# PixHawk_Fire_v1_5.net
KiCad netlist of a schematic drawn in EAGLE
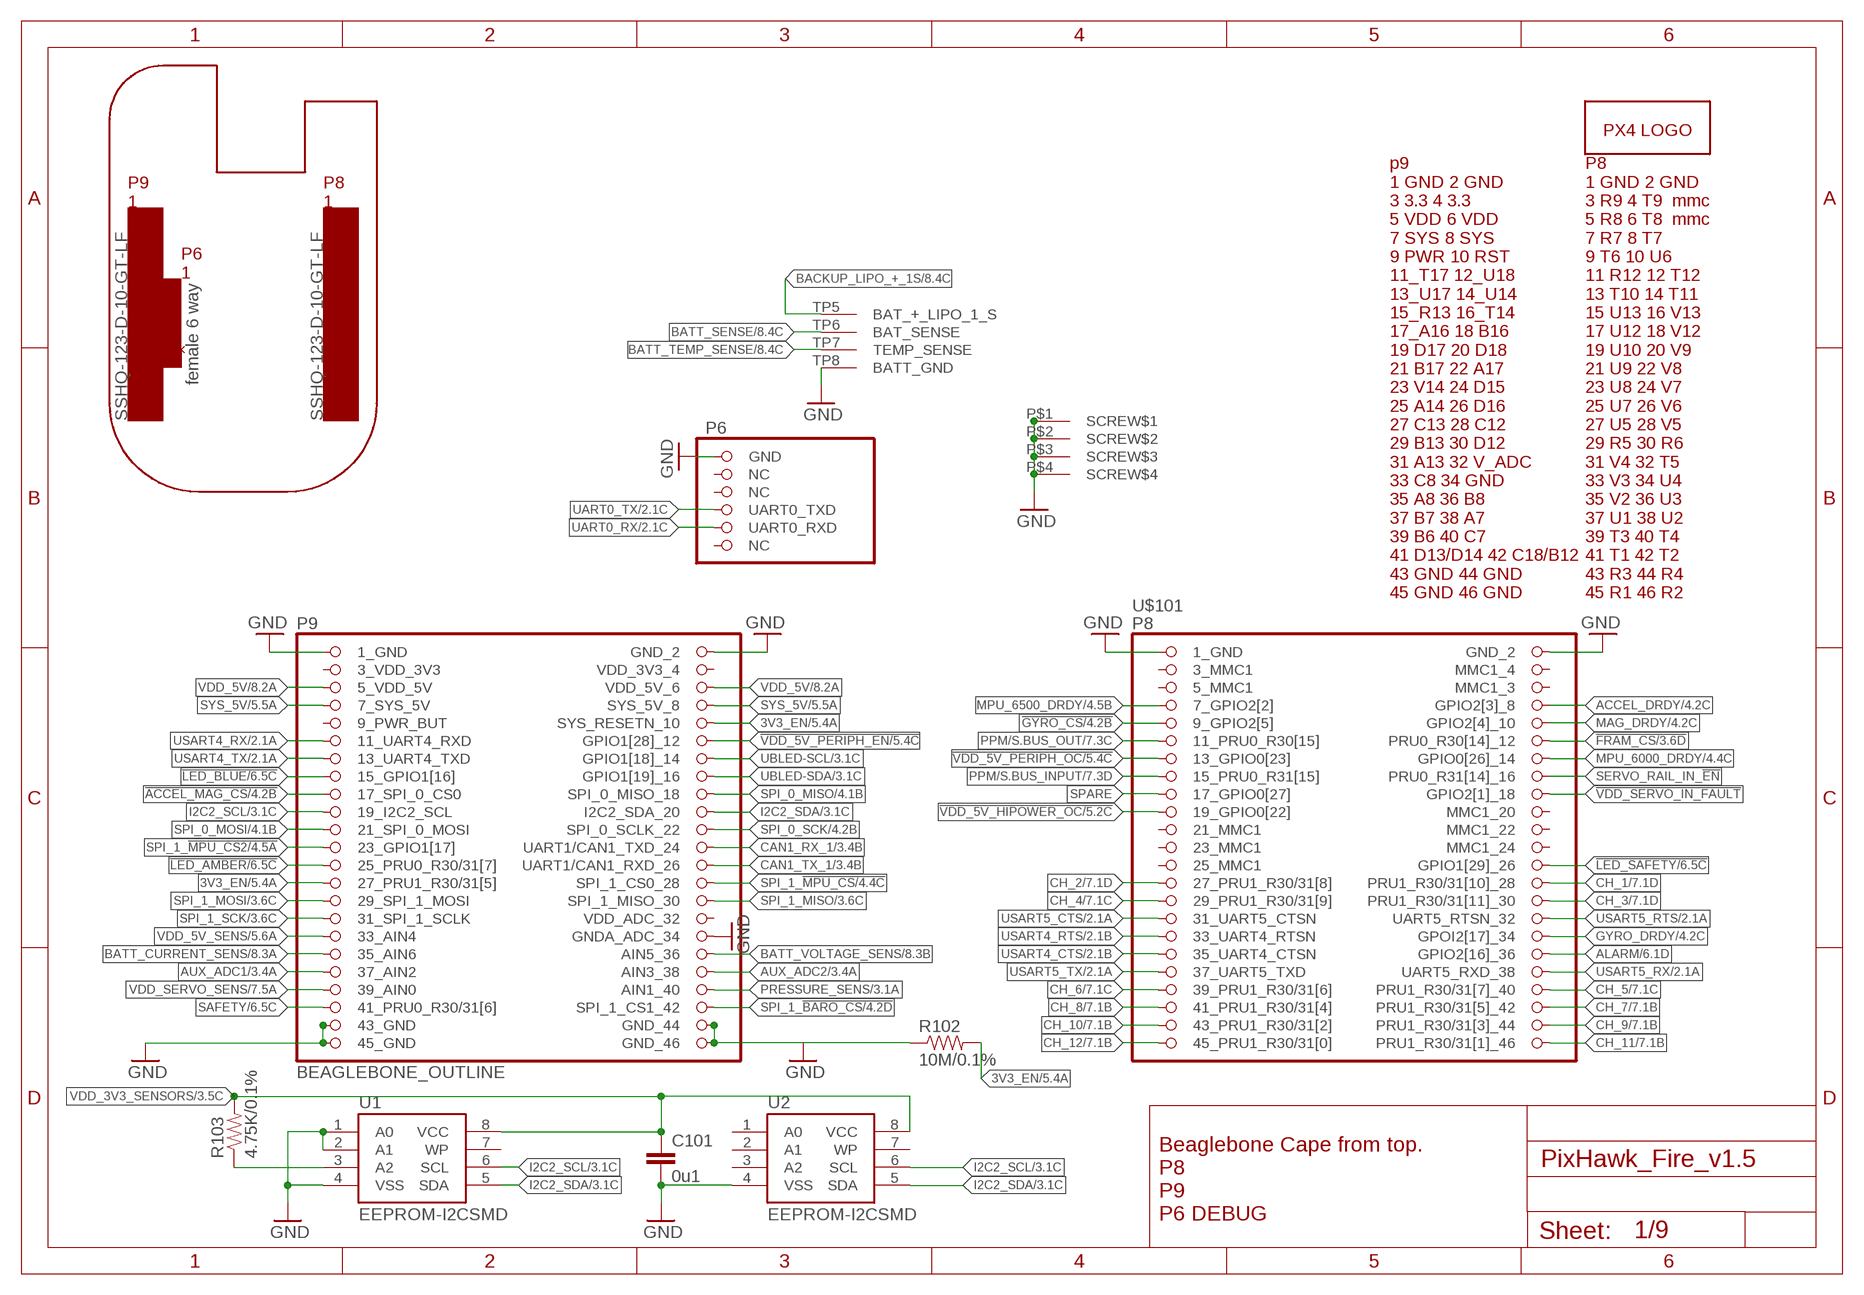
[diagram p0: schematic, sheet 1]
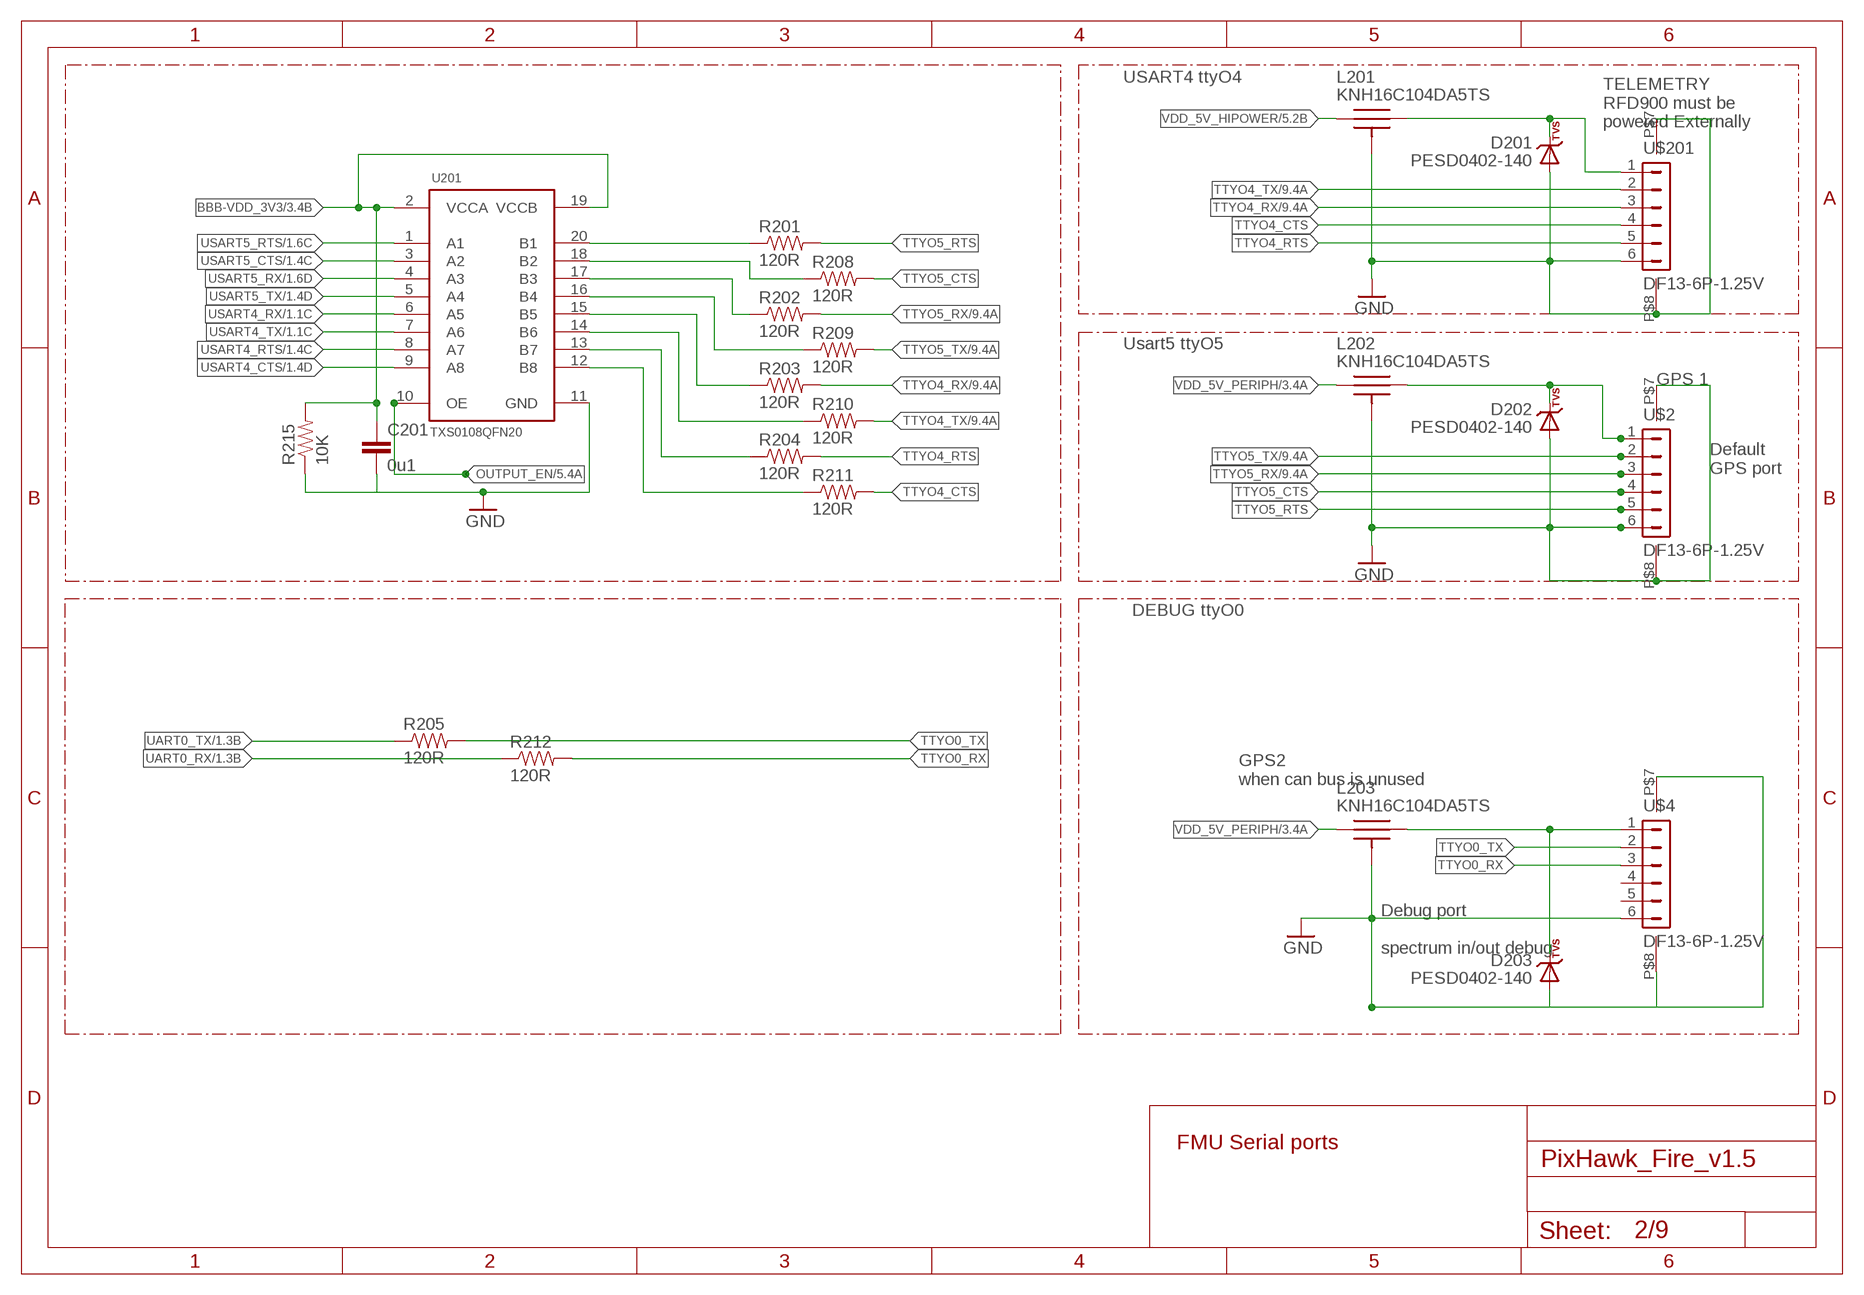
[diagram p1: schematic, sheet 2]
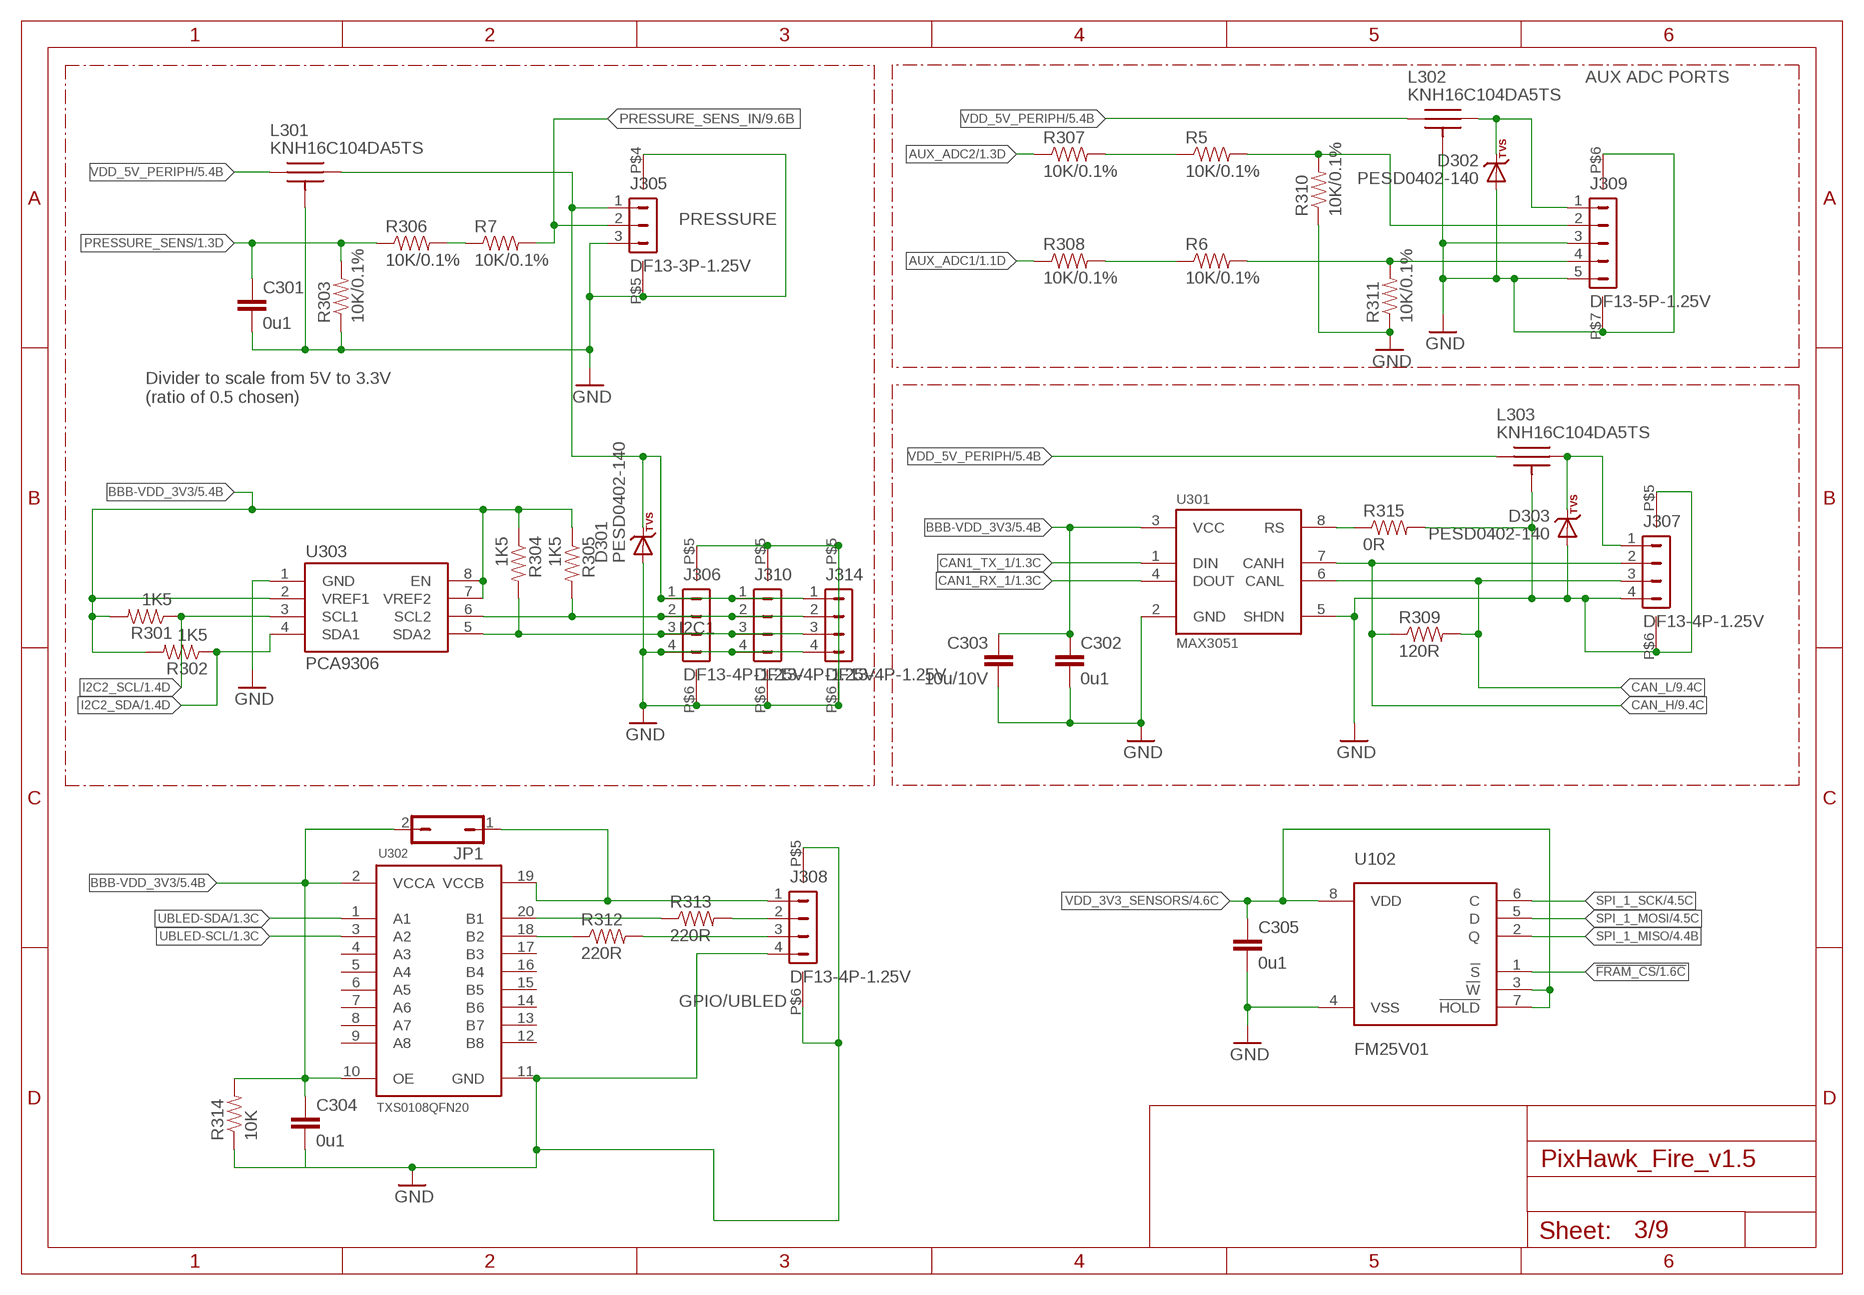
[diagram p2: schematic, sheet 3]
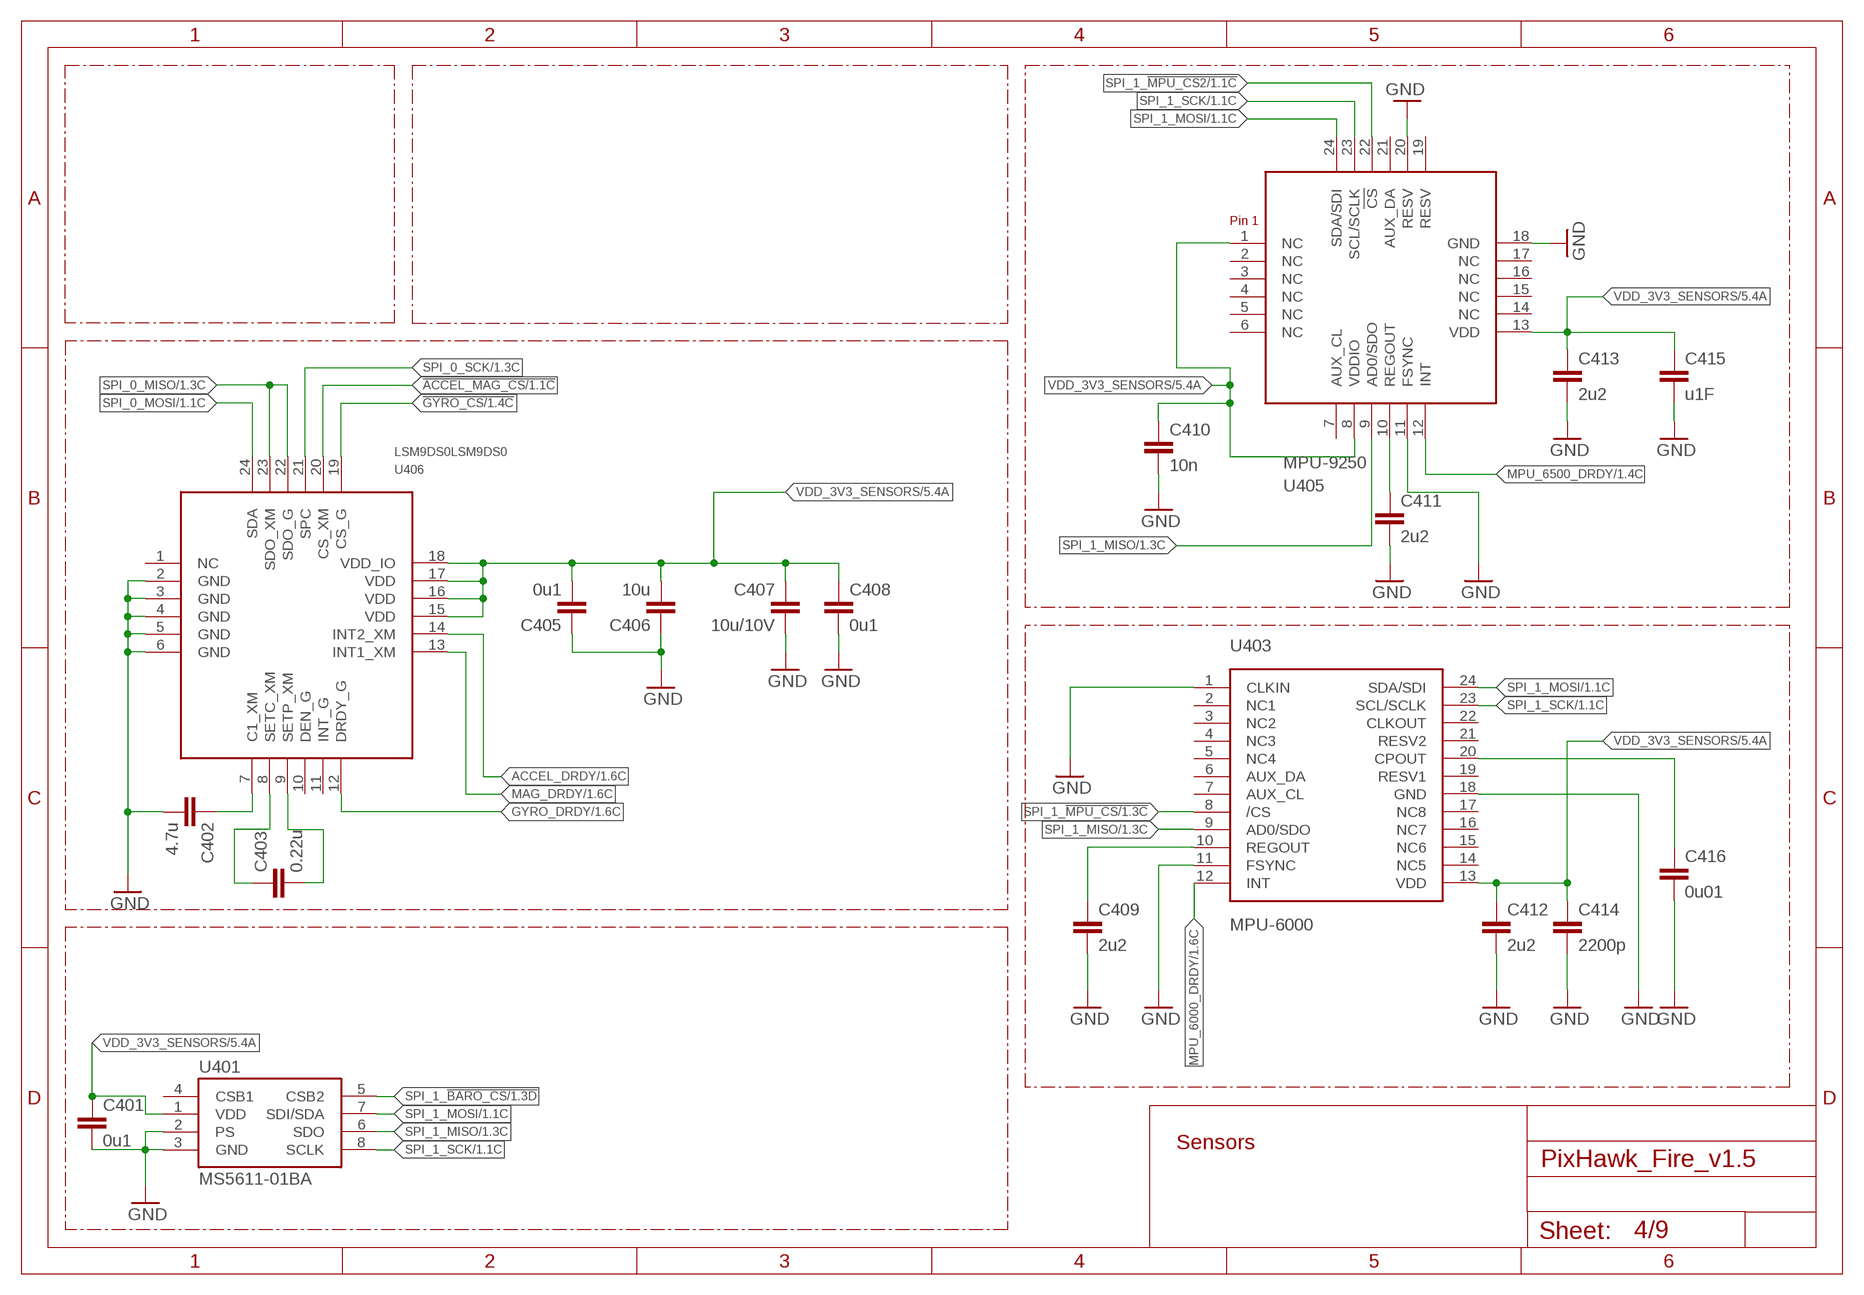
[diagram p3: schematic, sheet 4]
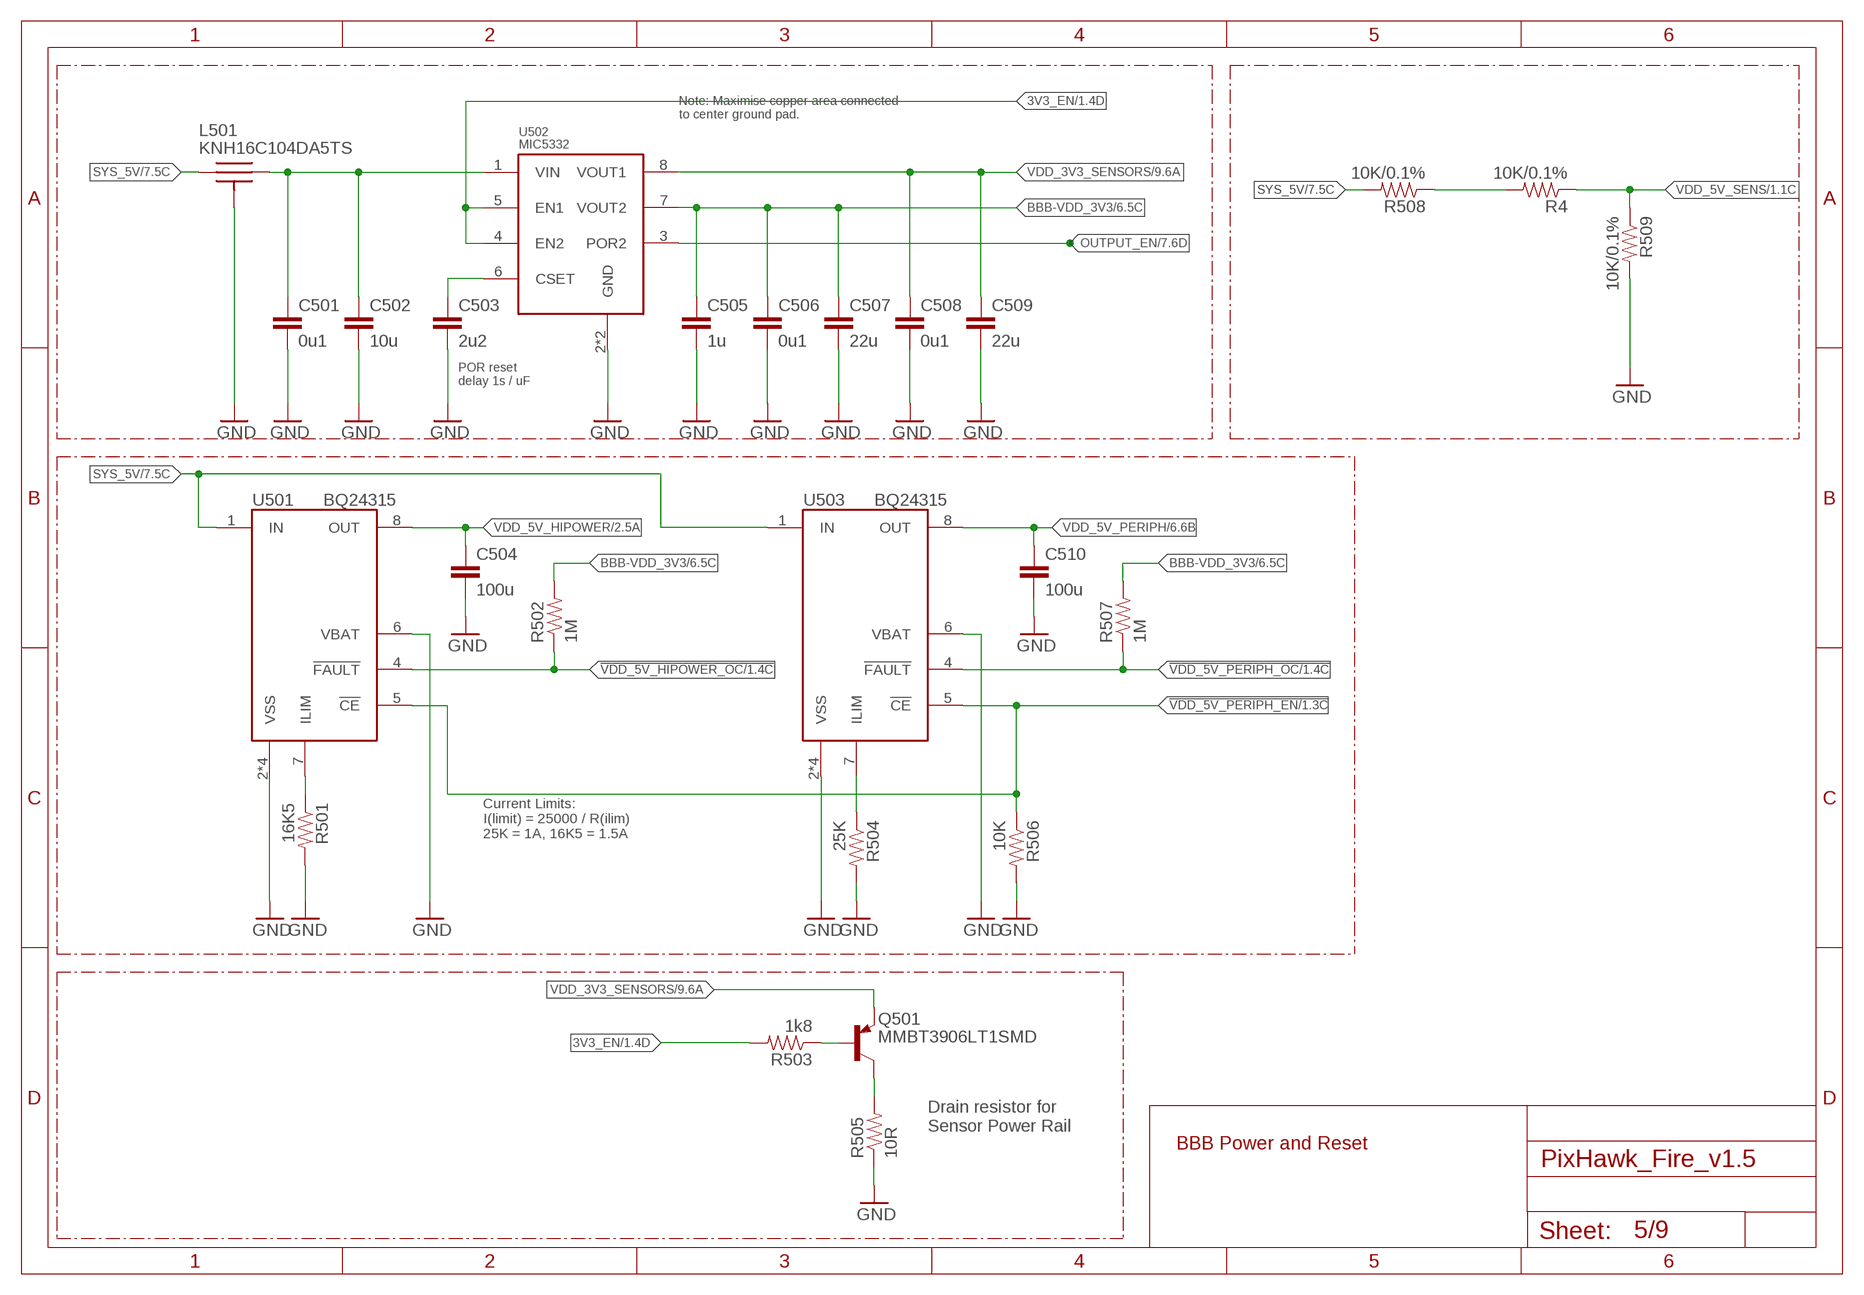
[diagram p4: schematic, sheet 5]
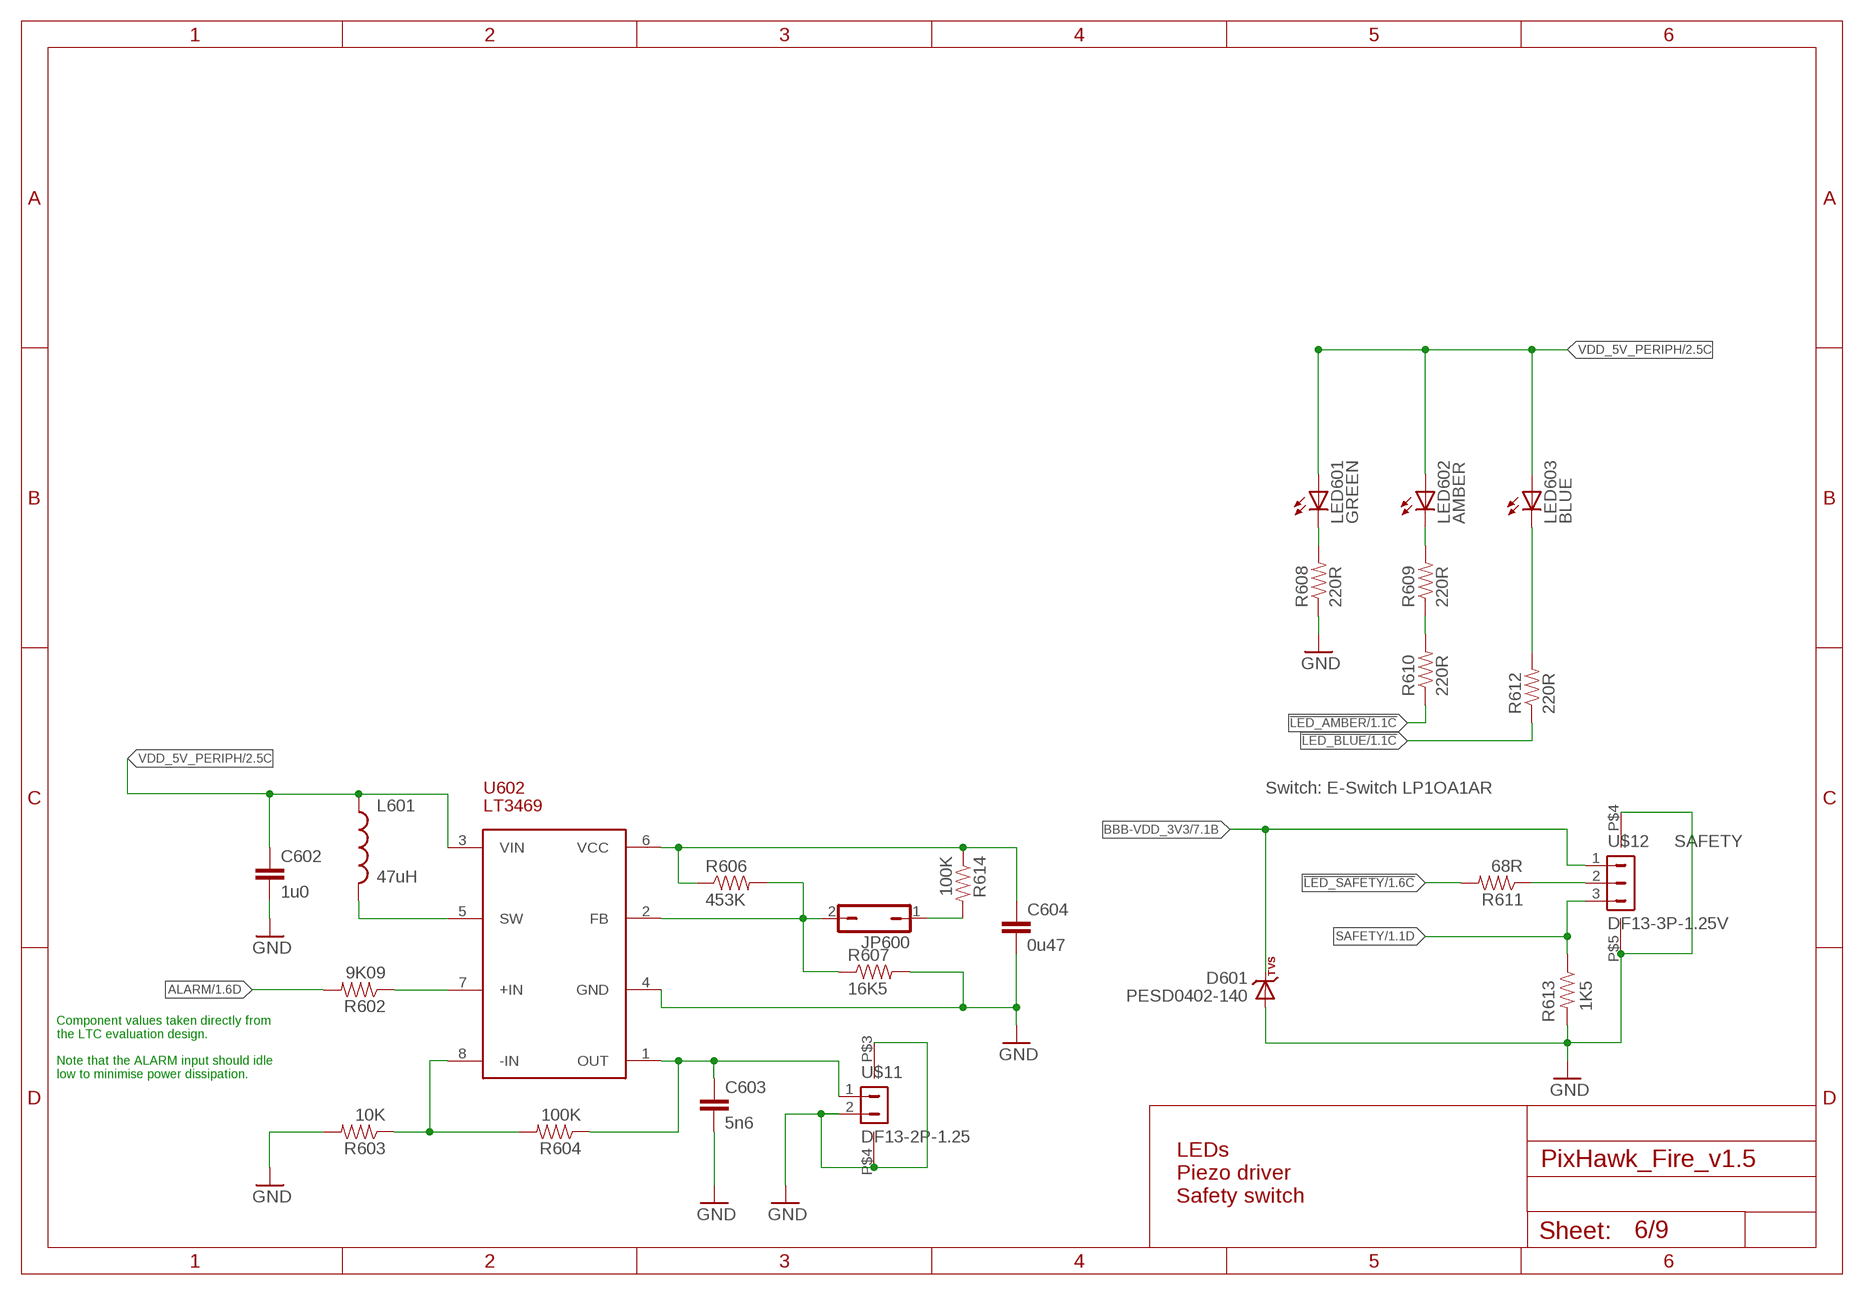
[diagram p5: schematic, sheet 6]
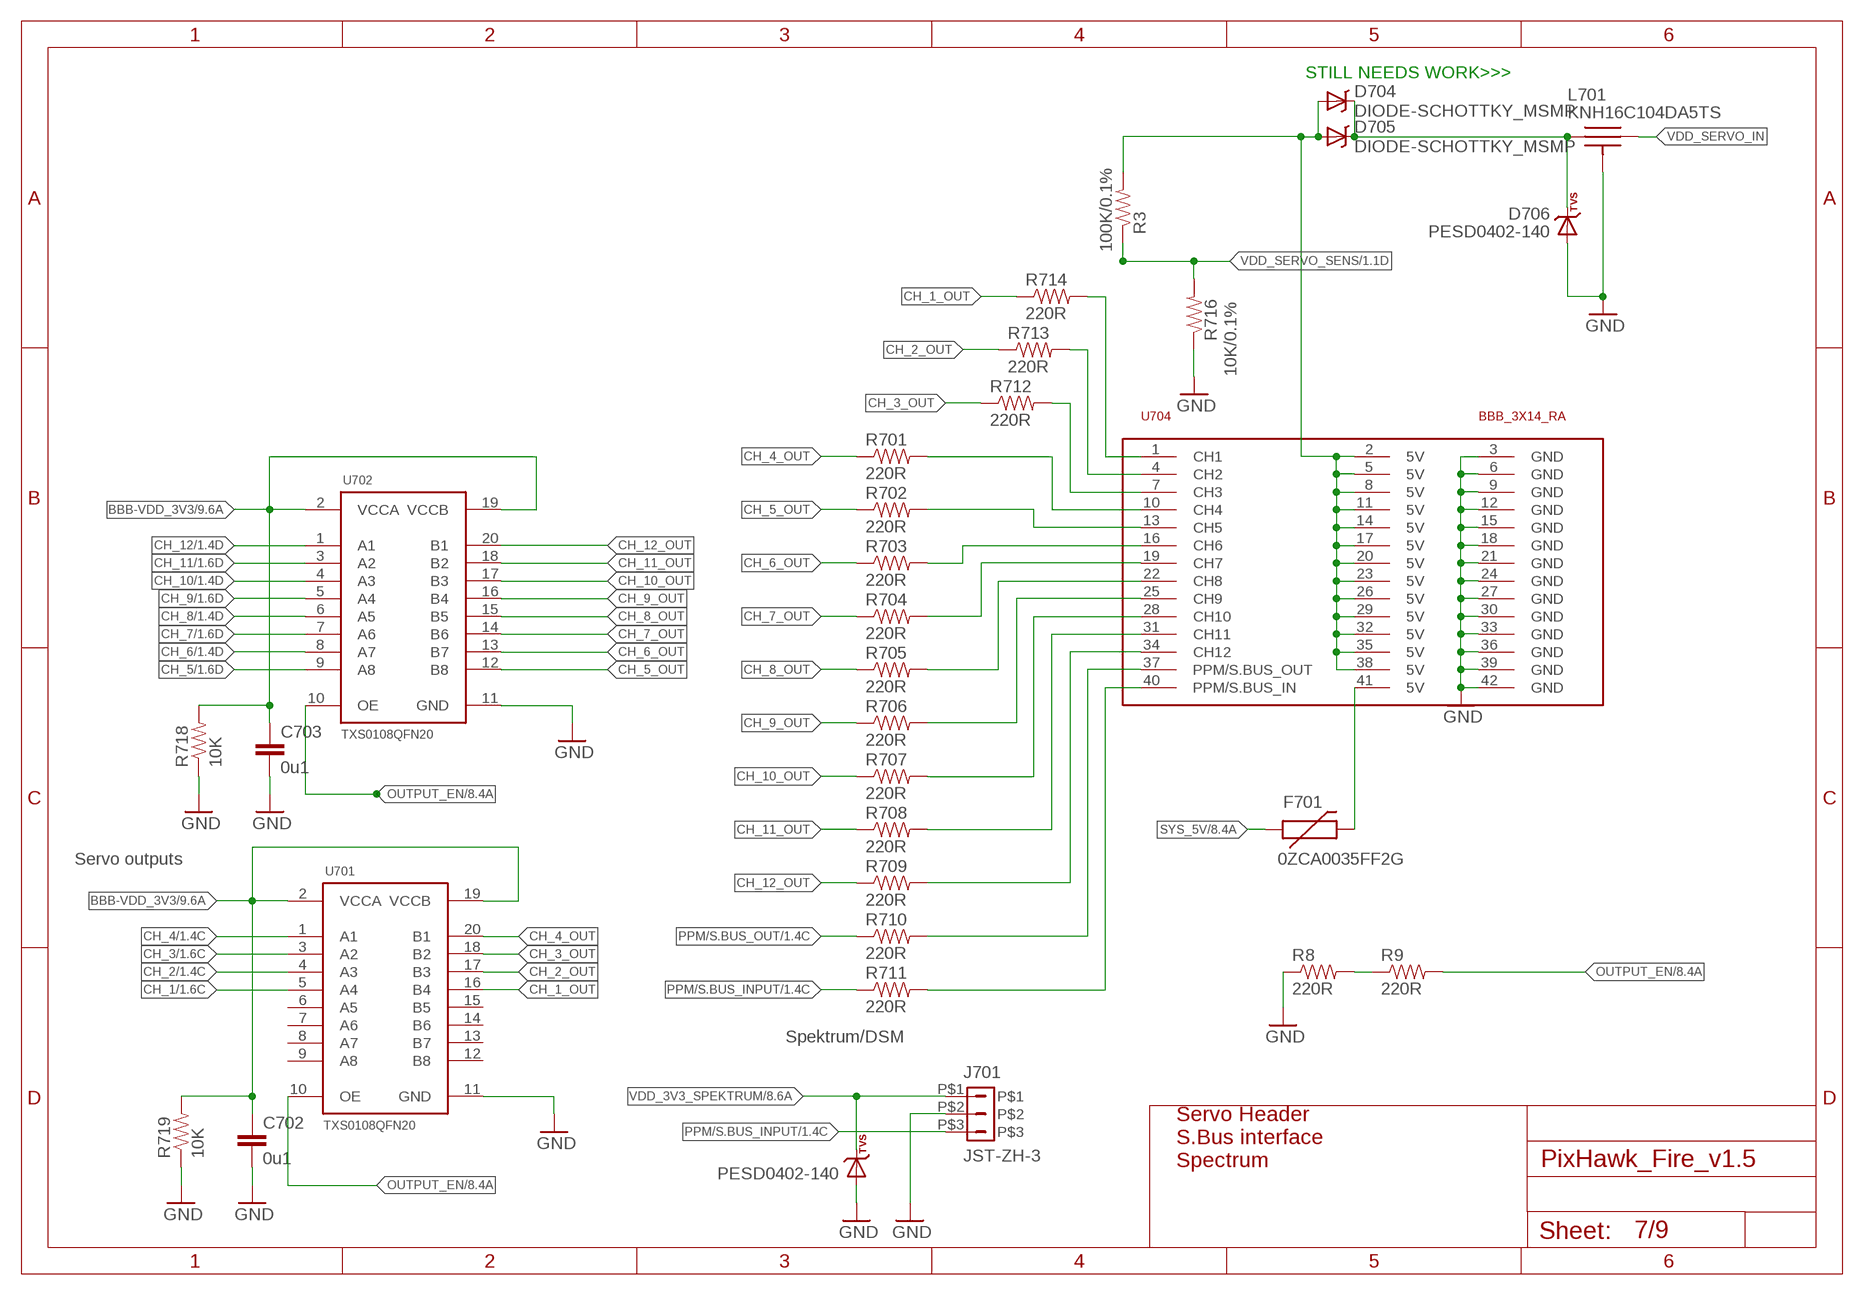
[diagram p6: schematic, sheet 7]
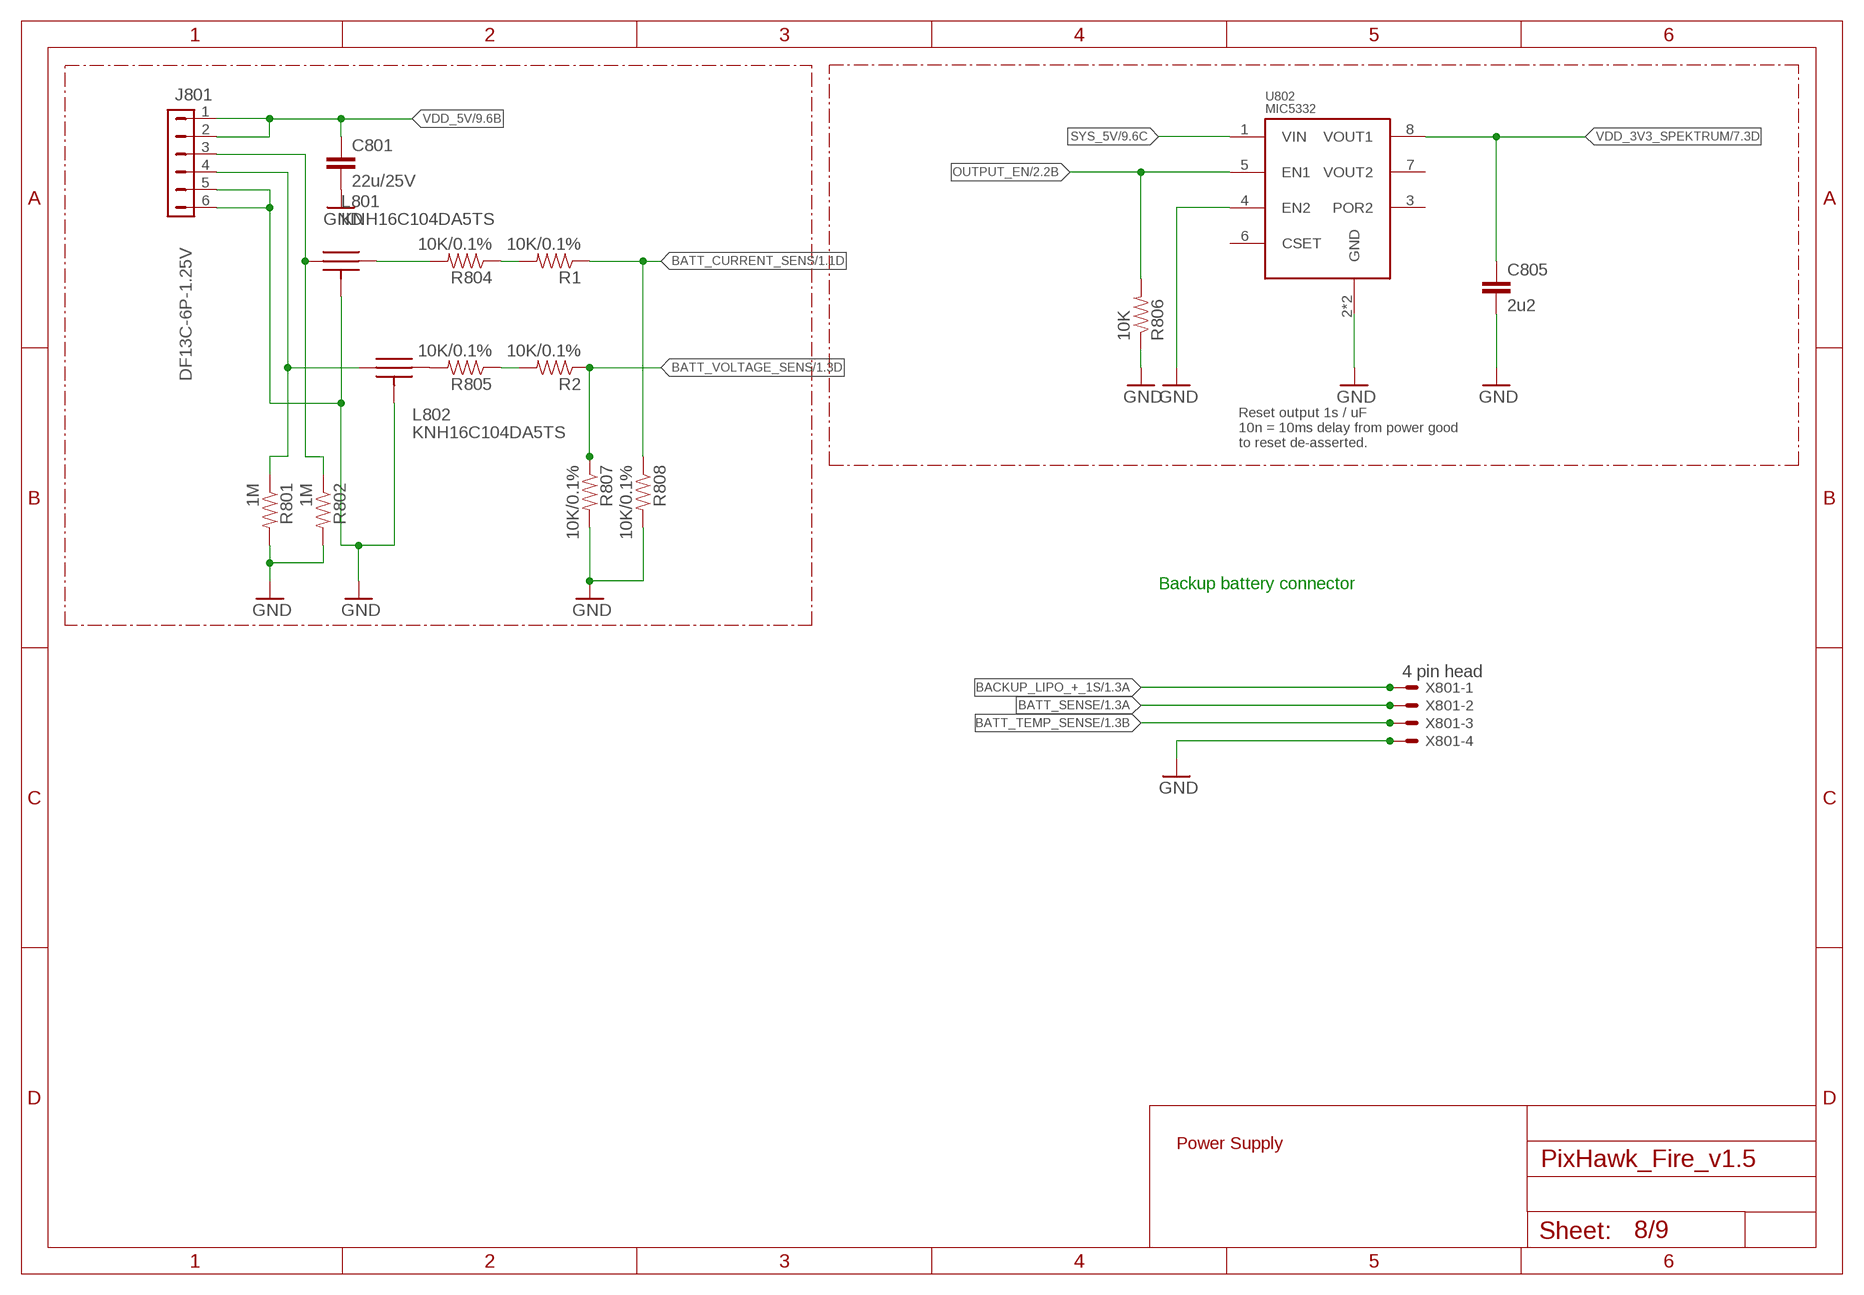
[diagram p7: schematic, sheet 8]
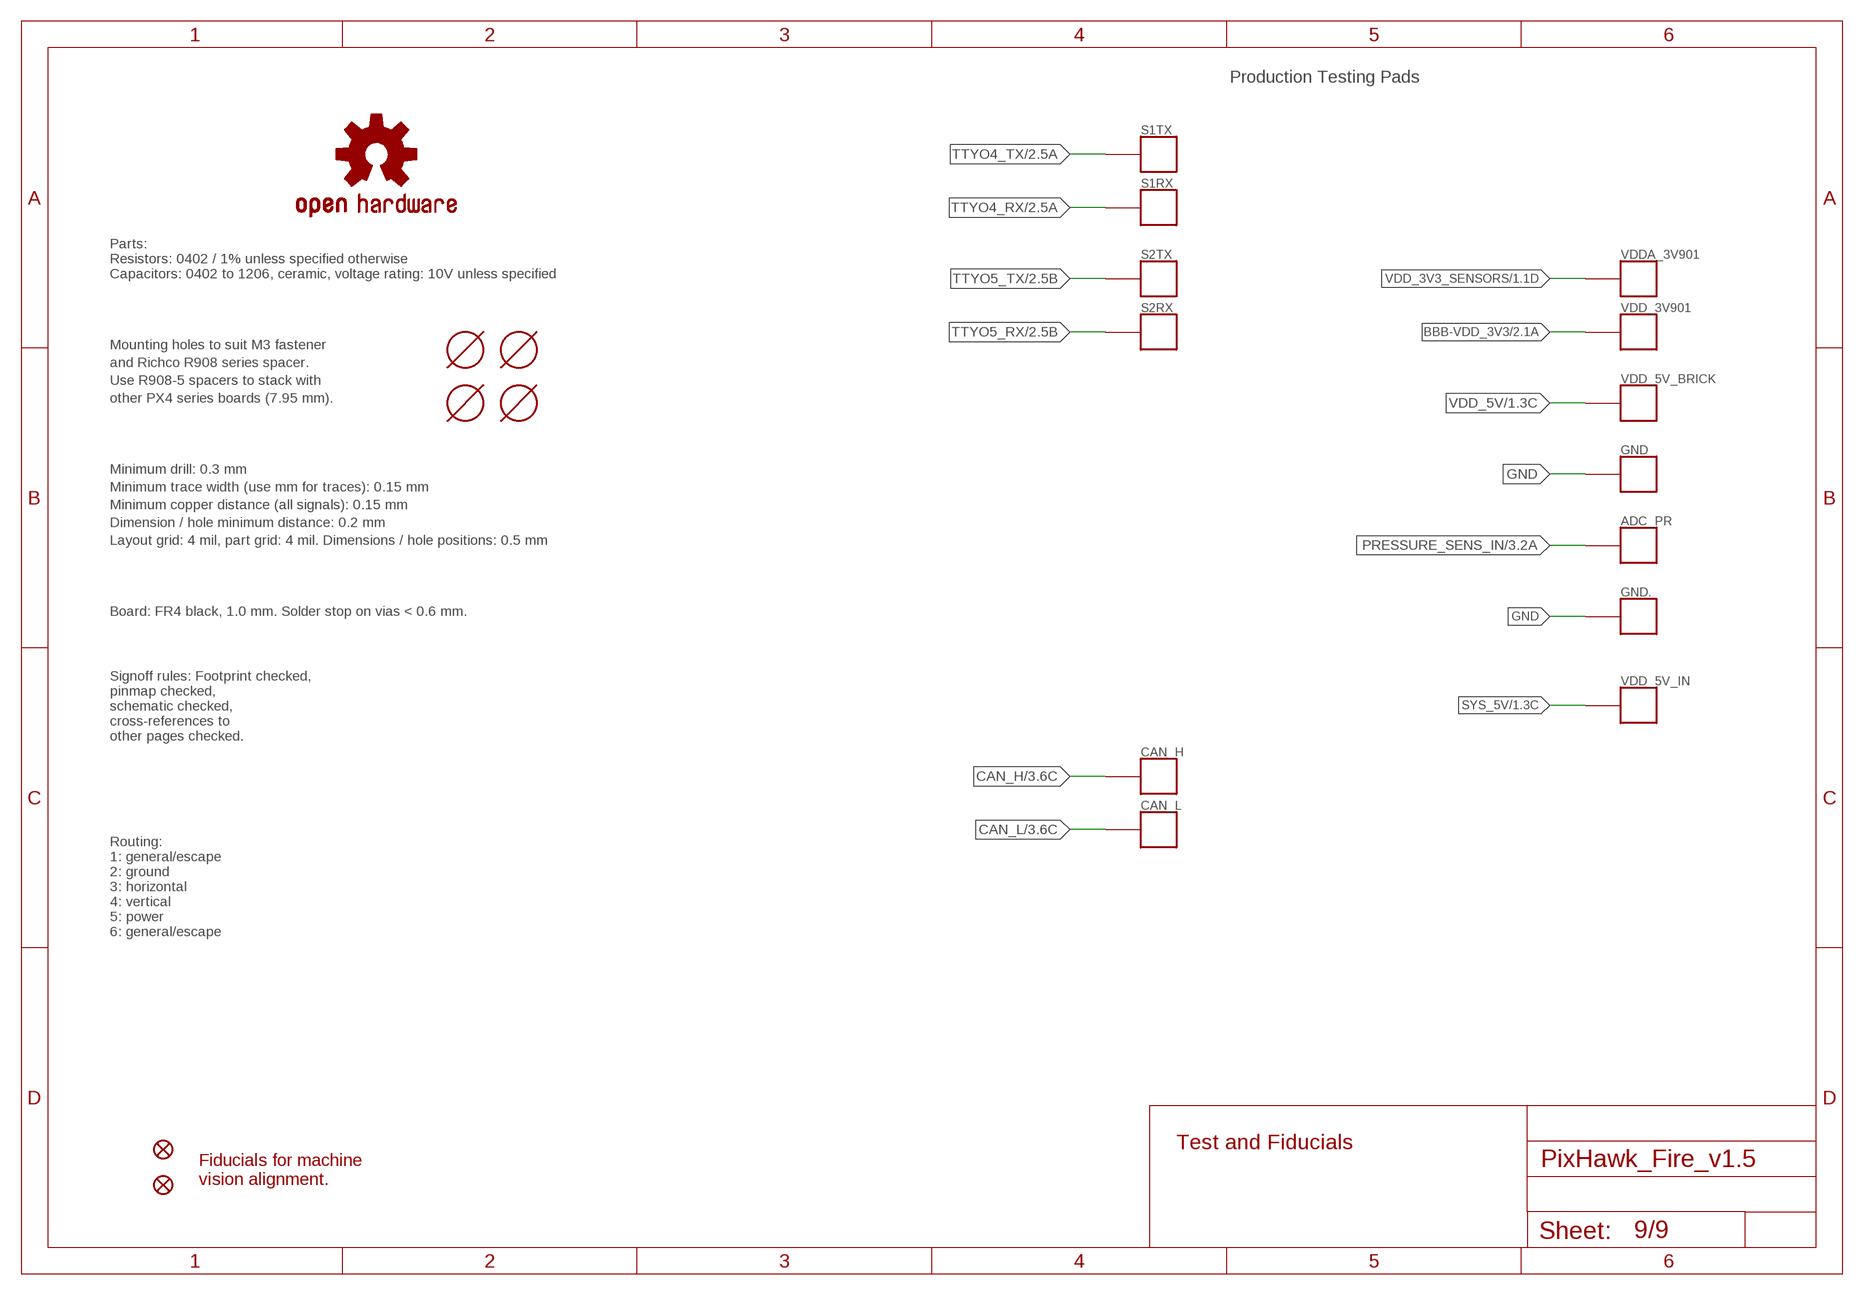
[diagram p8: schematic, sheet 9]

(export (version "E")
  (design (tool "Eeschema 10.0.6"))
  (components
    (comp (ref "C201")
      (value "0u1")
      (footprint "eagle-import:0402-CAP")
      (fields (field (name "PARTNO") "CC0402ZRY5V7BB104"))
      (libsource (lib "eagle-import") (part "CAP0402"))
    )
    (comp (ref "D201")
      (value "PESD0402-140")
      (footprint "eagle-import:0402-TVS")
      (libsource (lib "eagle-import") (part "DIODE-TVS"))
    )
    (comp (ref "D202")
      (value "PESD0402-140")
      (footprint "eagle-import:0402-TVS")
      (libsource (lib "eagle-import") (part "DIODE-TVS"))
    )
    (comp (ref "D203")
      (value "PESD0402-140")
      (footprint "eagle-import:0402-TVS")
      (libsource (lib "eagle-import") (part "DIODE-TVS"))
    )
    (comp (ref "L201")
      (value "KNH16C104DA5TS")
      (footprint "eagle-import:KYOCERA-KNH16-DA")
      (libsource (lib "eagle-import") (part "KNH16C104DA5TS"))
    )
    (comp (ref "L202")
      (value "KNH16C104DA5TS")
      (footprint "eagle-import:KYOCERA-KNH16-DA")
      (libsource (lib "eagle-import") (part "KNH16C104DA5TS"))
    )
    (comp (ref "L203")
      (value "KNH16C104DA5TS")
      (footprint "eagle-import:KYOCERA-KNH16-DA")
      (libsource (lib "eagle-import") (part "KNH16C104DA5TS"))
    )
    (comp (ref "R201")
      (value "120R")
      (footprint "eagle-import:0402-RES")
      (fields (field (name "PARTNO") "RC0402FR-07120RL"))
      (libsource (lib "eagle-import") (part "RESISTOR0402-RES"))
    )
    (comp (ref "R202")
      (value "120R")
      (footprint "eagle-import:0402-RES")
      (fields (field (name "PARTNO") "RC0402FR-07120RL"))
      (libsource (lib "eagle-import") (part "RESISTOR0402-RES"))
    )
    (comp (ref "R203")
      (value "120R")
      (footprint "eagle-import:0402-RES")
      (fields (field (name "PARTNO") "RC0402FR-07120RL"))
      (libsource (lib "eagle-import") (part "RESISTOR0402-RES"))
    )
    (comp (ref "R204")
      (value "120R")
      (footprint "eagle-import:0402-RES")
      (fields (field (name "PARTNO") "RC0402FR-07120RL"))
      (libsource (lib "eagle-import") (part "RESISTOR0402-RES"))
    )
    (comp (ref "R205")
      (value "120R")
      (footprint "eagle-import:0402-RES")
      (fields (field (name "PARTNO") "RC0402FR-07120RL"))
      (libsource (lib "eagle-import") (part "RESISTOR0402-RES"))
    )
    (comp (ref "R208")
      (value "120R")
      (footprint "eagle-import:0402-RES")
      (fields (field (name "PARTNO") "RC0402FR-07120RL"))
      (libsource (lib "eagle-import") (part "RESISTOR0402-RES"))
    )
    (comp (ref "R209")
      (value "120R")
      (footprint "eagle-import:0402-RES")
      (fields (field (name "PARTNO") "RC0402FR-07120RL"))
      (libsource (lib "eagle-import") (part "RESISTOR0402-RES"))
    )
    (comp (ref "R210")
      (value "120R")
      (footprint "eagle-import:0402-RES")
      (fields (field (name "PARTNO") "RC0402FR-07120RL"))
      (libsource (lib "eagle-import") (part "RESISTOR0402-RES"))
    )
    (comp (ref "R211")
      (value "120R")
      (footprint "eagle-import:0402-RES")
      (fields (field (name "PARTNO") "RC0402FR-07120RL"))
      (libsource (lib "eagle-import") (part "RESISTOR0402-RES"))
    )
    (comp (ref "R212")
      (value "120R")
      (footprint "eagle-import:0402-RES")
      (fields (field (name "PARTNO") "RC0402FR-07120RL"))
      (libsource (lib "eagle-import") (part "RESISTOR0402-RES"))
    )
    (comp (ref "R215")
      (value "10K")
      (footprint "eagle-import:0402-RES")
      (fields (field (name "PARTNO") "ERA-2AEB103X"))
      (libsource (lib "eagle-import") (part "RESISTOR0402-RES"))
    )
    (comp (ref "U$2")
      (value "DF13-6P-1.25V")
      (footprint "eagle-import:DF13C-6P-1.25V")
      (fields (field (name "PARTNO") "DF13C-6P-1.25V(20)"))
      (libsource (lib "eagle-import") (part "pxf_DF13-6P-1.25V"))
    )
    (comp (ref "U$4")
      (value "DF13-6P-1.25V")
      (footprint "eagle-import:DF13C-6P-1.25V")
      (fields (field (name "PARTNO") "DF13C-6P-1.25V(20)"))
      (libsource (lib "eagle-import") (part "pxf_DF13-6P-1.25V"))
    )
    (comp (ref "U$201")
      (value "DF13-6P-1.25V")
      (footprint "eagle-import:DF13C-6P-1.25V")
      (fields (field (name "PARTNO") "DF13C-6P-1.25V(20)"))
      (libsource (lib "eagle-import") (part "pxf_DF13-6P-1.25V"))
    )
    (comp (ref "U201")
      (value "TXS0108QFN20")
      (footprint "eagle-import:QFN20-RGY")
      (fields (field (name "PARTNO") "TXS0108ERGYR"))
      (libsource (lib "eagle-import") (part "TXS0108QFN20"))
    )
    (comp (ref "C801")
      (value "22u/25V")
      (footprint "eagle-import:0805-CAP")
      (fields (field (name "PARTNO") "CL21A226MAQNNNE"))
      (libsource (lib "eagle-import") (part "CAP0805"))
    )
    (comp (ref "C805")
      (value "2u2")
      (footprint "eagle-import:0402-CAP")
      (fields (field (name "PARTNO") "CC0603ZRY5V6BB225"))
      (libsource (lib "eagle-import") (part "CAP0402"))
    )
    (comp (ref "J801")
      (value "DF13C-6P-1.25V")
      (footprint "eagle-import:DF13C-6P-1.25V")
      (fields (field (name "PARTNO") "DF13C-6P-1.25V(20)"))
      (libsource (lib "eagle-import") (part "DF13-6P-1.25V"))
    )
    (comp (ref "L801")
      (value "KNH16C104DA5TS")
      (footprint "eagle-import:KYOCERA-KNH16-DA")
      (libsource (lib "eagle-import") (part "KNH16C104DA5TS"))
    )
    (comp (ref "L802")
      (value "KNH16C104DA5TS")
      (footprint "eagle-import:KYOCERA-KNH16-DA")
      (libsource (lib "eagle-import") (part "KNH16C104DA5TS"))
    )
    (comp (ref "R1")
      (value "10K/0.1%")
      (footprint "eagle-import:0402-RES")
      (fields (field (name "PARTNO") "ERA-2AEB103X"))
      (libsource (lib "eagle-import") (part "RESISTOR0402-RES"))
    )
    (comp (ref "R2")
      (value "10K/0.1%")
      (footprint "eagle-import:0402-RES")
      (fields (field (name "PARTNO") "ERA-2AEB103X"))
      (libsource (lib "eagle-import") (part "RESISTOR0402-RES"))
    )
    (comp (ref "R801")
      (value "1M")
      (footprint "eagle-import:0402-RES")
      (fields (field (name "PARTNO") "RC0402FR-071ML"))
      (libsource (lib "eagle-import") (part "RESISTOR0402-RES"))
    )
    (comp (ref "R802")
      (value "1M")
      (footprint "eagle-import:0402-RES")
      (fields (field (name "PARTNO") "RC0402FR-071ML"))
      (libsource (lib "eagle-import") (part "RESISTOR0402-RES"))
    )
    (comp (ref "R804")
      (value "10K/0.1%")
      (footprint "eagle-import:0402-RES")
      (fields (field (name "PARTNO") "ERA-2AEB103X"))
      (libsource (lib "eagle-import") (part "RESISTOR0402-RES"))
    )
    (comp (ref "R805")
      (value "10K/0.1%")
      (footprint "eagle-import:0402-RES")
      (fields (field (name "PARTNO") "ERA-2AEB103X"))
      (libsource (lib "eagle-import") (part "RESISTOR0402-RES"))
    )
    (comp (ref "R806")
      (value "10K")
      (footprint "eagle-import:0402-RES")
      (fields (field (name "PARTNO") "ERA-2AEB103X"))
      (libsource (lib "eagle-import") (part "RESISTOR0402-RES"))
    )
    (comp (ref "R807")
      (value "10K/0.1%")
      (footprint "eagle-import:0402-RES")
      (fields (field (name "PARTNO") "ERA-2AEB103X"))
      (libsource (lib "eagle-import") (part "RESISTOR0402-RES"))
    )
    (comp (ref "R808")
      (value "10K/0.1%")
      (footprint "eagle-import:0402-RES")
      (fields (field (name "PARTNO") "ERA-2AEB103X"))
      (libsource (lib "eagle-import") (part "RESISTOR0402-RES"))
    )
    (comp (ref "U802")
      (value "MIC5332")
      (footprint "eagle-import:MLF-8-EPAD")
      (fields (field (name "PARTNO") "MIC5332-SSYMT"))
      (libsource (lib "eagle-import") (part "MIC5332"))
    )
    (comp (ref "X801")
      (value "4 pin head")
      (footprint "eagle-import:53047-04")
      (fields (field (name "PARTNO") "53047-04"))
      (libsource (lib "eagle-import") (part "53?-04047"))
    )
    (comp (ref "C101")
      (value "0u1")
      (footprint "eagle-import:0402-CAP")
      (fields (field (name "PARTNO") "CC0402ZRY5V7BB104"))
      (libsource (lib "eagle-import") (part "CAP0402"))
    )
    (comp (ref "R102")
      (value "10M/0.1%")
      (footprint "eagle-import:0402-RES")
      (fields (field (name "PARTNO") "RC0402FR-0710ML"))
      (libsource (lib "eagle-import") (part "RESISTOR0402-RES"))
    )
    (comp (ref "R103")
      (value "4.75K/0.1%")
      (footprint "eagle-import:0402-RES")
      (fields (field (name "PARTNO") "RC0402FR-074K75L"))
      (libsource (lib "eagle-import") (part "RESISTOR0402-RES"))
    )
    (comp (ref "U$1")
      (value "PX4-LOGO")
      (footprint "eagle-import:PIXHAWK-FIRE-LOGO-30")
      (libsource (lib "eagle-import") (part "PX4-LOGO"))
    )
    (comp (ref "U$101")
      (value "BEAGLEBONE_OUTLINE")
      (footprint "eagle-import:BEAGLEBONE_SHIELD")
      (libsource (lib "eagle-import") (part "BEAGLEBONE_OUTLINE"))
    )
    (comp (ref "U1")
      (value "EEPROM-I2CSMD")
      (footprint "eagle-import:SO08")
      (fields (field (name "PARTNO") "AT24CS32-SSHM"))
      (libsource (lib "eagle-import") (part "EEPROM-I2CSMD"))
    )
    (comp (ref "U2")
      (value "EEPROM-I2CSMD")
      (footprint "eagle-import:SO08")
      (fields (field (name "PARTNO") "ATSHA204-SH-DA-TTR-ND"))
      (libsource (lib "eagle-import") (part "EEPROM-I2CSMD"))
    )
    (comp (ref "C702")
      (value "0u1")
      (footprint "eagle-import:0402-CAP")
      (fields (field (name "PARTNO") "CC0402ZRY5V7BB104"))
      (libsource (lib "eagle-import") (part "CAP0402"))
    )
    (comp (ref "C703")
      (value "0u1")
      (footprint "eagle-import:0402-CAP")
      (fields (field (name "PARTNO") "CC0402ZRY5V7BB104"))
      (libsource (lib "eagle-import") (part "CAP0402"))
    )
    (comp (ref "D703")
      (value "PESD0402-140")
      (footprint "eagle-import:0402-TVS")
      (libsource (lib "eagle-import") (part "DIODE-TVS"))
    )
    (comp (ref "D704")
      (value "DIODE-SCHOTTKY_MSMP")
      (footprint "eagle-import:MICROSMP")
      (fields (field (name "PARTNO") "SS14"))
      (libsource (lib "eagle-import") (part "DIODE-SCHOTTKY_MSMP"))
    )
    (comp (ref "D705")
      (value "DIODE-SCHOTTKY_MSMP")
      (footprint "eagle-import:MICROSMP")
      (fields (field (name "PARTNO") "SS14"))
      (libsource (lib "eagle-import") (part "DIODE-SCHOTTKY_MSMP"))
    )
    (comp (ref "D706")
      (value "PESD0402-140")
      (footprint "eagle-import:0402-TVS")
      (libsource (lib "eagle-import") (part "DIODE-TVS"))
    )
    (comp (ref "F701")
      (value "0ZCA0035FF2G")
      (footprint "eagle-import:PTC-1206")
      (libsource (lib "eagle-import") (part "PTCSMD"))
    )
    (comp (ref "J701")
      (value "JST-ZH-3")
      (footprint "eagle-import:JST-ZH-SMT-VERTICAL")
      (fields (field (name "PARTNO") "B3B-ZR-SM4-TF (LF)(SN)(P)"))
      (libsource (lib "eagle-import") (part "JST-ZH-3"))
    )
    (comp (ref "L701")
      (value "KNH16C104DA5TS")
      (footprint "eagle-import:KYOCERA-KNH16-DA")
      (libsource (lib "eagle-import") (part "KNH16C104DA5TS"))
    )
    (comp (ref "R3")
      (value "100K/0.1%")
      (footprint "eagle-import:0402-RES")
      (fields (field (name "PARTNO") "ERA-2AEB104X"))
      (libsource (lib "eagle-import") (part "RESISTOR0402-RES"))
    )
    (comp (ref "R8")
      (value "220R")
      (footprint "eagle-import:0402-RES")
      (fields (field (name "PARTNO") "RC0402FR-07220RL"))
      (libsource (lib "eagle-import") (part "RESISTOR0402-RES"))
    )
    (comp (ref "R9")
      (value "220R")
      (footprint "eagle-import:0402-RES")
      (fields (field (name "PARTNO") "RC0402FR-07220RL"))
      (libsource (lib "eagle-import") (part "RESISTOR0402-RES"))
    )
    (comp (ref "R701")
      (value "220R")
      (footprint "eagle-import:0402-RES")
      (fields (field (name "PARTNO") "RC0402FR-07120RL"))
      (libsource (lib "eagle-import") (part "RESISTOR0402-RES"))
    )
    (comp (ref "R702")
      (value "220R")
      (footprint "eagle-import:0402-RES")
      (fields (field (name "PARTNO") "RC0402FR-07120RL"))
      (libsource (lib "eagle-import") (part "RESISTOR0402-RES"))
    )
    (comp (ref "R703")
      (value "220R")
      (footprint "eagle-import:0402-RES")
      (fields (field (name "PARTNO") "RC0402FR-07120RL"))
      (libsource (lib "eagle-import") (part "RESISTOR0402-RES"))
    )
    (comp (ref "R704")
      (value "220R")
      (footprint "eagle-import:0402-RES")
      (fields (field (name "PARTNO") "RC0402FR-07120RL"))
      (libsource (lib "eagle-import") (part "RESISTOR0402-RES"))
    )
    (comp (ref "R705")
      (value "220R")
      (footprint "eagle-import:0402-RES")
      (fields (field (name "PARTNO") "RC0402FR-07120RL"))
      (libsource (lib "eagle-import") (part "RESISTOR0402-RES"))
    )
    (comp (ref "R706")
      (value "220R")
      (footprint "eagle-import:0402-RES")
      (fields (field (name "PARTNO") "RC0402FR-07120RL"))
      (libsource (lib "eagle-import") (part "RESISTOR0402-RES"))
    )
    (comp (ref "R707")
      (value "220R")
      (footprint "eagle-import:0402-RES")
      (fields (field (name "PARTNO") "RC0402FR-07120RL"))
      (libsource (lib "eagle-import") (part "RESISTOR0402-RES"))
    )
    (comp (ref "R708")
      (value "220R")
      (footprint "eagle-import:0402-RES")
      (fields (field (name "PARTNO") "RC0402FR-07120RL"))
      (libsource (lib "eagle-import") (part "RESISTOR0402-RES"))
    )
    (comp (ref "R709")
      (value "220R")
      (footprint "eagle-import:0402-RES")
      (fields (field (name "PARTNO") "RC0402FR-07120RL"))
      (libsource (lib "eagle-import") (part "RESISTOR0402-RES"))
    )
    (comp (ref "R710")
      (value "220R")
      (footprint "eagle-import:0402-RES")
      (fields (field (name "PARTNO") "RC0402FR-07120RL"))
      (libsource (lib "eagle-import") (part "RESISTOR0402-RES"))
    )
    (comp (ref "R711")
      (value "220R")
      (footprint "eagle-import:0402-RES")
      (fields (field (name "PARTNO") "RC0402FR-07120RL"))
      (libsource (lib "eagle-import") (part "RESISTOR0402-RES"))
    )
    (comp (ref "R712")
      (value "220R")
      (footprint "eagle-import:0402-RES")
      (fields (field (name "PARTNO") "RC0402FR-07120RL"))
      (libsource (lib "eagle-import") (part "RESISTOR0402-RES"))
    )
    (comp (ref "R713")
      (value "220R")
      (footprint "eagle-import:0402-RES")
      (fields (field (name "PARTNO") "RC0402FR-07120RL"))
      (libsource (lib "eagle-import") (part "RESISTOR0402-RES"))
    )
    (comp (ref "R714")
      (value "220R")
      (footprint "eagle-import:0402-RES")
      (fields (field (name "PARTNO") "RC0402FR-07120RL"))
      (libsource (lib "eagle-import") (part "RESISTOR0402-RES"))
    )
    (comp (ref "R716")
      (value "10K/0.1%")
      (footprint "eagle-import:0402-RES")
      (fields (field (name "PARTNO") "ERA-2AEB103X"))
      (libsource (lib "eagle-import") (part "RESISTOR0402-RES"))
    )
    (comp (ref "R718")
      (value "10K")
      (footprint "eagle-import:0402-RES")
      (fields (field (name "PARTNO") "ERA-2AEB103X"))
      (libsource (lib "eagle-import") (part "RESISTOR0402-RES"))
    )
    (comp (ref "R719")
      (value "10K")
      (footprint "eagle-import:0402-RES")
      (fields (field (name "PARTNO") "ERA-2AEB103X"))
      (libsource (lib "eagle-import") (part "RESISTOR0402-RES"))
    )
    (comp (ref "U701")
      (value "TXS0108QFN20")
      (footprint "eagle-import:QFN20-RGY")
      (fields (field (name "PARTNO") "TXS0108ERGYR"))
      (libsource (lib "eagle-import") (part "TXS0108QFN20"))
    )
    (comp (ref "U702")
      (value "TXS0108QFN20")
      (footprint "eagle-import:QFN20-RGY")
      (fields (field (name "PARTNO") "TXS0108ERGYR"))
      (libsource (lib "eagle-import") (part "TXS0108QFN20"))
    )
    (comp (ref "U704")
      (value "BBB_3X14_RA")
      (footprint "eagle-import:3X14RA")
      (fields (field (name "PARTNO") "07579"))
      (libsource (lib "eagle-import") (part "BBB_3X14_RA"))
    )
    (comp (ref "C401")
      (value "0u1")
      (footprint "eagle-import:0402-CAP")
      (fields (field (name "PARTNO") "CC0402ZRY5V7BB104"))
      (libsource (lib "eagle-import") (part "CAP0402"))
    )
    (comp (ref "C402")
      (value "4.7u")
      (footprint "eagle-import:0603-CAP")
      (fields (field (name "PARTNO") "C1608X7S1A475K080AC"))
      (libsource (lib "eagle-import") (part "CAP0603"))
    )
    (comp (ref "C403")
      (value "0.22u")
      (footprint "eagle-import:0603-CAP")
      (fields (field (name "PARTNO") "CL10B224JP8NNNC"))
      (libsource (lib "eagle-import") (part "CAP0603"))
    )
    (comp (ref "C405")
      (value "0u1")
      (footprint "eagle-import:0603-CAP")
      (fields (field (name "PARTNO") "CL10B104JO8NNNC"))
      (libsource (lib "eagle-import") (part "CAP0603"))
    )
    (comp (ref "C406")
      (value "10u")
      (footprint "eagle-import:0603-CAP")
      (fields (field (name "PARTNO") "C1608X7S0J106M080AC"))
      (libsource (lib "eagle-import") (part "CAP0603"))
    )
    (comp (ref "C407")
      (value "10u/10V")
      (footprint "eagle-import:0805-CAP")
      (fields (field (name "PARTNO") "CC0805ZKY5V6BB106"))
      (libsource (lib "eagle-import") (part "CAP0805"))
    )
    (comp (ref "C408")
      (value "0u1")
      (footprint "eagle-import:0402-CAP")
      (fields (field (name "PARTNO") "CC0402ZRY5V7BB104"))
      (libsource (lib "eagle-import") (part "CAP0402"))
    )
    (comp (ref "C409")
      (value "2u2")
      (footprint "eagle-import:0603-CAP")
      (fields (field (name "PARTNO") "C1608X6S1C225K080AC"))
      (libsource (lib "eagle-import") (part "CAP0603"))
    )
    (comp (ref "C410")
      (value "10n")
      (footprint "eagle-import:0603-CAP")
      (fields (field (name "PARTNO") "C0603C103J5RAC7411"))
      (libsource (lib "eagle-import") (part "CAP0603"))
    )
    (comp (ref "C411")
      (value "2u2")
      (footprint "eagle-import:0603-CAP")
      (fields (field (name "PARTNO") "C1608X6S1C225K080AC"))
      (libsource (lib "eagle-import") (part "CAP0603"))
    )
    (comp (ref "C412")
      (value "2u2")
      (footprint "eagle-import:0603-CAP")
      (fields (field (name "PARTNO") "CGA3E1X7R0J225K080AC"))
      (libsource (lib "eagle-import") (part "CAP0603"))
    )
    (comp (ref "C413")
      (value "2u2")
      (footprint "eagle-import:0603-CAP")
      (libsource (lib "eagle-import") (part "CAP0603"))
    )
    (comp (ref "C414")
      (value "2200p")
      (footprint "eagle-import:0402-CAP")
      (fields (field (name "PARTNO") "C0603C222J5RACTU"))
      (libsource (lib "eagle-import") (part "CAP0402"))
    )
    (comp (ref "C415")
      (value "u1F")
      (footprint "eagle-import:0402-CAP")
      (fields (field (name "PARTNO") "CC0402ZRY5V7BB104"))
      (libsource (lib "eagle-import") (part "CAP0402"))
    )
    (comp (ref "C416")
      (value "0u01")
      (footprint "eagle-import:0603-CAP")
      (fields (field (name "PARTNO") "06033C103JAT2A"))
      (libsource (lib "eagle-import") (part "CAP0603"))
    )
    (comp (ref "U401")
      (value "MS5611-01BA")
      (footprint "eagle-import:MS5611-01BA")
      (libsource (lib "eagle-import") (part "MS5611-01BA"))
    )
    (comp (ref "U403")
      (value "MPU-6000")
      (footprint "eagle-import:QFN-24")
      (libsource (lib "eagle-import") (part "MPU-6000"))
    )
    (comp (ref "U405")
      (value "MPU-9250")
      (footprint "eagle-import:MPU-6500")
      (libsource (lib "eagle-import") (part "MPU-6500"))
    )
    (comp (ref "U406")
      (value "LSM9DS0LSM9DS0")
      (footprint "eagle-import:LSM9DS0")
      (fields (field (name "PARTNO") "LSM9DS0TR"))
      (libsource (lib "eagle-import") (part "LSM9DS0LSM9DS0"))
    )
    (comp (ref "ADC_PR")
      (value "PAD.04")
      (footprint "eagle-import:PAD.04X.04")
      (libsource (lib "eagle-import") (part "PAD.04"))
    )
    (comp (ref "CAN_H")
      (value "PAD.04")
      (footprint "eagle-import:PAD.04X.04")
      (libsource (lib "eagle-import") (part "PAD.04"))
    )
    (comp (ref "CAN_L")
      (value "PAD.04")
      (footprint "eagle-import:PAD.04X.04")
      (libsource (lib "eagle-import") (part "PAD.04"))
    )
    (comp (ref "GND")
      (value "PAD.04")
      (footprint "eagle-import:PAD.04X.04")
      (libsource (lib "eagle-import") (part "PAD.04"))
    )
    (comp (ref "GND.")
      (value "PAD.04")
      (footprint "eagle-import:PAD.04X.04")
      (libsource (lib "eagle-import") (part "PAD.04"))
    )
    (comp (ref "JP901")
      (value "FIDUCIAL1.5X3")
      (footprint "eagle-import:FIDUCIAL-1.5X3")
      (libsource (lib "eagle-import") (part "FIDUCIAL1.5X3"))
    )
    (comp (ref "JP902")
      (value "FIDUCIAL1.5X3")
      (footprint "eagle-import:FIDUCIAL-1.5X3")
      (libsource (lib "eagle-import") (part "FIDUCIAL1.5X3"))
    )
    (comp (ref "M3_MOUNT901")
      (value "MOUNT-HOLE3.1MM")
      (footprint "eagle-import:MOUNT-HOLE3.1")
      (libsource (lib "eagle-import") (part "MOUNT-HOLE3.1MM"))
    )
    (comp (ref "M3_MOUNT902")
      (value "MOUNT-HOLE3.1MM")
      (footprint "eagle-import:MOUNT-HOLE3.1")
      (libsource (lib "eagle-import") (part "MOUNT-HOLE3.1MM"))
    )
    (comp (ref "M3_MOUNT903")
      (value "MOUNT-HOLE3.1MM")
      (footprint "eagle-import:MOUNT-HOLE3.1")
      (libsource (lib "eagle-import") (part "MOUNT-HOLE3.1MM"))
    )
    (comp (ref "M3_MOUNT904")
      (value "MOUNT-HOLE3.1MM")
      (footprint "eagle-import:MOUNT-HOLE3.1")
      (libsource (lib "eagle-import") (part "MOUNT-HOLE3.1MM"))
    )
    (comp (ref "OSHW_LOGO")
      (value "OSHW-LOGOS")
      (footprint "eagle-import:OSHW-LOGO-S")
      (libsource (lib "eagle-import") (part "OSHW-LOGOS"))
    )
    (comp (ref "S1RX")
      (value "PAD.04")
      (footprint "eagle-import:PAD.04X.04")
      (libsource (lib "eagle-import") (part "PAD.04"))
    )
    (comp (ref "S1TX")
      (value "PAD.04")
      (footprint "eagle-import:PAD.04X.04")
      (libsource (lib "eagle-import") (part "PAD.04"))
    )
    (comp (ref "S2RX")
      (value "PAD.04")
      (footprint "eagle-import:PAD.04X.04")
      (libsource (lib "eagle-import") (part "PAD.04"))
    )
    (comp (ref "S2TX")
      (value "PAD.04")
      (footprint "eagle-import:PAD.04X.04")
      (libsource (lib "eagle-import") (part "PAD.04"))
    )
    (comp (ref "VDDA_3V901")
      (value "PAD.04")
      (footprint "eagle-import:PAD.04X.04")
      (libsource (lib "eagle-import") (part "PAD.04"))
    )
    (comp (ref "VDD_3V901")
      (value "PAD.04")
      (footprint "eagle-import:PAD.04X.04")
      (libsource (lib "eagle-import") (part "PAD.04"))
    )
    (comp (ref "VDD_5V_BRICK")
      (value "PAD.04")
      (footprint "eagle-import:PAD.04X.04")
      (libsource (lib "eagle-import") (part "PAD.04"))
    )
    (comp (ref "VDD_5V_IN")
      (value "PAD.04")
      (footprint "eagle-import:PAD.04X.04")
      (libsource (lib "eagle-import") (part "PAD.04"))
    )
    (comp (ref "C501")
      (value "0u1")
      (footprint "eagle-import:0402-CAP")
      (fields (field (name "PARTNO") "CC0402ZRY5V7BB104"))
      (libsource (lib "eagle-import") (part "CAP0402"))
    )
    (comp (ref "C502")
      (value "10u")
      (footprint "eagle-import:0805-CAP")
      (fields (field (name "PARTNO") "C1608X7S0J106M080AC"))
      (libsource (lib "eagle-import") (part "CAP0805"))
    )
    (comp (ref "C503")
      (value "2u2")
      (footprint "eagle-import:0603-CAP")
      (fields (field (name "PARTNO") "C1608X6S1C225K080AC"))
      (libsource (lib "eagle-import") (part "CAP0603"))
    )
    (comp (ref "C504")
      (value "100u")
      (footprint "eagle-import:1206-CAP")
      (fields (field (name "PARTNO") "C3216X5R1A107M160AC"))
      (libsource (lib "eagle-import") (part "CAP1206"))
    )
    (comp (ref "C505")
      (value "1u")
      (footprint "eagle-import:0603-CAP")
      (fields (field (name "PARTNO") "CC0603ZRY5V7BB105"))
      (libsource (lib "eagle-import") (part "CAP0603"))
    )
    (comp (ref "C506")
      (value "0u1")
      (footprint "eagle-import:0402-CAP")
      (fields (field (name "PARTNO") "CC0402ZRY5V7BB104"))
      (libsource (lib "eagle-import") (part "CAP0402"))
    )
    (comp (ref "C507")
      (value "22u")
      (footprint "eagle-import:0805-CAP")
      (fields (field (name "PARTNO") "CC0805MKX5R5BB226"))
      (libsource (lib "eagle-import") (part "CAP0805"))
    )
    (comp (ref "C508")
      (value "0u1")
      (footprint "eagle-import:0402-CAP")
      (fields (field (name "PARTNO") "CC0402ZRY5V7BB104"))
      (libsource (lib "eagle-import") (part "CAP0402"))
    )
    (comp (ref "C509")
      (value "22u")
      (footprint "eagle-import:0805-CAP")
      (fields (field (name "PARTNO") "CC0805MKX5R5BB226"))
      (libsource (lib "eagle-import") (part "CAP0805"))
    )
    (comp (ref "C510")
      (value "100u")
      (footprint "eagle-import:1206-CAP")
      (fields (field (name "PARTNO") "C3216X5R1A107M160AC"))
      (libsource (lib "eagle-import") (part "CAP1206"))
    )
    (comp (ref "L501")
      (value "KNH16C104DA5TS")
      (footprint "eagle-import:KYOCERA-KNH16-DA")
      (libsource (lib "eagle-import") (part "KNH16C104DA5TS"))
    )
    (comp (ref "Q501")
      (value "MMBT3906LT1SMD")
      (footprint "eagle-import:SOT23-BEC")
      (fields (field (name "PARTNO") "MMBT3906LT1G"))
      (libsource (lib "eagle-import") (part "MMBT3906SMDLT1"))
    )
    (comp (ref "R4")
      (value "10K/0.1%")
      (footprint "eagle-import:0402-RES")
      (fields (field (name "PARTNO") "ERA-2AEB103X"))
      (libsource (lib "eagle-import") (part "RESISTOR0402-RES"))
    )
    (comp (ref "R501")
      (value "16K5")
      (footprint "eagle-import:0402-RES")
      (fields (field (name "PARTNO") "RMCF0402FT16K5"))
      (libsource (lib "eagle-import") (part "RESISTOR0402-RES"))
    )
    (comp (ref "R502")
      (value "1M")
      (footprint "eagle-import:0402-RES")
      (fields (field (name "PARTNO") "MCR01MRTF1004"))
      (libsource (lib "eagle-import") (part "RESISTOR0402-RES"))
    )
    (comp (ref "R503")
      (value "1k8")
      (footprint "eagle-import:0402-RES")
      (fields (field (name "PARTNO") "RC0402FR-071K8L"))
      (libsource (lib "eagle-import") (part "RESISTOR0402-RES"))
    )
    (comp (ref "R504")
      (value "25K")
      (footprint "eagle-import:0402-RES")
      (fields (field (name "PARTNO") "RMCF0402FT25K5"))
      (libsource (lib "eagle-import") (part "RESISTOR0402-RES"))
    )
    (comp (ref "R505")
      (value "10R")
      (footprint "eagle-import:0603-RES")
      (fields (field (name "PARTNO") "RC0402FR-0710RL"))
      (libsource (lib "eagle-import") (part "RESISTOR0603-RES"))
    )
    (comp (ref "R506")
      (value "10K")
      (footprint "eagle-import:0402-RES")
      (fields (field (name "PARTNO") "ERA-2AEB103X"))
      (libsource (lib "eagle-import") (part "RESISTOR0402-RES"))
    )
    (comp (ref "R507")
      (value "1M")
      (footprint "eagle-import:0402-RES")
      (fields (field (name "PARTNO") "MCR01MRTF1004"))
      (libsource (lib "eagle-import") (part "RESISTOR0402-RES"))
    )
    (comp (ref "R508")
      (value "10K/0.1%")
      (footprint "eagle-import:0402-RES")
      (fields (field (name "PARTNO") "ERA-2AEB103X"))
      (libsource (lib "eagle-import") (part "RESISTOR0402-RES"))
    )
    (comp (ref "R509")
      (value "10K/0.1%")
      (footprint "eagle-import:0402-RES")
      (fields (field (name "PARTNO") "ERA-2AEB103X"))
      (libsource (lib "eagle-import") (part "RESISTOR0402-RES"))
    )
    (comp (ref "U501")
      (value "BQ24315")
      (footprint "eagle-import:QFN8-DSG")
      (fields (field (name "PARTNO") "BQ24315DSGR"))
      (libsource (lib "eagle-import") (part "BQ24315"))
    )
    (comp (ref "U502")
      (value "MIC5332")
      (footprint "eagle-import:MLF-8-EPAD")
      (fields (field (name "PARTNO") "MIC5332-SSYMT"))
      (libsource (lib "eagle-import") (part "MIC5332"))
    )
    (comp (ref "U503")
      (value "BQ24315")
      (footprint "eagle-import:QFN8-DSG")
      (fields (field (name "PARTNO") "BQ24315DSGR"))
      (libsource (lib "eagle-import") (part "BQ24315"))
    )
    (comp (ref "C301")
      (value "0u1")
      (footprint "eagle-import:0402-CAP")
      (fields (field (name "PARTNO") "CC0402ZRY5V7BB104"))
      (libsource (lib "eagle-import") (part "CAP0402"))
    )
    (comp (ref "C302")
      (value "0u1")
      (footprint "eagle-import:0402-CAP")
      (fields (field (name "PARTNO") "CC0402ZRY5V7BB104"))
      (libsource (lib "eagle-import") (part "CAP0402"))
    )
    (comp (ref "C303")
      (value "10u/10V")
      (footprint "eagle-import:0805-CAP")
      (fields (field (name "PARTNO") "CC0805ZKY5V6BB106"))
      (libsource (lib "eagle-import") (part "CAP0805"))
    )
    (comp (ref "C304")
      (value "0u1")
      (footprint "eagle-import:0402-CAP")
      (fields (field (name "PARTNO") "CC0402ZRY5V7BB104"))
      (libsource (lib "eagle-import") (part "CAP0402"))
    )
    (comp (ref "C305")
      (value "0u1")
      (footprint "eagle-import:0402-CAP")
      (fields (field (name "PARTNO") "CC0402ZRY5V7BB104"))
      (libsource (lib "eagle-import") (part "CAP0402"))
    )
    (comp (ref "D301")
      (value "PESD0402-140")
      (footprint "eagle-import:0402-TVS")
      (libsource (lib "eagle-import") (part "DIODE-TVS"))
    )
    (comp (ref "D302")
      (value "PESD0402-140")
      (footprint "eagle-import:0402-TVS")
      (libsource (lib "eagle-import") (part "DIODE-TVS"))
    )
    (comp (ref "D303")
      (value "PESD0402-140")
      (footprint "eagle-import:0402-TVS")
      (libsource (lib "eagle-import") (part "DIODE-TVS"))
    )
    (comp (ref "J305")
      (value "DF13-3P-1.25V")
      (footprint "eagle-import:DF13C-3P-1.25V")
      (fields (field (name "PARTNO") "DF13C-3P-1.25V(20)"))
      (libsource (lib "eagle-import") (part "DF13-3P-1.25V"))
    )
    (comp (ref "J306")
      (value "DF13-4P-1.25V")
      (footprint "eagle-import:DF13C-4P-1.25V")
      (fields (field (name "PARTNO") "DF13C-4P-1.25V(20)"))
      (libsource (lib "eagle-import") (part "DF13-4P-1.25V"))
    )
    (comp (ref "J307")
      (value "DF13-4P-1.25V")
      (footprint "eagle-import:DF13C-4P-1.25V")
      (fields (field (name "PARTNO") "DF13C-4P-1.25V(20)"))
      (libsource (lib "eagle-import") (part "DF13-4P-1.25V"))
    )
    (comp (ref "J308")
      (value "DF13-4P-1.25V")
      (footprint "eagle-import:DF13C-4P-1.25V")
      (fields (field (name "PARTNO") "DF13C-4P-1.25V(20)"))
      (libsource (lib "eagle-import") (part "DF13-4P-1.25V"))
    )
    (comp (ref "J309")
      (value "DF13-5P-1.25V")
      (footprint "eagle-import:DF13C-5P-1.25V")
      (fields (field (name "PARTNO") "DF13C-5P-1.25V(20)"))
      (libsource (lib "eagle-import") (part "DF13-5P-1.25V"))
    )
    (comp (ref "J310")
      (value "DF13-4P-1.25V")
      (footprint "eagle-import:DF13C-4P-1.25V")
      (fields (field (name "PARTNO") "DF13C-4P-1.25V(20)"))
      (libsource (lib "eagle-import") (part "DF13-4P-1.25V"))
    )
    (comp (ref "J314")
      (value "DF13-4P-1.25V")
      (footprint "eagle-import:DF13C-4P-1.25V")
      (fields (field (name "PARTNO") "DF13C-4P-1.25V(20)"))
      (libsource (lib "eagle-import") (part "DF13-4P-1.25V"))
    )
    (comp (ref "JP1")
      (value "JP1Q")
      (footprint "eagle-import:JP1")
      (fields (field (name "PARTNO") "1-87215-0"))
      (libsource (lib "eagle-import") (part "JP1Q"))
    )
    (comp (ref "L301")
      (value "KNH16C104DA5TS")
      (footprint "eagle-import:KYOCERA-KNH16-DA")
      (libsource (lib "eagle-import") (part "KNH16C104DA5TS"))
    )
    (comp (ref "L302")
      (value "KNH16C104DA5TS")
      (footprint "eagle-import:KYOCERA-KNH16-DA")
      (libsource (lib "eagle-import") (part "KNH16C104DA5TS"))
    )
    (comp (ref "L303")
      (value "KNH16C104DA5TS")
      (footprint "eagle-import:KYOCERA-KNH16-DA")
      (libsource (lib "eagle-import") (part "KNH16C104DA5TS"))
    )
    (comp (ref "R5")
      (value "10K/0.1%")
      (footprint "eagle-import:0402-RES")
      (fields (field (name "PARTNO") "ERA-2AEB103X"))
      (libsource (lib "eagle-import") (part "RESISTOR0402-RES"))
    )
    (comp (ref "R6")
      (value "10K/0.1%")
      (footprint "eagle-import:0402-RES")
      (fields (field (name "PARTNO") "ERA-2AEB103X"))
      (libsource (lib "eagle-import") (part "RESISTOR0402-RES"))
    )
    (comp (ref "R7")
      (value "10K/0.1%")
      (footprint "eagle-import:0402-RES")
      (fields (field (name "PARTNO") "ERA-2AEB103X"))
      (libsource (lib "eagle-import") (part "RESISTOR0402-RES"))
    )
    (comp (ref "R301")
      (value "1K5")
      (footprint "eagle-import:0402-RES")
      (fields (field (name "PARTNO") "RC0402FR-071K5L"))
      (libsource (lib "eagle-import") (part "RESISTOR0402-RES"))
    )
    (comp (ref "R302")
      (value "1K5")
      (footprint "eagle-import:0402-RES")
      (fields (field (name "PARTNO") "RC0402FR-071K5L"))
      (libsource (lib "eagle-import") (part "RESISTOR0402-RES"))
    )
    (comp (ref "R303")
      (value "10K/0.1%")
      (footprint "eagle-import:0402-RES")
      (fields (field (name "PARTNO") "ERA-2AEB103X"))
      (libsource (lib "eagle-import") (part "RESISTOR0402-RES"))
    )
    (comp (ref "R304")
      (value "1K5")
      (footprint "eagle-import:0402-RES")
      (fields (field (name "PARTNO") "RC0402FR-071K5L"))
      (libsource (lib "eagle-import") (part "RESISTOR0402-RES"))
    )
    (comp (ref "R305")
      (value "1K5")
      (footprint "eagle-import:0402-RES")
      (fields (field (name "PARTNO") "RC0402FR-071K5L"))
      (libsource (lib "eagle-import") (part "RESISTOR0402-RES"))
    )
    (comp (ref "R306")
      (value "10K/0.1%")
      (footprint "eagle-import:0402-RES")
      (fields (field (name "PARTNO") "ERA-2AEB103X"))
      (libsource (lib "eagle-import") (part "RESISTOR0402-RES"))
    )
    (comp (ref "R307")
      (value "10K/0.1%")
      (footprint "eagle-import:0402-RES")
      (fields (field (name "PARTNO") "ERA-2AEB103X"))
      (libsource (lib "eagle-import") (part "RESISTOR0402-RES"))
    )
    (comp (ref "R308")
      (value "10K/0.1%")
      (footprint "eagle-import:0402-RES")
      (fields (field (name "PARTNO") "ERA-2AEB103X"))
      (libsource (lib "eagle-import") (part "RESISTOR0402-RES"))
    )
    (comp (ref "R309")
      (value "120R")
      (footprint "eagle-import:0402-RES")
      (fields (field (name "PARTNO") "RC0402FR-07120RL"))
      (libsource (lib "eagle-import") (part "RESISTOR0402-RES"))
    )
    (comp (ref "R310")
      (value "10K/0.1%")
      (footprint "eagle-import:0402-RES")
      (fields (field (name "PARTNO") "ERA-2AEB103X"))
      (libsource (lib "eagle-import") (part "RESISTOR0402-RES"))
    )
    (comp (ref "R311")
      (value "10K/0.1%")
      (footprint "eagle-import:0402-RES")
      (fields (field (name "PARTNO") "ERA-2AEB103X"))
      (libsource (lib "eagle-import") (part "RESISTOR0402-RES"))
    )
    (comp (ref "R312")
      (value "220R")
      (footprint "eagle-import:0402-RES")
      (fields (field (name "PARTNO") "RC0402FR-07220RL"))
      (libsource (lib "eagle-import") (part "RESISTOR0402-RES"))
    )
    (comp (ref "R313")
      (value "220R")
      (footprint "eagle-import:0402-RES")
      (fields (field (name "PARTNO") "RC0402FR-07220RL"))
      (libsource (lib "eagle-import") (part "RESISTOR0402-RES"))
    )
    (comp (ref "R314")
      (value "10K")
      (footprint "eagle-import:0402-RES")
      (fields (field (name "PARTNO") "ERA-2AEB103X"))
      (libsource (lib "eagle-import") (part "RESISTOR0402-RES"))
    )
    (comp (ref "R315")
      (value "0R")
      (footprint "eagle-import:0402-RES")
      (fields (field (name "PARTNO") "RC0402FR-070RL"))
      (libsource (lib "eagle-import") (part "RESISTOR0402-RES"))
    )
    (comp (ref "U102")
      (value "FM25V01")
      (footprint "eagle-import:SO08")
      (fields (field (name "PARTNO") "FM25V01-G"))
      (libsource (lib "eagle-import") (part "FM25V01"))
    )
    (comp (ref "U301")
      (value "MAX3051")
      (footprint "eagle-import:SOT23-8")
      (fields (field (name "PARTNO") "MAX3051EKA"))
      (libsource (lib "eagle-import") (part "MAX3051MAX3051EKA"))
    )
    (comp (ref "U302")
      (value "TXS0108QFN20")
      (footprint "eagle-import:QFN20-RGY")
      (fields (field (name "PARTNO") "TXS0108ERGYR"))
      (libsource (lib "eagle-import") (part "TXS0108QFN20"))
    )
    (comp (ref "U303")
      (value "PCA9306")
      (footprint "eagle-import:PCA9306")
      (fields (field (name "PARTNO") "PCA9306DQER"))
      (libsource (lib "eagle-import") (part "PCA9306"))
    )
    (comp (ref "C602")
      (value "1u0")
      (footprint "eagle-import:0603-CAP")
      (fields (field (name "PARTNO") "CC0603ZRY5V7BB105"))
      (libsource (lib "eagle-import") (part "CAP0603"))
    )
    (comp (ref "C603")
      (value "5n6")
      (footprint "eagle-import:0402-CAP")
      (fields (field (name "PARTNO") "CC0402KRX7R7BB562"))
      (libsource (lib "eagle-import") (part "CAP0402"))
    )
    (comp (ref "C604")
      (value "0u47")
      (footprint "eagle-import:0402-CAP")
      (fields (field (name "PARTNO") "C1005X5R1C474K050BC"))
      (libsource (lib "eagle-import") (part "CAP0402"))
    )
    (comp (ref "D601")
      (value "PESD0402-140")
      (footprint "eagle-import:0402-TVS")
      (libsource (lib "eagle-import") (part "DIODE-TVS"))
    )
    (comp (ref "JP600")
      (value "JP1Q")
      (footprint "eagle-import:JP1")
      (fields (field (name "PARTNO") "1-87215-0"))
      (libsource (lib "eagle-import") (part "JP1Q"))
    )
    (comp (ref "L601")
      (value "47uH")
      (footprint "eagle-import:0805-IND")
      (fields (field (name "PARTNO") "MLZ2012M470W"))
      (libsource (lib "eagle-import") (part "INDUCTOR0805"))
    )
    (comp (ref "LED601")
      (value "GREEN")
      (footprint "eagle-import:0603-LED")
      (fields (field (name "PARTNO") "APTD1608CGCK"))
      (libsource (lib "eagle-import") (part "LED0603"))
    )
    (comp (ref "LED602")
      (value "AMBER")
      (footprint "eagle-import:0603-LED")
      (fields (field (name "PARTNO") "APTD1608SECK"))
      (libsource (lib "eagle-import") (part "LED0603"))
    )
    (comp (ref "LED603")
      (value "BLUE")
      (footprint "eagle-import:0603-LED")
      (fields (field (name "PARTNO") "APTD1608QBC/D"))
      (libsource (lib "eagle-import") (part "LED0603"))
    )
    (comp (ref "R602")
      (value "9K09")
      (footprint "eagle-import:0402-RES")
      (fields (field (name "PARTNO") "RMCF0402FT9K09"))
      (libsource (lib "eagle-import") (part "RESISTOR0402-RES"))
    )
    (comp (ref "R603")
      (value "10K")
      (footprint "eagle-import:0402-RES")
      (fields (field (name "PARTNO") "ERA-2AEB103X"))
      (libsource (lib "eagle-import") (part "RESISTOR0402-RES"))
    )
    (comp (ref "R604")
      (value "100K")
      (footprint "eagle-import:0402-RES")
      (fields (field (name "PARTNO") "RC0402FR-07100KL"))
      (libsource (lib "eagle-import") (part "RESISTOR0402-RES"))
    )
    (comp (ref "R606")
      (value "453K")
      (footprint "eagle-import:0402-RES")
      (fields (field (name "PARTNO") "RMCF0402FT453K"))
      (libsource (lib "eagle-import") (part "RESISTOR0402-RES"))
    )
    (comp (ref "R607")
      (value "16K5")
      (footprint "eagle-import:0402-RES")
      (fields (field (name "PARTNO") "RMCF0402FT16K5"))
      (libsource (lib "eagle-import") (part "RESISTOR0402-RES"))
    )
    (comp (ref "R608")
      (value "220R")
      (footprint "eagle-import:0402-RES")
      (fields (field (name "PARTNO") "RC0402FR-07220RL"))
      (libsource (lib "eagle-import") (part "RESISTOR0402-RES"))
    )
    (comp (ref "R609")
      (value "220R")
      (footprint "eagle-import:0402-RES")
      (fields (field (name "PARTNO") "RC0402FR-07220RL"))
      (libsource (lib "eagle-import") (part "RESISTOR0402-RES"))
    )
    (comp (ref "R610")
      (value "220R")
      (footprint "eagle-import:0402-RES")
      (fields (field (name "PARTNO") "RC0402FR-07220RL"))
      (libsource (lib "eagle-import") (part "RESISTOR0402-RES"))
    )
    (comp (ref "R611")
      (value "68R")
      (footprint "eagle-import:0402-RES")
      (fields (field (name "PARTNO") "RC0402FR-0768RL"))
      (libsource (lib "eagle-import") (part "RESISTOR0402-RES"))
    )
    (comp (ref "R612")
      (value "220R")
      (footprint "eagle-import:0402-RES")
      (fields (field (name "PARTNO") "RC0402FR-07220RL"))
      (libsource (lib "eagle-import") (part "RESISTOR0402-RES"))
    )
    (comp (ref "R613")
      (value "1K5")
      (footprint "eagle-import:0402-RES")
      (fields (field (name "PARTNO") "RC0402FR-071K5L"))
      (libsource (lib "eagle-import") (part "RESISTOR0402-RES"))
    )
    (comp (ref "R614")
      (value "100K")
      (footprint "eagle-import:0402-RES")
      (fields (field (name "PARTNO") "RC0402FR-07100KL"))
      (libsource (lib "eagle-import") (part "RESISTOR0402-RES"))
    )
    (comp (ref "U$11")
      (value "DF13-2P-1.25")
      (footprint "eagle-import:DF13C-2P-1.25V")
      (fields (field (name "PARTNO") "DF13C-2P-1.25V(20)"))
      (libsource (lib "eagle-import") (part "DF13-2P-1.25"))
    )
    (comp (ref "U$12")
      (value "DF13-3P-1.25V")
      (footprint "eagle-import:DF13C-3P-1.25V")
      (fields (field (name "PARTNO") "DF13C-3P-1.25V(20)"))
      (libsource (lib "eagle-import") (part "DF13-3P-1.25V"))
    )
    (comp (ref "U602")
      (value "LT3469")
      (footprint "eagle-import:SOT23-8")
      (fields (field (name "PARTNO") "LT3469ETS8"))
      (libsource (lib "eagle-import") (part "LT3469"))
    )
  )
  (nets
    (net (code "1") (name "3V3_EN") (class "Default")
      (node (ref "R102") (pin "P$2") (pinfunction "2_P$2") (pintype "passive"))
      (node (ref "R503") (pin "P$2") (pinfunction "2_P$2") (pintype "passive"))
      (node (ref "U$101") (pin "56") (pinfunction "SYS_RESETN_10_56") (pintype "passive"))
      (node (ref "U$101") (pin "73") (pinfunction "27_PRU1_R30/31[5]_73") (pintype "passive"))
      (node (ref "U502") (pin "4") (pinfunction "EN2_4") (pintype "bidirectional"))
      (node (ref "U502") (pin "5") (pinfunction "EN1_5") (pintype "bidirectional"))
    )
    (net (code "2") (name "3_VDD_3V3") (class "Default")
      (node (ref "U$101") (pin "49") (pinfunction "3_VDD_3V3_49") (pintype "power_in"))
    )
    (net (code "3") (name "ACCEL_DRDY") (class "Default")
      (node (ref "U$101") (pin "8") (pinfunction "GPIO2[3]_8_8") (pintype "passive"))
      (node (ref "U406") (pin "14") (pinfunction "INT2_XM_14") (pintype "bidirectional"))
    )
    (net (code "4") (name "ALARM") (class "Default")
      (node (ref "R602") (pin "P$2") (pinfunction "2_P$2") (pintype "passive"))
      (node (ref "U$101") (pin "36") (pinfunction "GPIO2[16]_36_36") (pintype "passive"))
    )
    (net (code "5") (name "AUX_ADC1") (class "Default")
      (node (ref "R308") (pin "P$1") (pinfunction "1_P$1") (pintype "passive"))
      (node (ref "U$101") (pin "83") (pinfunction "37_AIN2_83") (pintype "passive"))
    )
    (net (code "6") (name "AUX_ADC2") (class "Default")
      (node (ref "R307") (pin "P$1") (pinfunction "1_P$1") (pintype "passive"))
      (node (ref "U$101") (pin "84") (pinfunction "AIN3_38_84") (pintype "passive"))
    )
    (net (code "7") (name "BACKUP_LIPO_+_1S") (class "Default")
      (node (ref "U$101") (pin "TP5") (pinfunction "BAT_+_LIPO_1_S_TP5") (pintype "bidirectional"))
      (node (ref "X801") (pin "1") (pinfunction "S_1") (pintype "passive"))
    )
    (net (code "8") (name "BATT_CURRENT_SENS") (class "Default")
      (node (ref "R1") (pin "P$1") (pinfunction "1_P$1") (pintype "passive"))
      (node (ref "R808") (pin "P$1") (pinfunction "1_P$1") (pintype "passive"))
      (node (ref "U$101") (pin "81") (pinfunction "35_AIN6_81") (pintype "passive"))
    )
    (net (code "9") (name "BATT_SENSE") (class "Default")
      (node (ref "U$101") (pin "TP6") (pinfunction "BAT_SENSE_TP6") (pintype "bidirectional"))
      (node (ref "X801") (pin "2") (pinfunction "S_2") (pintype "passive"))
    )
    (net (code "10") (name "BATT_TEMP_SENSE") (class "Default")
      (node (ref "U$101") (pin "TP7") (pinfunction "TEMP_SENSE_TP7") (pintype "bidirectional"))
      (node (ref "X801") (pin "3") (pinfunction "S_3") (pintype "passive"))
    )
    (net (code "11") (name "BATT_VOLTAGE_SENS") (class "Default")
      (node (ref "R2") (pin "P$1") (pinfunction "1_P$1") (pintype "passive"))
      (node (ref "R807") (pin "P$1") (pinfunction "1_P$1") (pintype "passive"))
      (node (ref "U$101") (pin "82") (pinfunction "AIN5_36_82") (pintype "passive"))
    )
    (net (code "12") (name "BBB-VDD_3V3") (class "Default")
      (node (ref "C201") (pin "P$1") (pinfunction "1_P$1") (pintype "passive"))
      (node (ref "C302") (pin "P$1") (pinfunction "1_P$1") (pintype "passive"))
      (node (ref "C303") (pin "P$1") (pinfunction "1_P$1") (pintype "passive"))
      (node (ref "C304") (pin "P$1") (pinfunction "1_P$1") (pintype "passive"))
      (node (ref "C505") (pin "P$1") (pinfunction "1_P$1") (pintype "passive"))
      (node (ref "C506") (pin "P$1") (pinfunction "1_P$1") (pintype "passive"))
      (node (ref "C507") (pin "P$1") (pinfunction "1_P$1") (pintype "passive"))
      (node (ref "C702") (pin "P$1") (pinfunction "1_P$1") (pintype "passive"))
      (node (ref "C703") (pin "P$1") (pinfunction "1_P$1") (pintype "passive"))
      (node (ref "D601") (pin "C") (pinfunction "C_C") (pintype "passive"))
      (node (ref "JP1") (pin "2") (pinfunction "2_2") (pintype "passive"))
      (node (ref "R215") (pin "P$2") (pinfunction "2_P$2") (pintype "passive"))
      (node (ref "R301") (pin "P$2") (pinfunction "2_P$2") (pintype "passive"))
      (node (ref "R302") (pin "P$2") (pinfunction "2_P$2") (pintype "passive"))
      (node (ref "R304") (pin "P$1") (pinfunction "1_P$1") (pintype "passive"))
      (node (ref "R305") (pin "P$1") (pinfunction "1_P$1") (pintype "passive"))
      (node (ref "R314") (pin "P$2") (pinfunction "2_P$2") (pintype "passive"))
      (node (ref "R502") (pin "P$2") (pinfunction "2_P$2") (pintype "passive"))
      (node (ref "R507") (pin "P$2") (pinfunction "2_P$2") (pintype "passive"))
      (node (ref "R718") (pin "P$2") (pinfunction "2_P$2") (pintype "passive"))
      (node (ref "R719") (pin "P$2") (pinfunction "2_P$2") (pintype "passive"))
      (node (ref "U$12") (pin "1") (pinfunction "1_1") (pintype "passive"))
      (node (ref "U201") (pin "19") (pinfunction "VCCB_19") (pintype "input"))
      (node (ref "U201") (pin "2") (pinfunction "VCCA_2") (pintype "input"))
      (node (ref "U301") (pin "3") (pinfunction "VCC_3") (pintype "input"))
      (node (ref "U302") (pin "10") (pinfunction "OE_10") (pintype "input"))
      (node (ref "U302") (pin "2") (pinfunction "VCCA_2") (pintype "input"))
      (node (ref "U303") (pin "2") (pinfunction "VREF1_2") (pintype "bidirectional"))
      (node (ref "U303") (pin "7") (pinfunction "VREF2_7") (pintype "bidirectional"))
      (node (ref "U303") (pin "8") (pinfunction "EN_8") (pintype "bidirectional"))
      (node (ref "U502") (pin "7") (pinfunction "VOUT2_7") (pintype "bidirectional"))
      (node (ref "U701") (pin "19") (pinfunction "VCCB_19") (pintype "input"))
      (node (ref "U701") (pin "2") (pinfunction "VCCA_2") (pintype "input"))
      (node (ref "U702") (pin "19") (pinfunction "VCCB_19") (pintype "input"))
      (node (ref "U702") (pin "2") (pinfunction "VCCA_2") (pintype "input"))
      (node (ref "VDD_3V901") (pin "P$1") (pinfunction "P$1_P$1") (pintype "passive"))
    )
    (net (code "13") (name "CAN1_RX_1") (class "Default")
      (node (ref "U$101") (pin "70") (pinfunction "UART1/CAN1_TXD_24_70") (pintype "passive"))
      (node (ref "U301") (pin "4") (pinfunction "DOUT_4") (pintype "output"))
    )
    (net (code "14") (name "CAN1_TX_1") (class "Default")
      (node (ref "U$101") (pin "72") (pinfunction "UART1/CAN1_RXD_26_72") (pintype "passive"))
      (node (ref "U301") (pin "1") (pinfunction "DIN_1") (pintype "input"))
    )
    (net (code "15") (name "CAN_H") (class "Default")
      (node (ref "CAN_H") (pin "P$1") (pinfunction "P$1_P$1") (pintype "passive"))
      (node (ref "J307") (pin "2") (pinfunction "2_2") (pintype "passive"))
      (node (ref "R309") (pin "P$1") (pinfunction "1_P$1") (pintype "passive"))
      (node (ref "U301") (pin "7") (pinfunction "CANH_7") (pintype "bidirectional"))
    )
    (net (code "16") (name "CAN_L") (class "Default")
      (node (ref "CAN_L") (pin "P$1") (pinfunction "P$1_P$1") (pintype "passive"))
      (node (ref "J307") (pin "3") (pinfunction "3_3") (pintype "passive"))
      (node (ref "R309") (pin "P$2") (pinfunction "2_P$2") (pintype "passive"))
      (node (ref "U301") (pin "6") (pinfunction "CANL_6") (pintype "bidirectional"))
    )
    (net (code "17") (name "CH_1") (class "Default")
      (node (ref "U$101") (pin "28") (pinfunction "PRU1_R30/31[10]_28_28") (pintype "passive"))
      (node (ref "U701") (pin "5") (pinfunction "A4_5") (pintype "bidirectional"))
    )
    (net (code "18") (name "CH_1_OUT") (class "Default")
      (node (ref "R714") (pin "P$1") (pinfunction "1_P$1") (pintype "passive"))
      (node (ref "U701") (pin "16") (pinfunction "B4_16") (pintype "bidirectional"))
    )
    (net (code "19") (name "CH_2") (class "Default")
      (node (ref "U$101") (pin "27") (pinfunction "27_PRU1_R30/31[8]_27") (pintype "passive"))
      (node (ref "U701") (pin "4") (pinfunction "A3_4") (pintype "bidirectional"))
    )
    (net (code "20") (name "CH_2_OUT") (class "Default")
      (node (ref "R713") (pin "P$1") (pinfunction "1_P$1") (pintype "passive"))
      (node (ref "U701") (pin "17") (pinfunction "B3_17") (pintype "bidirectional"))
    )
    (net (code "21") (name "CH_3") (class "Default")
      (node (ref "U$101") (pin "30") (pinfunction "PRU1_R30/31[11]_30_30") (pintype "passive"))
      (node (ref "U701") (pin "3") (pinfunction "A2_3") (pintype "bidirectional"))
    )
    (net (code "22") (name "CH_3_OUT") (class "Default")
      (node (ref "R712") (pin "P$1") (pinfunction "1_P$1") (pintype "passive"))
      (node (ref "U701") (pin "18") (pinfunction "B2_18") (pintype "bidirectional"))
    )
    (net (code "23") (name "CH_4") (class "Default")
      (node (ref "U$101") (pin "29") (pinfunction "29_PRU1_R30/31[9]_29") (pintype "passive"))
      (node (ref "U701") (pin "1") (pinfunction "A1_1") (pintype "bidirectional"))
    )
    (net (code "24") (name "CH_4_OUT") (class "Default")
      (node (ref "R701") (pin "P$1") (pinfunction "1_P$1") (pintype "passive"))
      (node (ref "U701") (pin "20") (pinfunction "B1_20") (pintype "bidirectional"))
    )
    (net (code "25") (name "CH_5") (class "Default")
      (node (ref "U$101") (pin "40") (pinfunction "PRU1_R30/31[7]_40_40") (pintype "passive"))
      (node (ref "U702") (pin "9") (pinfunction "A8_9") (pintype "bidirectional"))
    )
    (net (code "26") (name "CH_5_OUT") (class "Default")
      (node (ref "R702") (pin "P$1") (pinfunction "1_P$1") (pintype "passive"))
      (node (ref "U702") (pin "12") (pinfunction "B8_12") (pintype "bidirectional"))
    )
    (net (code "27") (name "CH_6") (class "Default")
      (node (ref "U$101") (pin "39") (pinfunction "39_PRU1_R30/31[6]_39") (pintype "passive"))
      (node (ref "U702") (pin "8") (pinfunction "A7_8") (pintype "bidirectional"))
    )
    (net (code "28") (name "CH_6_OUT") (class "Default")
      (node (ref "R703") (pin "P$1") (pinfunction "1_P$1") (pintype "passive"))
      (node (ref "U702") (pin "13") (pinfunction "B7_13") (pintype "bidirectional"))
    )
    (net (code "29") (name "CH_7") (class "Default")
      (node (ref "U$101") (pin "42") (pinfunction "PRU1_R30/31[5]_42_42") (pintype "passive"))
      (node (ref "U702") (pin "7") (pinfunction "A6_7") (pintype "bidirectional"))
    )
    (net (code "30") (name "CH_7_OUT") (class "Default")
      (node (ref "R704") (pin "P$1") (pinfunction "1_P$1") (pintype "passive"))
      (node (ref "U702") (pin "14") (pinfunction "B6_14") (pintype "bidirectional"))
    )
    (net (code "31") (name "CH_8") (class "Default")
      (node (ref "U$101") (pin "41") (pinfunction "41_PRU1_R30/31[4]_41") (pintype "passive"))
      (node (ref "U702") (pin "6") (pinfunction "A5_6") (pintype "bidirectional"))
    )
    (net (code "32") (name "CH_8_OUT") (class "Default")
      (node (ref "R705") (pin "P$1") (pinfunction "1_P$1") (pintype "passive"))
      (node (ref "U702") (pin "15") (pinfunction "B5_15") (pintype "bidirectional"))
    )
    (net (code "33") (name "CH_9") (class "Default")
      (node (ref "U$101") (pin "44") (pinfunction "PRU1_R30/31[3]_44_44") (pintype "passive"))
      (node (ref "U702") (pin "5") (pinfunction "A4_5") (pintype "bidirectional"))
    )
    (net (code "34") (name "CH_9_OUT") (class "Default")
      (node (ref "R706") (pin "P$1") (pinfunction "1_P$1") (pintype "passive"))
      (node (ref "U702") (pin "16") (pinfunction "B4_16") (pintype "bidirectional"))
    )
    (net (code "35") (name "CH_10") (class "Default")
      (node (ref "U$101") (pin "43") (pinfunction "43_PRU1_R30/31[2]_43") (pintype "passive"))
      (node (ref "U702") (pin "4") (pinfunction "A3_4") (pintype "bidirectional"))
    )
    (net (code "36") (name "CH_10_OUT") (class "Default")
      (node (ref "R707") (pin "P$1") (pinfunction "1_P$1") (pintype "passive"))
      (node (ref "U702") (pin "17") (pinfunction "B3_17") (pintype "bidirectional"))
    )
    (net (code "37") (name "CH_11") (class "Default")
      (node (ref "U$101") (pin "46") (pinfunction "PRU1_R30/31[1]_46_46") (pintype "passive"))
      (node (ref "U702") (pin "3") (pinfunction "A2_3") (pintype "bidirectional"))
    )
    (net (code "38") (name "CH_11_OUT") (class "Default")
      (node (ref "R708") (pin "P$1") (pinfunction "1_P$1") (pintype "passive"))
      (node (ref "U702") (pin "18") (pinfunction "B2_18") (pintype "bidirectional"))
    )
    (net (code "39") (name "CH_12") (class "Default")
      (node (ref "U$101") (pin "45") (pinfunction "45_PRU1_R30/31[0]_45") (pintype "passive"))
      (node (ref "U702") (pin "1") (pinfunction "A1_1") (pintype "bidirectional"))
    )
    (net (code "40") (name "CH_12_OUT") (class "Default")
      (node (ref "R709") (pin "P$1") (pinfunction "1_P$1") (pintype "passive"))
      (node (ref "U702") (pin "20") (pinfunction "B1_20") (pintype "bidirectional"))
    )
    (net (code "41") (name "GND") (class "Default")
      (node (ref "C101") (pin "P$2") (pinfunction "2_P$2") (pintype "passive"))
      (node (ref "C201") (pin "P$2") (pinfunction "2_P$2") (pintype "passive"))
      (node (ref "C301") (pin "P$2") (pinfunction "2_P$2") (pintype "passive"))
      (node (ref "C302") (pin "P$2") (pinfunction "2_P$2") (pintype "passive"))
      (node (ref "C303") (pin "P$2") (pinfunction "2_P$2") (pintype "passive"))
      (node (ref "C304") (pin "P$2") (pinfunction "2_P$2") (pintype "passive"))
      (node (ref "C305") (pin "P$2") (pinfunction "2_P$2") (pintype "passive"))
      (node (ref "C401") (pin "P$2") (pinfunction "2_P$2") (pintype "passive"))
      (node (ref "C402") (pin "P$2") (pinfunction "2_P$2") (pintype "passive"))
      (node (ref "C405") (pin "P$1") (pinfunction "1_P$1") (pintype "passive"))
      (node (ref "C406") (pin "P$1") (pinfunction "1_P$1") (pintype "passive"))
      (node (ref "C407") (pin "P$2") (pinfunction "2_P$2") (pintype "passive"))
      (node (ref "C408") (pin "P$2") (pinfunction "2_P$2") (pintype "passive"))
      (node (ref "C409") (pin "P$2") (pinfunction "2_P$2") (pintype "passive"))
      (node (ref "C410") (pin "P$2") (pinfunction "2_P$2") (pintype "passive"))
      (node (ref "C411") (pin "P$2") (pinfunction "2_P$2") (pintype "passive"))
      (node (ref "C412") (pin "P$2") (pinfunction "2_P$2") (pintype "passive"))
      (node (ref "C413") (pin "P$2") (pinfunction "2_P$2") (pintype "passive"))
      (node (ref "C414") (pin "P$2") (pinfunction "2_P$2") (pintype "passive"))
      (node (ref "C415") (pin "P$2") (pinfunction "2_P$2") (pintype "passive"))
      (node (ref "C416") (pin "P$2") (pinfunction "2_P$2") (pintype "passive"))
      (node (ref "C501") (pin "P$2") (pinfunction "2_P$2") (pintype "passive"))
      (node (ref "C502") (pin "P$2") (pinfunction "2_P$2") (pintype "passive"))
      (node (ref "C503") (pin "P$2") (pinfunction "2_P$2") (pintype "passive"))
      (node (ref "C504") (pin "P$2") (pinfunction "2_P$2") (pintype "passive"))
      (node (ref "C505") (pin "P$2") (pinfunction "2_P$2") (pintype "passive"))
      (node (ref "C506") (pin "P$2") (pinfunction "2_P$2") (pintype "passive"))
      (node (ref "C507") (pin "P$2") (pinfunction "2_P$2") (pintype "passive"))
      (node (ref "C508") (pin "P$2") (pinfunction "2_P$2") (pintype "passive"))
      (node (ref "C509") (pin "P$2") (pinfunction "2_P$2") (pintype "passive"))
      (node (ref "C510") (pin "P$2") (pinfunction "2_P$2") (pintype "passive"))
      (node (ref "C602") (pin "P$2") (pinfunction "2_P$2") (pintype "passive"))
      (node (ref "C603") (pin "P$2") (pinfunction "2_P$2") (pintype "passive"))
      (node (ref "C604") (pin "P$2") (pinfunction "2_P$2") (pintype "passive"))
      (node (ref "C702") (pin "P$2") (pinfunction "2_P$2") (pintype "passive"))
      (node (ref "C703") (pin "P$2") (pinfunction "2_P$2") (pintype "passive"))
      (node (ref "C801") (pin "P$2") (pinfunction "2_P$2") (pintype "passive"))
      (node (ref "C805") (pin "P$2") (pinfunction "2_P$2") (pintype "passive"))
      (node (ref "D201") (pin "A") (pinfunction "A_A") (pintype "passive"))
      (node (ref "D202") (pin "A") (pinfunction "A_A") (pintype "passive"))
      (node (ref "D203") (pin "A") (pinfunction "A_A") (pintype "passive"))
      (node (ref "D301") (pin "A") (pinfunction "A_A") (pintype "passive"))
      (node (ref "D302") (pin "A") (pinfunction "A_A") (pintype "passive"))
      (node (ref "D303") (pin "A") (pinfunction "A_A") (pintype "passive"))
      (node (ref "D601") (pin "A") (pinfunction "A_A") (pintype "passive"))
      (node (ref "D703") (pin "A") (pinfunction "A_A") (pintype "passive"))
      (node (ref "D706") (pin "A") (pinfunction "A_A") (pintype "passive"))
      (node (ref "GND") (pin "P$1") (pinfunction "P$1_P$1") (pintype "passive"))
      (node (ref "GND.") (pin "P$1") (pinfunction "P$1_P$1") (pintype "passive"))
      (node (ref "J305") (pin "3") (pinfunction "3_3") (pintype "passive"))
      (node (ref "J305") (pin "P$4") (pinfunction "P$1_P$4") (pintype "bidirectional"))
      (node (ref "J305") (pin "P$5") (pinfunction "P$2_P$5") (pintype "bidirectional"))
      (node (ref "J306") (pin "4") (pinfunction "4_4") (pintype "passive"))
      (node (ref "J306") (pin "P$5") (pinfunction "P$1_P$5") (pintype "bidirectional"))
      (node (ref "J306") (pin "P$6") (pinfunction "P$2_P$6") (pintype "bidirectional"))
      (node (ref "J307") (pin "4") (pinfunction "4_4") (pintype "passive"))
      (node (ref "J307") (pin "P$5") (pinfunction "P$1_P$5") (pintype "bidirectional"))
      (node (ref "J307") (pin "P$6") (pinfunction "P$2_P$6") (pintype "bidirectional"))
      (node (ref "J308") (pin "4") (pinfunction "4_4") (pintype "passive"))
      (node (ref "J308") (pin "P$5") (pinfunction "P$1_P$5") (pintype "bidirectional"))
      (node (ref "J308") (pin "P$6") (pinfunction "P$2_P$6") (pintype "bidirectional"))
      (node (ref "J309") (pin "3") (pinfunction "3_3") (pintype "passive"))
      (node (ref "J309") (pin "5") (pinfunction "5_5") (pintype "passive"))
      (node (ref "J309") (pin "P$6") (pinfunction "P$1_P$6") (pintype "bidirectional"))
      (node (ref "J309") (pin "P$7") (pinfunction "P$2_P$7") (pintype "bidirectional"))
      (node (ref "J310") (pin "4") (pinfunction "4_4") (pintype "passive"))
      (node (ref "J310") (pin "P$5") (pinfunction "P$1_P$5") (pintype "bidirectional"))
      (node (ref "J310") (pin "P$6") (pinfunction "P$2_P$6") (pintype "bidirectional"))
      (node (ref "J314") (pin "4") (pinfunction "4_4") (pintype "passive"))
      (node (ref "J314") (pin "P$5") (pinfunction "P$1_P$5") (pintype "bidirectional"))
      (node (ref "J314") (pin "P$6") (pinfunction "P$2_P$6") (pintype "bidirectional"))
      (node (ref "J701") (pin "P$2") (pinfunction "P$2_P$2") (pintype "bidirectional"))
      (node (ref "J801") (pin "5") (pinfunction "5_5") (pintype "passive"))
      (node (ref "J801") (pin "6") (pinfunction "6_6") (pintype "passive"))
      (node (ref "L201") (pin "P$3") (pinfunction "P$3_P$3") (pintype "bidirectional"))
      (node (ref "L201") (pin "P$4") (pinfunction "P$3_P$4") (pintype "bidirectional"))
      (node (ref "L201") (pin "P$5") (pinfunction "P$3_P$5") (pintype "bidirectional"))
      (node (ref "L202") (pin "P$3") (pinfunction "P$3_P$3") (pintype "bidirectional"))
      (node (ref "L202") (pin "P$4") (pinfunction "P$3_P$4") (pintype "bidirectional"))
      (node (ref "L202") (pin "P$5") (pinfunction "P$3_P$5") (pintype "bidirectional"))
      (node (ref "L203") (pin "P$3") (pinfunction "P$3_P$3") (pintype "bidirectional"))
      (node (ref "L203") (pin "P$4") (pinfunction "P$3_P$4") (pintype "bidirectional"))
      (node (ref "L203") (pin "P$5") (pinfunction "P$3_P$5") (pintype "bidirectional"))
      (node (ref "L301") (pin "P$3") (pinfunction "P$3_P$3") (pintype "bidirectional"))
      (node (ref "L301") (pin "P$4") (pinfunction "P$3_P$4") (pintype "bidirectional"))
      (node (ref "L301") (pin "P$5") (pinfunction "P$3_P$5") (pintype "bidirectional"))
      (node (ref "L302") (pin "P$3") (pinfunction "P$3_P$3") (pintype "bidirectional"))
      (node (ref "L302") (pin "P$4") (pinfunction "P$3_P$4") (pintype "bidirectional"))
      (node (ref "L302") (pin "P$5") (pinfunction "P$3_P$5") (pintype "bidirectional"))
      (node (ref "L303") (pin "P$3") (pinfunction "P$3_P$3") (pintype "bidirectional"))
      (node (ref "L303") (pin "P$4") (pinfunction "P$3_P$4") (pintype "bidirectional"))
      (node (ref "L303") (pin "P$5") (pinfunction "P$3_P$5") (pintype "bidirectional"))
      (node (ref "L501") (pin "P$3") (pinfunction "P$3_P$3") (pintype "bidirectional"))
      (node (ref "L501") (pin "P$4") (pinfunction "P$3_P$4") (pintype "bidirectional"))
      (node (ref "L501") (pin "P$5") (pinfunction "P$3_P$5") (pintype "bidirectional"))
      (node (ref "L701") (pin "P$3") (pinfunction "P$3_P$3") (pintype "bidirectional"))
      (node (ref "L701") (pin "P$4") (pinfunction "P$3_P$4") (pintype "bidirectional"))
      (node (ref "L701") (pin "P$5") (pinfunction "P$3_P$5") (pintype "bidirectional"))
      (node (ref "L801") (pin "P$3") (pinfunction "P$3_P$3") (pintype "bidirectional"))
      (node (ref "L801") (pin "P$4") (pinfunction "P$3_P$4") (pintype "bidirectional"))
      (node (ref "L801") (pin "P$5") (pinfunction "P$3_P$5") (pintype "bidirectional"))
      (node (ref "L802") (pin "P$3") (pinfunction "P$3_P$3") (pintype "bidirectional"))
      (node (ref "L802") (pin "P$4") (pinfunction "P$3_P$4") (pintype "bidirectional"))
      (node (ref "L802") (pin "P$5") (pinfunction "P$3_P$5") (pintype "bidirectional"))
      (node (ref "R102") (pin "P$1") (pinfunction "1_P$1") (pintype "passive"))
      (node (ref "R215") (pin "P$1") (pinfunction "1_P$1") (pintype "passive"))
      (node (ref "R303") (pin "P$1") (pinfunction "1_P$1") (pintype "passive"))
      (node (ref "R310") (pin "P$1") (pinfunction "1_P$1") (pintype "passive"))
      (node (ref "R311") (pin "P$1") (pinfunction "1_P$1") (pintype "passive"))
      (node (ref "R314") (pin "P$1") (pinfunction "1_P$1") (pintype "passive"))
      (node (ref "R315") (pin "P$2") (pinfunction "2_P$2") (pintype "passive"))
      (node (ref "R501") (pin "P$2") (pinfunction "2_P$2") (pintype "passive"))
      (node (ref "R504") (pin "P$2") (pinfunction "2_P$2") (pintype "passive"))
      (node (ref "R505") (pin "1") (pinfunction "1_1") (pintype "passive"))
      (node (ref "R506") (pin "P$2") (pinfunction "2_P$2") (pintype "passive"))
      (node (ref "R509") (pin "P$2") (pinfunction "2_P$2") (pintype "passive"))
      (node (ref "R603") (pin "P$2") (pinfunction "2_P$2") (pintype "passive"))
      (node (ref "R607") (pin "P$2") (pinfunction "2_P$2") (pintype "passive"))
      (node (ref "R608") (pin "P$1") (pinfunction "1_P$1") (pintype "passive"))
      (node (ref "R613") (pin "P$2") (pinfunction "2_P$2") (pintype "passive"))
      (node (ref "R716") (pin "P$1") (pinfunction "1_P$1") (pintype "passive"))
      (node (ref "R718") (pin "P$1") (pinfunction "1_P$1") (pintype "passive"))
      (node (ref "R719") (pin "P$1") (pinfunction "1_P$1") (pintype "passive"))
      (node (ref "R8") (pin "P$1") (pinfunction "1_P$1") (pintype "passive"))
      (node (ref "R801") (pin "P$2") (pinfunction "2_P$2") (pintype "passive"))
      (node (ref "R802") (pin "P$2") (pinfunction "2_P$2") (pintype "passive"))
      (node (ref "R806") (pin "P$1") (pinfunction "1_P$1") (pintype "passive"))
      (node (ref "R807") (pin "P$2") (pinfunction "2_P$2") (pintype "passive"))
      (node (ref "R808") (pin "P$2") (pinfunction "2_P$2") (pintype "passive"))
      (node (ref "U$101") (pin "1") (pinfunction "1_GND_1") (pintype "power_in"))
      (node (ref "U$101") (pin "2") (pinfunction "GND_2_2") (pintype "power_in"))
      (node (ref "U$101") (pin "47") (pinfunction "1_GND_47") (pintype "power_in"))
      (node (ref "U$101") (pin "48") (pinfunction "GND_2_48") (pintype "power_in"))
      (node (ref "U$101") (pin "80") (pinfunction "GNDA_ADC_34_80") (pintype "passive"))
      (node (ref "U$101") (pin "89") (pinfunction "43_GND_89") (pintype "power_in"))
      (node (ref "U$101") (pin "90") (pinfunction "GND_44_90") (pintype "power_in"))
      (node (ref "U$101") (pin "91") (pinfunction "45_GND_91") (pintype "power_in"))
      (node (ref "U$101") (pin "92") (pinfunction "GND_46_92") (pintype "power_in"))
      (node (ref "U$101") (pin "93") (pinfunction "GND_93") (pintype "bidirectional"))
      (node (ref "U$101") (pin "P$1") (pinfunction "SCREW$1_P$1") (pintype "bidirectional"))
      (node (ref "U$101") (pin "P$2") (pinfunction "SCREW$2_P$2") (pintype "bidirectional"))
      (node (ref "U$101") (pin "P$3") (pinfunction "SCREW$3_P$3") (pintype "bidirectional"))
      (node (ref "U$101") (pin "P$4") (pinfunction "SCREW$4_P$4") (pintype "bidirectional"))
      (node (ref "U$101") (pin "TP8") (pinfunction "BATT_GND_TP8") (pintype "bidirectional"))
      (node (ref "U$11") (pin "2") (pinfunction "2_2") (pintype "passive"))
      (node (ref "U$11") (pin "P$3") (pinfunction "P$1_P$3") (pintype "bidirectional"))
      (node (ref "U$11") (pin "P$4") (pinfunction "P$2_P$4") (pintype "bidirectional"))
      (node (ref "U$12") (pin "P$4") (pinfunction "P$1_P$4") (pintype "bidirectional"))
      (node (ref "U$12") (pin "P$5") (pinfunction "P$2_P$5") (pintype "bidirectional"))
      (node (ref "U$2") (pin "6") (pinfunction "6_6") (pintype "passive"))
      (node (ref "U$2") (pin "P$7") (pinfunction "P$1_P$7") (pintype "bidirectional"))
      (node (ref "U$2") (pin "P$8") (pinfunction "P$2_P$8") (pintype "bidirectional"))
      (node (ref "U$201") (pin "6") (pinfunction "6_6") (pintype "passive"))
      (node (ref "U$201") (pin "P$7") (pinfunction "P$1_P$7") (pintype "bidirectional"))
      (node (ref "U$201") (pin "P$8") (pinfunction "P$2_P$8") (pintype "bidirectional"))
      (node (ref "U$4") (pin "6") (pinfunction "6_6") (pintype "passive"))
      (node (ref "U$4") (pin "P$7") (pinfunction "P$1_P$7") (pintype "bidirectional"))
      (node (ref "U$4") (pin "P$8") (pinfunction "P$2_P$8") (pintype "bidirectional"))
      (node (ref "U1") (pin "1") (pinfunction "A0_1") (pintype "bidirectional"))
      (node (ref "U1") (pin "2") (pinfunction "A1_2") (pintype "bidirectional"))
      (node (ref "U1") (pin "4") (pinfunction "VSS_4") (pintype "power_in"))
      (node (ref "U102") (pin "4") (pinfunction "VSS_4") (pintype "bidirectional"))
      (node (ref "U2") (pin "4") (pinfunction "VSS_4") (pintype "power_in"))
      (node (ref "U201") (pin "11") (pinfunction "GND_11") (pintype "power_in"))
      (node (ref "U301") (pin "2") (pinfunction "GND_2") (pintype "power_in"))
      (node (ref "U301") (pin "5") (pinfunction "SHDN_5") (pintype "input"))
      (node (ref "U302") (pin "11") (pinfunction "GND_11") (pintype "power_in"))
      (node (ref "U303") (pin "1") (pinfunction "GND_1") (pintype "bidirectional"))
      (node (ref "U401") (pin "2") (pinfunction "PS_2") (pintype "bidirectional"))
      (node (ref "U401") (pin "3") (pinfunction "GND_3") (pintype "bidirectional"))
      (node (ref "U403") (pin "1") (pinfunction "CLKIN_1") (pintype "bidirectional"))
      (node (ref "U403") (pin "11") (pinfunction "FSYNC_11") (pintype "bidirectional"))
      (node (ref "U403") (pin "18") (pinfunction "GND_18") (pintype "bidirectional"))
      (node (ref "U405") (pin "11") (pinfunction "FSYNC_11") (pintype "bidirectional"))
      (node (ref "U405") (pin "18") (pinfunction "GND_18") (pintype "bidirectional"))
      (node (ref "U405") (pin "20") (pinfunction "RESV_20") (pintype "bidirectional"))
      (node (ref "U406") (pin "2") (pinfunction "GND_2") (pintype "bidirectional"))
      (node (ref "U406") (pin "3") (pinfunction "GND_3") (pintype "bidirectional"))
      (node (ref "U406") (pin "4") (pinfunction "GND_4") (pintype "bidirectional"))
      (node (ref "U406") (pin "5") (pinfunction "GND_5") (pintype "bidirectional"))
      (node (ref "U406") (pin "6") (pinfunction "GND_6") (pintype "bidirectional"))
      (node (ref "U501") (pin "2") (pinfunction "VSS_2") (pintype "bidirectional"))
      (node (ref "U501") (pin "6") (pinfunction "VBAT_6") (pintype "bidirectional"))
      (node (ref "U501") (pin "GND") (pinfunction "VSS_GND") (pintype "bidirectional"))
      (node (ref "U501") (pin "P$2") (pinfunction "VSS_P$2") (pintype "bidirectional"))
      (node (ref "U501") (pin "P$3") (pinfunction "VSS_P$3") (pintype "bidirectional"))
      (node (ref "U502") (pin "2") (pinfunction "GND_2") (pintype "bidirectional"))
      (node (ref "U502") (pin "GND") (pinfunction "GND_GND") (pintype "bidirectional"))
      (node (ref "U503") (pin "2") (pinfunction "VSS_2") (pintype "bidirectional"))
      (node (ref "U503") (pin "6") (pinfunction "VBAT_6") (pintype "bidirectional"))
      (node (ref "U503") (pin "GND") (pinfunction "VSS_GND") (pintype "bidirectional"))
      (node (ref "U503") (pin "P$2") (pinfunction "VSS_P$2") (pintype "bidirectional"))
      (node (ref "U503") (pin "P$3") (pinfunction "VSS_P$3") (pintype "bidirectional"))
      (node (ref "U602") (pin "4") (pinfunction "GND_4") (pintype "power_in"))
      (node (ref "U701") (pin "11") (pinfunction "GND_11") (pintype "power_in"))
      (node (ref "U702") (pin "11") (pinfunction "GND_11") (pintype "power_in"))
      (node (ref "U704") (pin "12") (pinfunction "GND_12") (pintype "bidirectional"))
      (node (ref "U704") (pin "15") (pinfunction "GND_15") (pintype "bidirectional"))
      (node (ref "U704") (pin "18") (pinfunction "GND_18") (pintype "bidirectional"))
      (node (ref "U704") (pin "21") (pinfunction "GND_21") (pintype "bidirectional"))
      (node (ref "U704") (pin "24") (pinfunction "GND_24") (pintype "bidirectional"))
      (node (ref "U704") (pin "27") (pinfunction "GND_27") (pintype "bidirectional"))
      (node (ref "U704") (pin "3") (pinfunction "GND_3") (pintype "bidirectional"))
      (node (ref "U704") (pin "30") (pinfunction "GND_30") (pintype "bidirectional"))
      (node (ref "U704") (pin "33") (pinfunction "GND_33") (pintype "bidirectional"))
      (node (ref "U704") (pin "36") (pinfunction "GND_36") (pintype "bidirectional"))
      (node (ref "U704") (pin "39") (pinfunction "GND_39") (pintype "bidirectional"))
      (node (ref "U704") (pin "42") (pinfunction "GND_42") (pintype "bidirectional"))
      (node (ref "U704") (pin "6") (pinfunction "GND_6") (pintype "bidirectional"))
      (node (ref "U704") (pin "9") (pinfunction "GND_9") (pintype "bidirectional"))
      (node (ref "U802") (pin "2") (pinfunction "GND_2") (pintype "bidirectional"))
      (node (ref "U802") (pin "4") (pinfunction "EN2_4") (pintype "bidirectional"))
      (node (ref "U802") (pin "GND") (pinfunction "GND_GND") (pintype "bidirectional"))
      (node (ref "X801") (pin "4") (pinfunction "S_4") (pintype "passive"))
    )
    (net (code "42") (name "GYRO_DRDY") (class "Default")
      (node (ref "U$101") (pin "34") (pinfunction "GPOI2[17]_34_34") (pintype "passive"))
      (node (ref "U406") (pin "12") (pinfunction "DRDY_G_12") (pintype "bidirectional"))
    )
    (net (code "43") (name "I2C2_SCL") (class "Default")
      (node (ref "R301") (pin "P$1") (pinfunction "1_P$1") (pintype "passive"))
      (node (ref "U$101") (pin "65") (pinfunction "19_I2C2_SCL_65") (pintype "passive"))
      (node (ref "U1") (pin "6") (pinfunction "SCL_6") (pintype "bidirectional"))
      (node (ref "U2") (pin "6") (pinfunction "SCL_6") (pintype "bidirectional"))
      (node (ref "U303") (pin "3") (pinfunction "SCL1_3") (pintype "bidirectional"))
    )
    (net (code "44") (name "I2C2_SDA") (class "Default")
      (node (ref "R302") (pin "P$1") (pinfunction "1_P$1") (pintype "passive"))
      (node (ref "U$101") (pin "66") (pinfunction "I2C2_SDA_20_66") (pintype "passive"))
      (node (ref "U1") (pin "5") (pinfunction "SDA_5") (pintype "bidirectional"))
      (node (ref "U2") (pin "5") (pinfunction "SDA_5") (pintype "bidirectional"))
      (node (ref "U303") (pin "4") (pinfunction "SDA1_4") (pintype "bidirectional"))
    )
    (net (code "45") (name "MAG_DRDY") (class "Default")
      (node (ref "U$101") (pin "10") (pinfunction "GPIO2[4]_10_10") (pintype "passive"))
      (node (ref "U406") (pin "13") (pinfunction "INT1_XM_13") (pintype "bidirectional"))
    )
    (net (code "46") (name "MPU_6000_DRDY") (class "Default")
      (node (ref "U$101") (pin "14") (pinfunction "GPIO0[26]_14_14") (pintype "passive"))
      (node (ref "U403") (pin "12") (pinfunction "INT_12") (pintype "bidirectional"))
    )
    (net (code "47") (name "MPU_6500_DRDY") (class "Default")
      (node (ref "U$101") (pin "7") (pinfunction "7_GPIO2[2]_7") (pintype "passive"))
      (node (ref "U405") (pin "12") (pinfunction "INT_12") (pintype "bidirectional"))
    )
    (net (code "48") (name "Net-(C402-1)") (class "Default")
      (node (ref "C402") (pin "P$1") (pinfunction "1_P$1") (pintype "passive"))
      (node (ref "U406") (pin "7") (pinfunction "C1_XM_7") (pintype "bidirectional"))
    )
    (net (code "49") (name "Net-(C403-1)") (class "Default")
      (node (ref "C403") (pin "P$1") (pinfunction "1_P$1") (pintype "passive"))
      (node (ref "U406") (pin "8") (pinfunction "SETC_XM_8") (pintype "bidirectional"))
    )
    (net (code "50") (name "Net-(C403-2)") (class "Default")
      (node (ref "C403") (pin "P$2") (pinfunction "2_P$2") (pintype "passive"))
      (node (ref "U406") (pin "9") (pinfunction "SETP_XM_9") (pintype "bidirectional"))
    )
    (net (code "51") (name "Net-(C409-1)") (class "Default")
      (node (ref "C409") (pin "P$1") (pinfunction "1_P$1") (pintype "passive"))
      (node (ref "U403") (pin "10") (pinfunction "REGOUT_10") (pintype "bidirectional"))
    )
    (net (code "52") (name "Net-(C411-1)") (class "Default")
      (node (ref "C411") (pin "P$1") (pinfunction "1_P$1") (pintype "passive"))
      (node (ref "U405") (pin "10") (pinfunction "REGOUT_10") (pintype "bidirectional"))
    )
    (net (code "53") (name "Net-(C416-1)") (class "Default")
      (node (ref "C416") (pin "P$1") (pinfunction "1_P$1") (pintype "passive"))
      (node (ref "U403") (pin "20") (pinfunction "CPOUT_20") (pintype "bidirectional"))
    )
    (net (code "54") (name "Net-(C501-1)") (class "Default")
      (node (ref "C501") (pin "P$1") (pinfunction "1_P$1") (pintype "passive"))
      (node (ref "C502") (pin "P$1") (pinfunction "1_P$1") (pintype "passive"))
      (node (ref "L501") (pin "P$2") (pinfunction "P$2_P$2") (pintype "bidirectional"))
      (node (ref "U502") (pin "1") (pinfunction "VIN_1") (pintype "bidirectional"))
    )
    (net (code "55") (name "Net-(C503-1)") (class "Default")
      (node (ref "C503") (pin "P$1") (pinfunction "1_P$1") (pintype "passive"))
      (node (ref "U502") (pin "6") (pinfunction "CSET_6") (pintype "bidirectional"))
    )
    (net (code "56") (name "Net-(C603-1)") (class "Default")
      (node (ref "C603") (pin "P$1") (pinfunction "1_P$1") (pintype "passive"))
      (node (ref "R604") (pin "P$1") (pinfunction "1_P$1") (pintype "passive"))
      (node (ref "U$11") (pin "1") (pinfunction "1_1") (pintype "passive"))
      (node (ref "U602") (pin "1") (pinfunction "OUT_1") (pintype "output"))
    )
    (net (code "57") (name "Net-(C604-1)") (class "Default")
      (node (ref "C604") (pin "P$1") (pinfunction "1_P$1") (pintype "passive"))
      (node (ref "R606") (pin "P$1") (pinfunction "1_P$1") (pintype "passive"))
      (node (ref "R614") (pin "P$1") (pinfunction "1_P$1") (pintype "passive"))
      (node (ref "U602") (pin "6") (pinfunction "VCC_6") (pintype "bidirectional"))
    )
    (net (code "58") (name "Net-(D201-PadC)") (class "Default")
      (node (ref "D201") (pin "C") (pinfunction "C_C") (pintype "passive"))
      (node (ref "L201") (pin "P$2") (pinfunction "P$2_P$2") (pintype "bidirectional"))
      (node (ref "U$201") (pin "1") (pinfunction "1_1") (pintype "passive"))
    )
    (net (code "59") (name "Net-(D202-PadC)") (class "Default")
      (node (ref "D202") (pin "C") (pinfunction "C_C") (pintype "passive"))
      (node (ref "L202") (pin "P$2") (pinfunction "P$2_P$2") (pintype "bidirectional"))
      (node (ref "U$2") (pin "1") (pinfunction "1_1") (pintype "passive"))
    )
    (net (code "60") (name "Net-(D203-PadC)") (class "Default")
      (node (ref "D203") (pin "C") (pinfunction "C_C") (pintype "passive"))
      (node (ref "L203") (pin "P$2") (pinfunction "P$2_P$2") (pintype "bidirectional"))
      (node (ref "U$4") (pin "1") (pinfunction "1_1") (pintype "passive"))
    )
    (net (code "61") (name "Net-(D301-PadC)") (class "Default")
      (node (ref "D301") (pin "C") (pinfunction "C_C") (pintype "passive"))
      (node (ref "J305") (pin "1") (pinfunction "1_1") (pintype "passive"))
      (node (ref "J306") (pin "1") (pinfunction "1_1") (pintype "passive"))
      (node (ref "J310") (pin "1") (pinfunction "1_1") (pintype "passive"))
      (node (ref "J314") (pin "1") (pinfunction "1_1") (pintype "passive"))
      (node (ref "L301") (pin "P$2") (pinfunction "P$2_P$2") (pintype "bidirectional"))
    )
    (net (code "62") (name "Net-(D302-PadC)") (class "Default")
      (node (ref "D302") (pin "C") (pinfunction "C_C") (pintype "passive"))
      (node (ref "J309") (pin "1") (pinfunction "1_1") (pintype "passive"))
      (node (ref "L302") (pin "P$2") (pinfunction "P$2_P$2") (pintype "bidirectional"))
    )
    (net (code "63") (name "Net-(D303-PadC)") (class "Default")
      (node (ref "D303") (pin "C") (pinfunction "C_C") (pintype "passive"))
      (node (ref "J307") (pin "1") (pinfunction "1_1") (pintype "passive"))
      (node (ref "L303") (pin "P$2") (pinfunction "P$2_P$2") (pintype "bidirectional"))
    )
    (net (code "64") (name "Net-(D704-A)") (class "Default")
      (node (ref "D704") (pin "ANODE") (pinfunction "A_ANODE") (pintype "passive"))
      (node (ref "D705") (pin "ANODE") (pinfunction "A_ANODE") (pintype "passive"))
      (node (ref "R3") (pin "P$2") (pinfunction "2_P$2") (pintype "passive"))
      (node (ref "U704") (pin "11") (pinfunction "5V_11") (pintype "bidirectional"))
      (node (ref "U704") (pin "14") (pinfunction "5V_14") (pintype "bidirectional"))
      (node (ref "U704") (pin "17") (pinfunction "5V_17") (pintype "bidirectional"))
      (node (ref "U704") (pin "2") (pinfunction "5V_2") (pintype "bidirectional"))
      (node (ref "U704") (pin "20") (pinfunction "5V_20") (pintype "bidirectional"))
      (node (ref "U704") (pin "23") (pinfunction "5V_23") (pintype "bidirectional"))
      (node (ref "U704") (pin "26") (pinfunction "5V_26") (pintype "bidirectional"))
      (node (ref "U704") (pin "29") (pinfunction "5V_29") (pintype "bidirectional"))
      (node (ref "U704") (pin "32") (pinfunction "5V_32") (pintype "bidirectional"))
      (node (ref "U704") (pin "35") (pinfunction "5V_35") (pintype "bidirectional"))
      (node (ref "U704") (pin "38") (pinfunction "5V_38") (pintype "bidirectional"))
      (node (ref "U704") (pin "5") (pinfunction "5V_5") (pintype "bidirectional"))
      (node (ref "U704") (pin "8") (pinfunction "5V_8") (pintype "bidirectional"))
    )
    (net (code "65") (name "Net-(D704-C)") (class "Default")
      (node (ref "D704") (pin "CATHODE") (pinfunction "C_CATHODE") (pintype "passive"))
      (node (ref "D705") (pin "CATHODE") (pinfunction "C_CATHODE") (pintype "passive"))
      (node (ref "D706") (pin "C") (pinfunction "C_C") (pintype "passive"))
      (node (ref "L701") (pin "P$1") (pinfunction "P$1_P$1") (pintype "bidirectional"))
    )
    (net (code "66") (name "Net-(F701-Pad2)") (class "Default")
      (node (ref "F701") (pin "2") (pinfunction "2_2") (pintype "bidirectional"))
      (node (ref "U704") (pin "41") (pinfunction "5V_41") (pintype "bidirectional"))
    )
    (net (code "67") (name "Net-(L601-2)") (class "Default")
      (node (ref "L601") (pin "P$2") (pinfunction "2_P$2") (pintype "passive"))
      (node (ref "U602") (pin "5") (pinfunction "SW_5") (pintype "passive"))
    )
    (net (code "68") (name "Net-(Q501-PadC)") (class "Default")
      (node (ref "Q501") (pin "C") (pinfunction "C_C") (pintype "passive"))
      (node (ref "R505") (pin "2") (pinfunction "2_2") (pintype "passive"))
    )
    (net (code "69") (name "Net-(R1-2)") (class "Default")
      (node (ref "R1") (pin "P$2") (pinfunction "2_P$2") (pintype "passive"))
      (node (ref "R804") (pin "P$1") (pinfunction "1_P$1") (pintype "passive"))
    )
    (net (code "70") (name "Net-(R2-2)") (class "Default")
      (node (ref "R2") (pin "P$2") (pinfunction "2_P$2") (pintype "passive"))
      (node (ref "R805") (pin "P$1") (pinfunction "1_P$1") (pintype "passive"))
    )
    (net (code "71") (name "Net-(R4-2)") (class "Default")
      (node (ref "R4") (pin "P$2") (pinfunction "2_P$2") (pintype "passive"))
      (node (ref "R508") (pin "P$1") (pinfunction "1_P$1") (pintype "passive"))
    )
    (net (code "72") (name "Net-(R8-2)") (class "Default")
      (node (ref "R8") (pin "P$2") (pinfunction "2_P$2") (pintype "passive"))
      (node (ref "R9") (pin "P$1") (pinfunction "1_P$1") (pintype "passive"))
    )
    (net (code "73") (name "Net-(R103-1)") (class "Default")
      (node (ref "R103") (pin "P$1") (pinfunction "1_P$1") (pintype "passive"))
      (node (ref "U1") (pin "3") (pinfunction "A2_3") (pintype "bidirectional"))
    )
    (net (code "74") (name "Net-(R201-1)") (class "Default")
      (node (ref "R201") (pin "P$1") (pinfunction "1_P$1") (pintype "passive"))
      (node (ref "U201") (pin "20") (pinfunction "B1_20") (pintype "bidirectional"))
    )
    (net (code "75") (name "Net-(R202-1)") (class "Default")
      (node (ref "R202") (pin "P$1") (pinfunction "1_P$1") (pintype "passive"))
      (node (ref "U201") (pin "17") (pinfunction "B3_17") (pintype "bidirectional"))
    )
    (net (code "76") (name "Net-(R203-1)") (class "Default")
      (node (ref "R203") (pin "P$1") (pinfunction "1_P$1") (pintype "passive"))
      (node (ref "U201") (pin "15") (pinfunction "B5_15") (pintype "bidirectional"))
    )
    (net (code "77") (name "Net-(R204-1)") (class "Default")
      (node (ref "R204") (pin "P$1") (pinfunction "1_P$1") (pintype "passive"))
      (node (ref "U201") (pin "13") (pinfunction "B7_13") (pintype "bidirectional"))
    )
    (net (code "78") (name "Net-(R208-1)") (class "Default")
      (node (ref "R208") (pin "P$1") (pinfunction "1_P$1") (pintype "passive"))
      (node (ref "U201") (pin "18") (pinfunction "B2_18") (pintype "bidirectional"))
    )
    (net (code "79") (name "Net-(R209-1)") (class "Default")
      (node (ref "R209") (pin "P$1") (pinfunction "1_P$1") (pintype "passive"))
      (node (ref "U201") (pin "16") (pinfunction "B4_16") (pintype "bidirectional"))
    )
    (net (code "80") (name "Net-(R210-1)") (class "Default")
      (node (ref "R210") (pin "P$1") (pinfunction "1_P$1") (pintype "passive"))
      (node (ref "U201") (pin "14") (pinfunction "B6_14") (pintype "bidirectional"))
    )
    (net (code "81") (name "Net-(R211-1)") (class "Default")
      (node (ref "R211") (pin "P$1") (pinfunction "1_P$1") (pintype "passive"))
      (node (ref "U201") (pin "12") (pinfunction "B8_12") (pintype "bidirectional"))
    )
    (net (code "82") (name "Net-(R304-2)") (class "Default")
      (node (ref "J306") (pin "3") (pinfunction "3_3") (pintype "passive"))
      (node (ref "J310") (pin "3") (pinfunction "3_3") (pintype "passive"))
      (node (ref "J314") (pin "3") (pinfunction "3_3") (pintype "passive"))
      (node (ref "R304") (pin "P$2") (pinfunction "2_P$2") (pintype "passive"))
      (node (ref "U303") (pin "5") (pinfunction "SDA2_5") (pintype "bidirectional"))
    )
    (net (code "83") (name "Net-(R305-2)") (class "Default")
      (node (ref "J306") (pin "2") (pinfunction "2_2") (pintype "passive"))
      (node (ref "J310") (pin "2") (pinfunction "2_2") (pintype "passive"))
      (node (ref "J314") (pin "2") (pinfunction "2_2") (pintype "passive"))
      (node (ref "R305") (pin "P$2") (pinfunction "2_P$2") (pintype "passive"))
      (node (ref "U303") (pin "6") (pinfunction "SCL2_6") (pintype "bidirectional"))
    )
    (net (code "84") (name "Net-(R306-2)") (class "Default")
      (node (ref "R306") (pin "P$2") (pinfunction "2_P$2") (pintype "passive"))
      (node (ref "R7") (pin "P$1") (pinfunction "1_P$1") (pintype "passive"))
    )
    (net (code "85") (name "Net-(R307-2)") (class "Default")
      (node (ref "R307") (pin "P$2") (pinfunction "2_P$2") (pintype "passive"))
      (node (ref "R5") (pin "P$1") (pinfunction "1_P$1") (pintype "passive"))
    )
    (net (code "86") (name "Net-(R308-2)") (class "Default")
      (node (ref "R308") (pin "P$2") (pinfunction "2_P$2") (pintype "passive"))
      (node (ref "R6") (pin "P$1") (pinfunction "1_P$1") (pintype "passive"))
    )
    (net (code "87") (name "Net-(R310-2)") (class "Default")
      (node (ref "J309") (pin "2") (pinfunction "2_2") (pintype "passive"))
      (node (ref "R310") (pin "P$2") (pinfunction "2_P$2") (pintype "passive"))
      (node (ref "R5") (pin "P$2") (pinfunction "2_P$2") (pintype "passive"))
    )
    (net (code "88") (name "Net-(R311-2)") (class "Default")
      (node (ref "J309") (pin "4") (pinfunction "4_4") (pintype "passive"))
      (node (ref "R311") (pin "P$2") (pinfunction "2_P$2") (pintype "passive"))
      (node (ref "R6") (pin "P$2") (pinfunction "2_P$2") (pintype "passive"))
    )
    (net (code "89") (name "Net-(R312-1)") (class "Default")
      (node (ref "R312") (pin "P$1") (pinfunction "1_P$1") (pintype "passive"))
      (node (ref "U302") (pin "18") (pinfunction "B2_18") (pintype "bidirectional"))
    )
    (net (code "90") (name "Net-(R312-2)") (class "Default")
      (node (ref "J308") (pin "3") (pinfunction "3_3") (pintype "passive"))
      (node (ref "R312") (pin "P$2") (pinfunction "2_P$2") (pintype "passive"))
    )
    (net (code "91") (name "Net-(R313-1)") (class "Default")
      (node (ref "R313") (pin "P$1") (pinfunction "1_P$1") (pintype "passive"))
      (node (ref "U302") (pin "20") (pinfunction "B1_20") (pintype "bidirectional"))
    )
    (net (code "92") (name "Net-(R313-2)") (class "Default")
      (node (ref "J308") (pin "2") (pinfunction "2_2") (pintype "passive"))
      (node (ref "R313") (pin "P$2") (pinfunction "2_P$2") (pintype "passive"))
    )
    (net (code "93") (name "Net-(R315-1)") (class "Default")
      (node (ref "R315") (pin "P$1") (pinfunction "1_P$1") (pintype "passive"))
      (node (ref "U301") (pin "8") (pinfunction "RS_8") (pintype "input"))
    )
    (net (code "94") (name "Net-(R501-1)") (class "Default")
      (node (ref "R501") (pin "P$1") (pinfunction "1_P$1") (pintype "passive"))
      (node (ref "U501") (pin "7") (pinfunction "ILIM_7") (pintype "bidirectional"))
    )
    (net (code "95") (name "Net-(R503-1)") (class "Default")
      (node (ref "Q501") (pin "B") (pinfunction "B_B") (pintype "passive"))
      (node (ref "R503") (pin "P$1") (pinfunction "1_P$1") (pintype "passive"))
    )
    (net (code "96") (name "Net-(R504-1)") (class "Default")
      (node (ref "R504") (pin "P$1") (pinfunction "1_P$1") (pintype "passive"))
      (node (ref "U503") (pin "7") (pinfunction "ILIM_7") (pintype "bidirectional"))
    )
    (net (code "97") (name "Net-(R602-1)") (class "Default")
      (node (ref "R602") (pin "P$1") (pinfunction "1_P$1") (pintype "passive"))
      (node (ref "U602") (pin "7") (pinfunction "+IN_7") (pintype "input"))
    )
    (net (code "98") (name "Net-(R603-1)") (class "Default")
      (node (ref "R603") (pin "P$1") (pinfunction "1_P$1") (pintype "passive"))
      (node (ref "R604") (pin "P$2") (pinfunction "2_P$2") (pintype "passive"))
      (node (ref "U602") (pin "8") (pinfunction "-IN_8") (pintype "input"))
    )
    (net (code "99") (name "Net-(R606-2)") (class "Default")
      (node (ref "JP600") (pin "2") (pinfunction "2_2") (pintype "passive"))
      (node (ref "R606") (pin "P$2") (pinfunction "2_P$2") (pintype "passive"))
      (node (ref "R607") (pin "P$1") (pinfunction "1_P$1") (pintype "passive"))
      (node (ref "U602") (pin "2") (pinfunction "FB_2") (pintype "bidirectional"))
    )
    (net (code "100") (name "Net-(R608-2)") (class "Default")
      (node (ref "LED601") (pin "C") (pinfunction "C_C") (pintype "passive"))
      (node (ref "R608") (pin "P$2") (pinfunction "2_P$2") (pintype "passive"))
    )
    (net (code "101") (name "Net-(R609-1)") (class "Default")
      (node (ref "R609") (pin "P$1") (pinfunction "1_P$1") (pintype "passive"))
      (node (ref "R610") (pin "P$2") (pinfunction "2_P$2") (pintype "passive"))
    )
    (net (code "102") (name "Net-(R609-2)") (class "Default")
      (node (ref "LED602") (pin "C") (pinfunction "C_C") (pintype "passive"))
      (node (ref "R609") (pin "P$2") (pinfunction "2_P$2") (pintype "passive"))
    )
    (net (code "103") (name "Net-(R611-1)") (class "Default")
      (node (ref "R611") (pin "P$1") (pinfunction "1_P$1") (pintype "passive"))
      (node (ref "U$12") (pin "2") (pinfunction "2_2") (pintype "passive"))
    )
    (net (code "104") (name "Net-(R612-2)") (class "Default")
      (node (ref "LED603") (pin "C") (pinfunction "C_C") (pintype "passive"))
      (node (ref "R612") (pin "P$2") (pinfunction "2_P$2") (pintype "passive"))
    )
    (net (code "105") (name "Net-(R614-2)") (class "Default")
      (node (ref "JP600") (pin "1") (pinfunction "1_1") (pintype "passive"))
      (node (ref "R614") (pin "P$2") (pinfunction "2_P$2") (pintype "passive"))
    )
    (net (code "106") (name "Net-(R701-2)") (class "Default")
      (node (ref "R701") (pin "P$2") (pinfunction "2_P$2") (pintype "passive"))
      (node (ref "U704") (pin "10") (pinfunction "CH4_10") (pintype "bidirectional"))
    )
    (net (code "107") (name "Net-(R702-2)") (class "Default")
      (node (ref "R702") (pin "P$2") (pinfunction "2_P$2") (pintype "passive"))
      (node (ref "U704") (pin "13") (pinfunction "CH5_13") (pintype "bidirectional"))
    )
    (net (code "108") (name "Net-(R703-2)") (class "Default")
      (node (ref "R703") (pin "P$2") (pinfunction "2_P$2") (pintype "passive"))
      (node (ref "U704") (pin "16") (pinfunction "CH6_16") (pintype "bidirectional"))
    )
    (net (code "109") (name "Net-(R704-2)") (class "Default")
      (node (ref "R704") (pin "P$2") (pinfunction "2_P$2") (pintype "passive"))
      (node (ref "U704") (pin "19") (pinfunction "CH7_19") (pintype "bidirectional"))
    )
    (net (code "110") (name "Net-(R705-2)") (class "Default")
      (node (ref "R705") (pin "P$2") (pinfunction "2_P$2") (pintype "passive"))
      (node (ref "U704") (pin "22") (pinfunction "CH8_22") (pintype "bidirectional"))
    )
    (net (code "111") (name "Net-(R706-2)") (class "Default")
      (node (ref "R706") (pin "P$2") (pinfunction "2_P$2") (pintype "passive"))
      (node (ref "U704") (pin "25") (pinfunction "CH9_25") (pintype "bidirectional"))
    )
    (net (code "112") (name "Net-(R707-2)") (class "Default")
      (node (ref "R707") (pin "P$2") (pinfunction "2_P$2") (pintype "passive"))
      (node (ref "U704") (pin "28") (pinfunction "CH10_28") (pintype "bidirectional"))
    )
    (net (code "113") (name "Net-(R708-2)") (class "Default")
      (node (ref "R708") (pin "P$2") (pinfunction "2_P$2") (pintype "passive"))
      (node (ref "U704") (pin "31") (pinfunction "CH11_31") (pintype "bidirectional"))
    )
    (net (code "114") (name "Net-(R709-2)") (class "Default")
      (node (ref "R709") (pin "P$2") (pinfunction "2_P$2") (pintype "passive"))
      (node (ref "U704") (pin "34") (pinfunction "CH12_34") (pintype "bidirectional"))
    )
    (net (code "115") (name "Net-(R710-2)") (class "Default")
      (node (ref "R710") (pin "P$2") (pinfunction "2_P$2") (pintype "passive"))
      (node (ref "U704") (pin "37") (pinfunction "PPM/S.BUS_OUT_37") (pintype "bidirectional"))
    )
    (net (code "116") (name "Net-(R711-2)") (class "Default")
      (node (ref "R711") (pin "P$2") (pinfunction "2_P$2") (pintype "passive"))
      (node (ref "U704") (pin "40") (pinfunction "PPM/S.BUS_IN_40") (pintype "bidirectional"))
    )
    (net (code "117") (name "Net-(R712-2)") (class "Default")
      (node (ref "R712") (pin "P$2") (pinfunction "2_P$2") (pintype "passive"))
      (node (ref "U704") (pin "7") (pinfunction "CH3_7") (pintype "bidirectional"))
    )
    (net (code "118") (name "Net-(R713-2)") (class "Default")
      (node (ref "R713") (pin "P$2") (pinfunction "2_P$2") (pintype "passive"))
      (node (ref "U704") (pin "4") (pinfunction "CH2_4") (pintype "bidirectional"))
    )
    (net (code "119") (name "Net-(R714-2)") (class "Default")
      (node (ref "R714") (pin "P$2") (pinfunction "2_P$2") (pintype "passive"))
      (node (ref "U704") (pin "1") (pinfunction "CH1_1") (pintype "bidirectional"))
    )
    (net (code "120") (name "Net-(R801-1)") (class "Default")
      (node (ref "J801") (pin "4") (pinfunction "4_4") (pintype "passive"))
      (node (ref "L802") (pin "P$1") (pinfunction "P$1_P$1") (pintype "bidirectional"))
      (node (ref "R801") (pin "P$1") (pinfunction "1_P$1") (pintype "passive"))
    )
    (net (code "121") (name "Net-(R802-1)") (class "Default")
      (node (ref "J801") (pin "3") (pinfunction "3_3") (pintype "passive"))
      (node (ref "L801") (pin "P$1") (pinfunction "P$1_P$1") (pintype "bidirectional"))
      (node (ref "R802") (pin "P$1") (pinfunction "1_P$1") (pintype "passive"))
    )
    (net (code "122") (name "Net-(R804-2)") (class "Default")
      (node (ref "L801") (pin "P$2") (pinfunction "P$2_P$2") (pintype "bidirectional"))
      (node (ref "R804") (pin "P$2") (pinfunction "2_P$2") (pintype "passive"))
    )
    (net (code "123") (name "Net-(R805-2)") (class "Default")
      (node (ref "L802") (pin "P$2") (pinfunction "P$2_P$2") (pintype "bidirectional"))
      (node (ref "R805") (pin "P$2") (pinfunction "2_P$2") (pintype "passive"))
    )
    (net (code "124") (name "Net-(U302-VCCB)") (class "Default")
      (node (ref "J308") (pin "1") (pinfunction "1_1") (pintype "passive"))
      (node (ref "JP1") (pin "1") (pinfunction "1_1") (pintype "passive"))
      (node (ref "U302") (pin "19") (pinfunction "VCCB_19") (pintype "input"))
    )
    (net (code "125") (name "OUTPUT_EN") (class "Default")
      (node (ref "R806") (pin "P$2") (pinfunction "2_P$2") (pintype "passive"))
      (node (ref "R9") (pin "P$2") (pinfunction "2_P$2") (pintype "passive"))
      (node (ref "U201") (pin "10") (pinfunction "OE_10") (pintype "input"))
      (node (ref "U502") (pin "3") (pinfunction "POR2_3") (pintype "bidirectional"))
      (node (ref "U701") (pin "10") (pinfunction "OE_10") (pintype "input"))
      (node (ref "U702") (pin "10") (pinfunction "OE_10") (pintype "input"))
      (node (ref "U802") (pin "5") (pinfunction "EN1_5") (pintype "bidirectional"))
    )
    (net (code "126") (name "PPM{slash}S.BUS_INPUT") (class "Default")
      (node (ref "J701") (pin "P$3") (pinfunction "P$3_P$3") (pintype "bidirectional"))
      (node (ref "R711") (pin "P$1") (pinfunction "1_P$1") (pintype "passive"))
      (node (ref "U$101") (pin "15") (pinfunction "15_PRU0_R31[15]_15") (pintype "passive"))
    )
    (net (code "127") (name "PPM{slash}S.BUS_OUT") (class "Default")
      (node (ref "R710") (pin "P$1") (pinfunction "1_P$1") (pintype "passive"))
      (node (ref "U$101") (pin "11") (pinfunction "11_PRU0_R30[15]_11") (pintype "passive"))
    )
    (net (code "128") (name "PRESSURE_SENS") (class "Default")
      (node (ref "C301") (pin "P$1") (pinfunction "1_P$1") (pintype "passive"))
      (node (ref "R303") (pin "P$2") (pinfunction "2_P$2") (pintype "passive"))
      (node (ref "R306") (pin "P$1") (pinfunction "1_P$1") (pintype "passive"))
      (node (ref "U$101") (pin "86") (pinfunction "AIN1_40_86") (pintype "passive"))
    )
    (net (code "129") (name "PRESSURE_SENS_IN") (class "Default")
      (node (ref "ADC_PR") (pin "P$1") (pinfunction "P$1_P$1") (pintype "passive"))
      (node (ref "J305") (pin "2") (pinfunction "2_2") (pintype "passive"))
      (node (ref "R7") (pin "P$2") (pinfunction "2_P$2") (pintype "passive"))
    )
    (net (code "130") (name "SAFETY") (class "Default")
      (node (ref "R613") (pin "P$1") (pinfunction "1_P$1") (pintype "passive"))
      (node (ref "U$101") (pin "87") (pinfunction "41_PRU0_R30/31[6]_87") (pintype "input"))
      (node (ref "U$12") (pin "3") (pinfunction "3_3") (pintype "passive"))
    )
    (net (code "131") (name "SERVO_RAIL_IN_~{EN}") (class "Default")
      (node (ref "U$101") (pin "16") (pinfunction "PRU0_R31[14]_16_16") (pintype "passive"))
    )
    (net (code "132") (name "SPARE") (class "Default")
      (node (ref "U$101") (pin "17") (pinfunction "17_GPIO0[27]_17") (pintype "passive"))
    )
    (net (code "133") (name "SPI_0_MISO") (class "Default")
      (node (ref "U$101") (pin "64") (pinfunction "SPI_0_MISO_18_64") (pintype "passive"))
      (node (ref "U406") (pin "22") (pinfunction "SDO_G_22") (pintype "bidirectional"))
      (node (ref "U406") (pin "23") (pinfunction "SDO_XM_23") (pintype "bidirectional"))
    )
    (net (code "134") (name "SPI_0_MOSI") (class "Default")
      (node (ref "U$101") (pin "67") (pinfunction "21_SPI_0_MOSI_67") (pintype "passive"))
      (node (ref "U406") (pin "24") (pinfunction "SDA_24") (pintype "bidirectional"))
    )
    (net (code "135") (name "SPI_0_SCK") (class "Default")
      (node (ref "U$101") (pin "68") (pinfunction "SPI_0_SCLK_22_68") (pintype "passive"))
      (node (ref "U406") (pin "21") (pinfunction "SPC_21") (pintype "bidirectional"))
    )
    (net (code "136") (name "SPI_1_MISO") (class "Default")
      (node (ref "U$101") (pin "76") (pinfunction "SPI_1_MISO_30_76") (pintype "passive"))
      (node (ref "U102") (pin "2") (pinfunction "Q_2") (pintype "bidirectional"))
      (node (ref "U401") (pin "6") (pinfunction "SDO_6") (pintype "bidirectional"))
      (node (ref "U403") (pin "9") (pinfunction "AD0/SDO_9") (pintype "bidirectional"))
      (node (ref "U405") (pin "9") (pinfunction "AD0/SDO_9") (pintype "bidirectional"))
    )
    (net (code "137") (name "SPI_1_MOSI") (class "Default")
      (node (ref "U$101") (pin "75") (pinfunction "29_SPI_1_MOSI_75") (pintype "passive"))
      (node (ref "U102") (pin "5") (pinfunction "D_5") (pintype "bidirectional"))
      (node (ref "U401") (pin "7") (pinfunction "SDI/SDA_7") (pintype "bidirectional"))
      (node (ref "U403") (pin "24") (pinfunction "SDA/SDI_24") (pintype "bidirectional"))
      (node (ref "U405") (pin "24") (pinfunction "SDA/SDI_24") (pintype "bidirectional"))
    )
    (net (code "138") (name "SPI_1_SCK") (class "Default")
      (node (ref "U$101") (pin "77") (pinfunction "31_SPI_1_SCLK_77") (pintype "passive"))
      (node (ref "U102") (pin "6") (pinfunction "C_6") (pintype "bidirectional"))
      (node (ref "U401") (pin "8") (pinfunction "SCLK_8") (pintype "bidirectional"))
      (node (ref "U403") (pin "23") (pinfunction "SCL/SCLK_23") (pintype "bidirectional"))
      (node (ref "U405") (pin "23") (pinfunction "SCL/SCLK_23") (pintype "bidirectional"))
    )
    (net (code "139") (name "SPI_1_~{BARO_CS}") (class "Default")
      (node (ref "U$101") (pin "88") (pinfunction "SPI_1_CS1_42_88") (pintype "passive"))
      (node (ref "U401") (pin "5") (pinfunction "CSB2_5") (pintype "bidirectional"))
    )
    (net (code "140") (name "SPI_1_~{MPU_CS2}") (class "Default")
      (node (ref "U$101") (pin "69") (pinfunction "23_GPIO1[17]_69") (pintype "passive"))
      (node (ref "U405") (pin "22") (pinfunction "~{CS}_22") (pintype "bidirectional"))
    )
    (net (code "141") (name "SPI_1_~{MPU_CS}") (class "Default")
      (node (ref "U$101") (pin "74") (pinfunction "SPI_1_CS0_28_74") (pintype "passive"))
      (node (ref "U403") (pin "8") (pinfunction "/CS_8") (pintype "bidirectional"))
    )
    (net (code "142") (name "SYS_5V") (class "Default")
      (node (ref "F701") (pin "1") (pinfunction "1_1") (pintype "bidirectional"))
      (node (ref "L501") (pin "P$1") (pinfunction "P$1_P$1") (pintype "bidirectional"))
      (node (ref "R508") (pin "P$2") (pinfunction "2_P$2") (pintype "passive"))
      (node (ref "U$101") (pin "53") (pinfunction "7_SYS_5V_53") (pintype "power_in"))
      (node (ref "U$101") (pin "54") (pinfunction "SYS_5V_8_54") (pintype "passive"))
      (node (ref "U501") (pin "1") (pinfunction "IN_1") (pintype "bidirectional"))
      (node (ref "U503") (pin "1") (pinfunction "IN_1") (pintype "bidirectional"))
      (node (ref "U802") (pin "1") (pinfunction "VIN_1") (pintype "bidirectional"))
      (node (ref "VDD_5V_IN") (pin "P$1") (pinfunction "P$1_P$1") (pintype "passive"))
    )
    (net (code "143") (name "TTYO0_RX") (class "Default")
      (node (ref "R212") (pin "P$2") (pinfunction "2_P$2") (pintype "passive"))
      (node (ref "U$4") (pin "3") (pinfunction "3_3") (pintype "passive"))
    )
    (net (code "144") (name "TTYO0_TX") (class "Default")
      (node (ref "R205") (pin "P$2") (pinfunction "2_P$2") (pintype "passive"))
      (node (ref "U$4") (pin "2") (pinfunction "2_2") (pintype "passive"))
    )
    (net (code "145") (name "TTYO4_CTS") (class "Default")
      (node (ref "R211") (pin "P$2") (pinfunction "2_P$2") (pintype "passive"))
      (node (ref "U$201") (pin "4") (pinfunction "4_4") (pintype "passive"))
    )
    (net (code "146") (name "TTYO4_RTS") (class "Default")
      (node (ref "R204") (pin "P$2") (pinfunction "2_P$2") (pintype "passive"))
      (node (ref "U$201") (pin "5") (pinfunction "5_5") (pintype "passive"))
    )
    (net (code "147") (name "TTYO4_RX") (class "Default")
      (node (ref "R203") (pin "P$2") (pinfunction "2_P$2") (pintype "passive"))
      (node (ref "S1RX") (pin "P$1") (pinfunction "P$1_P$1") (pintype "passive"))
      (node (ref "U$201") (pin "3") (pinfunction "3_3") (pintype "passive"))
    )
    (net (code "148") (name "TTYO4_TX") (class "Default")
      (node (ref "R210") (pin "P$2") (pinfunction "2_P$2") (pintype "passive"))
      (node (ref "S1TX") (pin "P$1") (pinfunction "P$1_P$1") (pintype "passive"))
      (node (ref "U$201") (pin "2") (pinfunction "2_2") (pintype "passive"))
    )
    (net (code "149") (name "TTYO5_CTS") (class "Default")
      (node (ref "R208") (pin "P$2") (pinfunction "2_P$2") (pintype "passive"))
      (node (ref "U$2") (pin "4") (pinfunction "4_4") (pintype "passive"))
    )
    (net (code "150") (name "TTYO5_RTS") (class "Default")
      (node (ref "R201") (pin "P$2") (pinfunction "2_P$2") (pintype "passive"))
      (node (ref "U$2") (pin "5") (pinfunction "5_5") (pintype "passive"))
    )
    (net (code "151") (name "TTYO5_RX") (class "Default")
      (node (ref "R202") (pin "P$2") (pinfunction "2_P$2") (pintype "passive"))
      (node (ref "S2RX") (pin "P$1") (pinfunction "P$1_P$1") (pintype "passive"))
      (node (ref "U$2") (pin "3") (pinfunction "3_3") (pintype "passive"))
    )
    (net (code "152") (name "TTYO5_TX") (class "Default")
      (node (ref "R209") (pin "P$2") (pinfunction "2_P$2") (pintype "passive"))
      (node (ref "S2TX") (pin "P$1") (pinfunction "P$1_P$1") (pintype "passive"))
      (node (ref "U$2") (pin "2") (pinfunction "2_2") (pintype "passive"))
    )
    (net (code "153") (name "UART0_RX") (class "Default")
      (node (ref "R212") (pin "P$1") (pinfunction "1_P$1") (pintype "passive"))
      (node (ref "U$101") (pin "97") (pinfunction "UART0_RXD_97") (pintype "bidirectional"))
    )
    (net (code "154") (name "UART0_TX") (class "Default")
      (node (ref "R205") (pin "P$1") (pinfunction "1_P$1") (pintype "passive"))
      (node (ref "U$101") (pin "96") (pinfunction "UART0_TXD_96") (pintype "bidirectional"))
    )
    (net (code "155") (name "UBLED-SCL") (class "Default")
      (node (ref "U$101") (pin "60") (pinfunction "GPIO1[18]_14_60") (pintype "passive"))
      (node (ref "U302") (pin "3") (pinfunction "A2_3") (pintype "bidirectional"))
    )
    (net (code "156") (name "UBLED-SDA") (class "Default")
      (node (ref "U$101") (pin "62") (pinfunction "GPIO1[19]_16_62") (pintype "passive"))
      (node (ref "U302") (pin "1") (pinfunction "A1_1") (pintype "bidirectional"))
    )
    (net (code "157") (name "USART4_CTS") (class "Default")
      (node (ref "U$101") (pin "35") (pinfunction "35_UART4_CTSN_35") (pintype "passive"))
      (node (ref "U201") (pin "9") (pinfunction "A8_9") (pintype "bidirectional"))
    )
    (net (code "158") (name "USART4_RTS") (class "Default")
      (node (ref "U$101") (pin "33") (pinfunction "33_UART4_RTSN_33") (pintype "passive"))
      (node (ref "U201") (pin "8") (pinfunction "A7_8") (pintype "bidirectional"))
    )
    (net (code "159") (name "USART4_RX") (class "Default")
      (node (ref "U$101") (pin "57") (pinfunction "11_UART4_RXD_57") (pintype "passive"))
      (node (ref "U201") (pin "6") (pinfunction "A5_6") (pintype "bidirectional"))
    )
    (net (code "160") (name "USART4_TX") (class "Default")
      (node (ref "U$101") (pin "59") (pinfunction "13_UART4_TXD_59") (pintype "passive"))
      (node (ref "U201") (pin "7") (pinfunction "A6_7") (pintype "bidirectional"))
    )
    (net (code "161") (name "USART5_CTS") (class "Default")
      (node (ref "U$101") (pin "31") (pinfunction "31_UART5_CTSN_31") (pintype "passive"))
      (node (ref "U201") (pin "3") (pinfunction "A2_3") (pintype "bidirectional"))
    )
    (net (code "162") (name "USART5_RTS") (class "Default")
      (node (ref "U$101") (pin "32") (pinfunction "UART5_RTSN_32_32") (pintype "passive"))
      (node (ref "U201") (pin "1") (pinfunction "A1_1") (pintype "bidirectional"))
    )
    (net (code "163") (name "USART5_RX") (class "Default")
      (node (ref "U$101") (pin "38") (pinfunction "UART5_RXD_38_38") (pintype "passive"))
      (node (ref "U201") (pin "4") (pinfunction "A3_4") (pintype "bidirectional"))
    )
    (net (code "164") (name "USART5_TX") (class "Default")
      (node (ref "U$101") (pin "37") (pinfunction "37_UART5_TXD_37") (pintype "passive"))
      (node (ref "U201") (pin "5") (pinfunction "A4_5") (pintype "bidirectional"))
    )
    (net (code "165") (name "VDD_3V3_4") (class "Default")
      (node (ref "U$101") (pin "50") (pinfunction "VDD_3V3_4_50") (pintype "power_in"))
    )
    (net (code "166") (name "VDD_3V3_SENSORS") (class "Default")
      (node (ref "C101") (pin "P$1") (pinfunction "1_P$1") (pintype "passive"))
      (node (ref "C305") (pin "P$1") (pinfunction "1_P$1") (pintype "passive"))
      (node (ref "C401") (pin "P$1") (pinfunction "1_P$1") (pintype "passive"))
      (node (ref "C405") (pin "P$2") (pinfunction "2_P$2") (pintype "passive"))
      (node (ref "C406") (pin "P$2") (pinfunction "2_P$2") (pintype "passive"))
      (node (ref "C407") (pin "P$1") (pinfunction "1_P$1") (pintype "passive"))
      (node (ref "C408") (pin "P$1") (pinfunction "1_P$1") (pintype "passive"))
      (node (ref "C410") (pin "P$1") (pinfunction "1_P$1") (pintype "passive"))
      (node (ref "C412") (pin "P$1") (pinfunction "1_P$1") (pintype "passive"))
      (node (ref "C413") (pin "P$1") (pinfunction "1_P$1") (pintype "passive"))
      (node (ref "C414") (pin "P$1") (pinfunction "1_P$1") (pintype "passive"))
      (node (ref "C415") (pin "P$1") (pinfunction "1_P$1") (pintype "passive"))
      (node (ref "C508") (pin "P$1") (pinfunction "1_P$1") (pintype "passive"))
      (node (ref "C509") (pin "P$1") (pinfunction "1_P$1") (pintype "passive"))
      (node (ref "Q501") (pin "E") (pinfunction "E_E") (pintype "passive"))
      (node (ref "R103") (pin "P$2") (pinfunction "2_P$2") (pintype "passive"))
      (node (ref "U1") (pin "8") (pinfunction "VCC_8") (pintype "power_in"))
      (node (ref "U102") (pin "3") (pinfunction "~{W}_3") (pintype "bidirectional"))
      (node (ref "U102") (pin "7") (pinfunction "~{HOLD}_7") (pintype "bidirectional"))
      (node (ref "U102") (pin "8") (pinfunction "VDD_8") (pintype "bidirectional"))
      (node (ref "U2") (pin "8") (pinfunction "VCC_8") (pintype "power_in"))
      (node (ref "U401") (pin "1") (pinfunction "VDD_1") (pintype "bidirectional"))
      (node (ref "U403") (pin "13") (pinfunction "VDD_13") (pintype "bidirectional"))
      (node (ref "U405") (pin "1") (pinfunction "NC_1") (pintype "bidirectional"))
      (node (ref "U405") (pin "13") (pinfunction "VDD_13") (pintype "bidirectional"))
      (node (ref "U405") (pin "8") (pinfunction "VDDIO_8") (pintype "bidirectional"))
      (node (ref "U406") (pin "15") (pinfunction "VDD_15") (pintype "bidirectional"))
      (node (ref "U406") (pin "16") (pinfunction "VDD_16") (pintype "bidirectional"))
      (node (ref "U406") (pin "17") (pinfunction "VDD_17") (pintype "bidirectional"))
      (node (ref "U406") (pin "18") (pinfunction "VDD_IO_18") (pintype "bidirectional"))
      (node (ref "U502") (pin "8") (pinfunction "VOUT1_8") (pintype "bidirectional"))
      (node (ref "VDDA_3V901") (pin "P$1") (pinfunction "P$1_P$1") (pintype "passive"))
    )
    (net (code "167") (name "VDD_3V3_SPEKTRUM") (class "Default")
      (node (ref "C805") (pin "P$1") (pinfunction "1_P$1") (pintype "passive"))
      (node (ref "D703") (pin "C") (pinfunction "C_C") (pintype "passive"))
      (node (ref "J701") (pin "P$1") (pinfunction "P$1_P$1") (pintype "bidirectional"))
      (node (ref "U802") (pin "8") (pinfunction "VOUT1_8") (pintype "bidirectional"))
    )
    (net (code "168") (name "VDD_5V") (class "Default")
      (node (ref "C801") (pin "P$1") (pinfunction "1_P$1") (pintype "passive"))
      (node (ref "J801") (pin "1") (pinfunction "1_1") (pintype "passive"))
      (node (ref "J801") (pin "2") (pinfunction "2_2") (pintype "passive"))
      (node (ref "U$101") (pin "51") (pinfunction "5_VDD_5V_51") (pintype "power_in"))
      (node (ref "U$101") (pin "52") (pinfunction "VDD_5V_6_52") (pintype "power_in"))
      (node (ref "VDD_5V_BRICK") (pin "P$1") (pinfunction "P$1_P$1") (pintype "passive"))
    )
    (net (code "169") (name "VDD_5V_HIPOWER") (class "Default")
      (node (ref "C504") (pin "P$1") (pinfunction "1_P$1") (pintype "passive"))
      (node (ref "L201") (pin "P$1") (pinfunction "P$1_P$1") (pintype "bidirectional"))
      (node (ref "U501") (pin "8") (pinfunction "OUT_8") (pintype "bidirectional"))
    )
    (net (code "170") (name "VDD_5V_PERIPH") (class "Default")
      (node (ref "C510") (pin "P$1") (pinfunction "1_P$1") (pintype "passive"))
      (node (ref "C602") (pin "P$1") (pinfunction "1_P$1") (pintype "passive"))
      (node (ref "L202") (pin "P$1") (pinfunction "P$1_P$1") (pintype "bidirectional"))
      (node (ref "L203") (pin "P$1") (pinfunction "P$1_P$1") (pintype "bidirectional"))
      (node (ref "L301") (pin "P$1") (pinfunction "P$1_P$1") (pintype "bidirectional"))
      (node (ref "L302") (pin "P$1") (pinfunction "P$1_P$1") (pintype "bidirectional"))
      (node (ref "L303") (pin "P$1") (pinfunction "P$1_P$1") (pintype "bidirectional"))
      (node (ref "L601") (pin "P$1") (pinfunction "1_P$1") (pintype "passive"))
      (node (ref "LED601") (pin "A") (pinfunction "A_A") (pintype "passive"))
      (node (ref "LED602") (pin "A") (pinfunction "A_A") (pintype "passive"))
      (node (ref "LED603") (pin "A") (pinfunction "A_A") (pintype "passive"))
      (node (ref "U503") (pin "8") (pinfunction "OUT_8") (pintype "bidirectional"))
      (node (ref "U602") (pin "3") (pinfunction "VIN_3") (pintype "power_in"))
    )
    (net (code "171") (name "VDD_5V_SENS") (class "Default")
      (node (ref "R4") (pin "P$1") (pinfunction "1_P$1") (pintype "passive"))
      (node (ref "R509") (pin "P$1") (pinfunction "1_P$1") (pintype "passive"))
      (node (ref "U$101") (pin "79") (pinfunction "33_AIN4_79") (pintype "passive"))
    )
    (net (code "172") (name "VDD_SERVO_IN") (class "Default")
      (node (ref "L701") (pin "P$2") (pinfunction "P$2_P$2") (pintype "bidirectional"))
    )
    (net (code "173") (name "VDD_SERVO_SENS") (class "Default")
      (node (ref "R3") (pin "P$1") (pinfunction "1_P$1") (pintype "passive"))
      (node (ref "R716") (pin "P$2") (pinfunction "2_P$2") (pintype "passive"))
      (node (ref "U$101") (pin "85") (pinfunction "39_AIN0_85") (pintype "power_in"))
    )
    (net (code "174") (name "unconnected-(U$4-Pad4)") (class "Default")
      (node (ref "U$4") (pin "4") (pinfunction "4_4") (pintype "passive"))
    )
    (net (code "175") (name "unconnected-(U$4-Pad5)") (class "Default")
      (node (ref "U$4") (pin "5") (pinfunction "5_5") (pintype "passive"))
    )
    (net (code "176") (name "unconnected-(U$101-3_MMC1-Pad3)") (class "Default")
      (node (ref "U$101") (pin "3") (pinfunction "3_MMC1_3") (pintype "passive"))
    )
    (net (code "177") (name "unconnected-(U$101-5_MMC1-Pad5)") (class "Default")
      (node (ref "U$101") (pin "5") (pinfunction "5_MMC1_5") (pintype "passive"))
    )
    (net (code "178") (name "unconnected-(U$101-9_PWR_BUT-Pad55)") (class "Default")
      (node (ref "U$101") (pin "55") (pinfunction "9_PWR_BUT_55") (pintype "passive"))
    )
    (net (code "179") (name "unconnected-(U$101-21_MMC1-Pad21)") (class "Default")
      (node (ref "U$101") (pin "21") (pinfunction "21_MMC1_21") (pintype "passive"))
    )
    (net (code "180") (name "unconnected-(U$101-23_MMC1-Pad23)") (class "Default")
      (node (ref "U$101") (pin "23") (pinfunction "23_MMC1_23") (pintype "passive"))
    )
    (net (code "181") (name "unconnected-(U$101-25_MMC1-Pad25)") (class "Default")
      (node (ref "U$101") (pin "25") (pinfunction "25_MMC1_25") (pintype "passive"))
    )
    (net (code "182") (name "unconnected-(U$101-MMC1_3-Pad6)") (class "Default")
      (node (ref "U$101") (pin "6") (pinfunction "MMC1_3_6") (pintype "passive"))
    )
    (net (code "183") (name "unconnected-(U$101-MMC1_4-Pad4)") (class "Default")
      (node (ref "U$101") (pin "4") (pinfunction "MMC1_4_4") (pintype "passive"))
    )
    (net (code "184") (name "unconnected-(U$101-MMC1_20-Pad20)") (class "Default")
      (node (ref "U$101") (pin "20") (pinfunction "MMC1_20_20") (pintype "passive"))
    )
    (net (code "185") (name "unconnected-(U$101-MMC1_22-Pad22)") (class "Default")
      (node (ref "U$101") (pin "22") (pinfunction "MMC1_22_22") (pintype "passive"))
    )
    (net (code "186") (name "unconnected-(U$101-MMC1_24-Pad24)") (class "Default")
      (node (ref "U$101") (pin "24") (pinfunction "MMC1_24_24") (pintype "passive"))
    )
    (net (code "187") (name "unconnected-(U$101-NC-Pad94)") (class "Default")
      (node (ref "U$101") (pin "94") (pinfunction "NC_94") (pintype "bidirectional"))
    )
    (net (code "188") (name "unconnected-(U$101-NC-Pad95)") (class "Default")
      (node (ref "U$101") (pin "95") (pinfunction "NC_95") (pintype "bidirectional"))
    )
    (net (code "189") (name "unconnected-(U$101-NC-Pad98)") (class "Default")
      (node (ref "U$101") (pin "98") (pinfunction "NC_98") (pintype "bidirectional"))
    )
    (net (code "190") (name "unconnected-(U$101-VDD_ADC_32-Pad78)") (class "Default")
      (node (ref "U$101") (pin "78") (pinfunction "VDD_ADC_32_78") (pintype "passive"))
    )
    (net (code "191") (name "unconnected-(U1-WP-Pad7)") (class "Default")
      (node (ref "U1") (pin "7") (pinfunction "WP_7") (pintype "bidirectional"))
    )
    (net (code "192") (name "unconnected-(U2-A0-Pad1)") (class "Default")
      (node (ref "U2") (pin "1") (pinfunction "A0_1") (pintype "bidirectional"))
    )
    (net (code "193") (name "unconnected-(U2-A1-Pad2)") (class "Default")
      (node (ref "U2") (pin "2") (pinfunction "A1_2") (pintype "bidirectional"))
    )
    (net (code "194") (name "unconnected-(U2-A2-Pad3)") (class "Default")
      (node (ref "U2") (pin "3") (pinfunction "A2_3") (pintype "bidirectional"))
    )
    (net (code "195") (name "unconnected-(U2-WP-Pad7)") (class "Default")
      (node (ref "U2") (pin "7") (pinfunction "WP_7") (pintype "bidirectional"))
    )
    (net (code "196") (name "unconnected-(U302-A3-Pad4)") (class "Default")
      (node (ref "U302") (pin "4") (pinfunction "A3_4") (pintype "bidirectional"))
    )
    (net (code "197") (name "unconnected-(U302-A4-Pad5)") (class "Default")
      (node (ref "U302") (pin "5") (pinfunction "A4_5") (pintype "bidirectional"))
    )
    (net (code "198") (name "unconnected-(U302-A5-Pad6)") (class "Default")
      (node (ref "U302") (pin "6") (pinfunction "A5_6") (pintype "bidirectional"))
    )
    (net (code "199") (name "unconnected-(U302-A6-Pad7)") (class "Default")
      (node (ref "U302") (pin "7") (pinfunction "A6_7") (pintype "bidirectional"))
    )
    (net (code "200") (name "unconnected-(U302-A7-Pad8)") (class "Default")
      (node (ref "U302") (pin "8") (pinfunction "A7_8") (pintype "bidirectional"))
    )
    (net (code "201") (name "unconnected-(U302-A8-Pad9)") (class "Default")
      (node (ref "U302") (pin "9") (pinfunction "A8_9") (pintype "bidirectional"))
    )
    (net (code "202") (name "unconnected-(U302-B3-Pad17)") (class "Default")
      (node (ref "U302") (pin "17") (pinfunction "B3_17") (pintype "bidirectional"))
    )
    (net (code "203") (name "unconnected-(U302-B4-Pad16)") (class "Default")
      (node (ref "U302") (pin "16") (pinfunction "B4_16") (pintype "bidirectional"))
    )
    (net (code "204") (name "unconnected-(U302-B5-Pad15)") (class "Default")
      (node (ref "U302") (pin "15") (pinfunction "B5_15") (pintype "bidirectional"))
    )
    (net (code "205") (name "unconnected-(U302-B6-Pad14)") (class "Default")
      (node (ref "U302") (pin "14") (pinfunction "B6_14") (pintype "bidirectional"))
    )
    (net (code "206") (name "unconnected-(U302-B7-Pad13)") (class "Default")
      (node (ref "U302") (pin "13") (pinfunction "B7_13") (pintype "bidirectional"))
    )
    (net (code "207") (name "unconnected-(U302-B8-Pad12)") (class "Default")
      (node (ref "U302") (pin "12") (pinfunction "B8_12") (pintype "bidirectional"))
    )
    (net (code "208") (name "unconnected-(U401-CSB1-Pad4)") (class "Default")
      (node (ref "U401") (pin "4") (pinfunction "CSB1_4") (pintype "bidirectional"))
    )
    (net (code "209") (name "unconnected-(U403-AUX_CL-Pad7)") (class "Default")
      (node (ref "U403") (pin "7") (pinfunction "AUX_CL_7") (pintype "bidirectional"))
    )
    (net (code "210") (name "unconnected-(U403-AUX_DA-Pad6)") (class "Default")
      (node (ref "U403") (pin "6") (pinfunction "AUX_DA_6") (pintype "bidirectional"))
    )
    (net (code "211") (name "unconnected-(U403-CLKOUT-Pad22)") (class "Default")
      (node (ref "U403") (pin "22") (pinfunction "CLKOUT_22") (pintype "bidirectional"))
    )
    (net (code "212") (name "unconnected-(U403-NC1-Pad2)") (class "Default")
      (node (ref "U403") (pin "2") (pinfunction "NC1_2") (pintype "bidirectional"))
    )
    (net (code "213") (name "unconnected-(U403-NC2-Pad3)") (class "Default")
      (node (ref "U403") (pin "3") (pinfunction "NC2_3") (pintype "bidirectional"))
    )
    (net (code "214") (name "unconnected-(U403-NC3-Pad4)") (class "Default")
      (node (ref "U403") (pin "4") (pinfunction "NC3_4") (pintype "bidirectional"))
    )
    (net (code "215") (name "unconnected-(U403-NC4-Pad5)") (class "Default")
      (node (ref "U403") (pin "5") (pinfunction "NC4_5") (pintype "bidirectional"))
    )
    (net (code "216") (name "unconnected-(U403-NC5-Pad14)") (class "Default")
      (node (ref "U403") (pin "14") (pinfunction "NC5_14") (pintype "bidirectional"))
    )
    (net (code "217") (name "unconnected-(U403-NC6-Pad15)") (class "Default")
      (node (ref "U403") (pin "15") (pinfunction "NC6_15") (pintype "bidirectional"))
    )
    (net (code "218") (name "unconnected-(U403-NC7-Pad16)") (class "Default")
      (node (ref "U403") (pin "16") (pinfunction "NC7_16") (pintype "bidirectional"))
    )
    (net (code "219") (name "unconnected-(U403-NC8-Pad17)") (class "Default")
      (node (ref "U403") (pin "17") (pinfunction "NC8_17") (pintype "bidirectional"))
    )
    (net (code "220") (name "unconnected-(U403-RESV1-Pad19)") (class "Default")
      (node (ref "U403") (pin "19") (pinfunction "RESV1_19") (pintype "bidirectional"))
    )
    (net (code "221") (name "unconnected-(U403-RESV2-Pad21)") (class "Default")
      (node (ref "U403") (pin "21") (pinfunction "RESV2_21") (pintype "bidirectional"))
    )
    (net (code "222") (name "unconnected-(U405-AUX_CL-Pad7)") (class "Default")
      (node (ref "U405") (pin "7") (pinfunction "AUX_CL_7") (pintype "bidirectional"))
    )
    (net (code "223") (name "unconnected-(U405-AUX_DA-Pad21)") (class "Default")
      (node (ref "U405") (pin "21") (pinfunction "AUX_DA_21") (pintype "bidirectional"))
    )
    (net (code "224") (name "unconnected-(U405-NC-Pad2)") (class "Default")
      (node (ref "U405") (pin "2") (pinfunction "NC_2") (pintype "bidirectional"))
    )
    (net (code "225") (name "unconnected-(U405-NC-Pad3)") (class "Default")
      (node (ref "U405") (pin "3") (pinfunction "NC_3") (pintype "bidirectional"))
    )
    (net (code "226") (name "unconnected-(U405-NC-Pad4)") (class "Default")
      (node (ref "U405") (pin "4") (pinfunction "NC_4") (pintype "bidirectional"))
    )
    (net (code "227") (name "unconnected-(U405-NC-Pad5)") (class "Default")
      (node (ref "U405") (pin "5") (pinfunction "NC_5") (pintype "bidirectional"))
    )
    (net (code "228") (name "unconnected-(U405-NC-Pad6)") (class "Default")
      (node (ref "U405") (pin "6") (pinfunction "NC_6") (pintype "bidirectional"))
    )
    (net (code "229") (name "unconnected-(U405-NC-Pad14)") (class "Default")
      (node (ref "U405") (pin "14") (pinfunction "NC_14") (pintype "bidirectional"))
    )
    (net (code "230") (name "unconnected-(U405-NC-Pad15)") (class "Default")
      (node (ref "U405") (pin "15") (pinfunction "NC_15") (pintype "bidirectional"))
    )
    (net (code "231") (name "unconnected-(U405-NC-Pad16)") (class "Default")
      (node (ref "U405") (pin "16") (pinfunction "NC_16") (pintype "bidirectional"))
    )
    (net (code "232") (name "unconnected-(U405-NC-Pad17)") (class "Default")
      (node (ref "U405") (pin "17") (pinfunction "NC_17") (pintype "bidirectional"))
    )
    (net (code "233") (name "unconnected-(U405-RESV-Pad19)") (class "Default")
      (node (ref "U405") (pin "19") (pinfunction "RESV_19") (pintype "bidirectional"))
    )
    (net (code "234") (name "unconnected-(U406-DEN_G-Pad10)") (class "Default")
      (node (ref "U406") (pin "10") (pinfunction "DEN_G_10") (pintype "bidirectional"))
    )
    (net (code "235") (name "unconnected-(U406-INT_G-Pad11)") (class "Default")
      (node (ref "U406") (pin "11") (pinfunction "INT_G_11") (pintype "bidirectional"))
    )
    (net (code "236") (name "unconnected-(U406-NC-Pad1)") (class "Default")
      (node (ref "U406") (pin "1") (pinfunction "NC_1") (pintype "bidirectional"))
    )
    (net (code "237") (name "unconnected-(U701-A5-Pad6)") (class "Default")
      (node (ref "U701") (pin "6") (pinfunction "A5_6") (pintype "bidirectional"))
    )
    (net (code "238") (name "unconnected-(U701-A6-Pad7)") (class "Default")
      (node (ref "U701") (pin "7") (pinfunction "A6_7") (pintype "bidirectional"))
    )
    (net (code "239") (name "unconnected-(U701-A7-Pad8)") (class "Default")
      (node (ref "U701") (pin "8") (pinfunction "A7_8") (pintype "bidirectional"))
    )
    (net (code "240") (name "unconnected-(U701-A8-Pad9)") (class "Default")
      (node (ref "U701") (pin "9") (pinfunction "A8_9") (pintype "bidirectional"))
    )
    (net (code "241") (name "unconnected-(U701-B5-Pad15)") (class "Default")
      (node (ref "U701") (pin "15") (pinfunction "B5_15") (pintype "bidirectional"))
    )
    (net (code "242") (name "unconnected-(U701-B6-Pad14)") (class "Default")
      (node (ref "U701") (pin "14") (pinfunction "B6_14") (pintype "bidirectional"))
    )
    (net (code "243") (name "unconnected-(U701-B7-Pad13)") (class "Default")
      (node (ref "U701") (pin "13") (pinfunction "B7_13") (pintype "bidirectional"))
    )
    (net (code "244") (name "unconnected-(U701-B8-Pad12)") (class "Default")
      (node (ref "U701") (pin "12") (pinfunction "B8_12") (pintype "bidirectional"))
    )
    (net (code "245") (name "unconnected-(U802-CSET-Pad6)") (class "Default")
      (node (ref "U802") (pin "6") (pinfunction "CSET_6") (pintype "bidirectional"))
    )
    (net (code "246") (name "unconnected-(U802-POR2-Pad3)") (class "Default")
      (node (ref "U802") (pin "3") (pinfunction "POR2_3") (pintype "bidirectional"))
    )
    (net (code "247") (name "unconnected-(U802-VOUT2-Pad7)") (class "Default")
      (node (ref "U802") (pin "7") (pinfunction "VOUT2_7") (pintype "bidirectional"))
    )
    (net (code "248") (name "~{ACCEL_MAG_CS}") (class "Default")
      (node (ref "U$101") (pin "63") (pinfunction "17_SPI_0_CS0_63") (pintype "passive"))
      (node (ref "U406") (pin "20") (pinfunction "CS_XM_20") (pintype "bidirectional"))
    )
    (net (code "249") (name "~{FRAM_CS}") (class "Default")
      (node (ref "U$101") (pin "12") (pinfunction "PRU0_R30[14]_12_12") (pintype "passive"))
      (node (ref "U102") (pin "1") (pinfunction "~{S}_1") (pintype "bidirectional"))
    )
    (net (code "250") (name "~{GYRO_CS}") (class "Default")
      (node (ref "U$101") (pin "9") (pinfunction "9_GPIO2[5]_9") (pintype "passive"))
      (node (ref "U406") (pin "19") (pinfunction "CS_G_19") (pintype "bidirectional"))
    )
    (net (code "251") (name "~{LED_AMBER}") (class "Default")
      (node (ref "R610") (pin "P$1") (pinfunction "1_P$1") (pintype "passive"))
      (node (ref "U$101") (pin "71") (pinfunction "25_PRU0_R30/31[7]_71") (pintype "passive"))
    )
    (net (code "252") (name "~{LED_BLUE}") (class "Default")
      (node (ref "R612") (pin "P$1") (pinfunction "1_P$1") (pintype "passive"))
      (node (ref "U$101") (pin "61") (pinfunction "15_GPIO1[16]_61") (pintype "passive"))
    )
    (net (code "253") (name "~{LED_SAFETY}") (class "Default")
      (node (ref "R611") (pin "P$2") (pinfunction "2_P$2") (pintype "passive"))
      (node (ref "U$101") (pin "26") (pinfunction "GPIO1[29]_26_26") (pintype "passive"))
    )
    (net (code "254") (name "~{VDD_5V_HIPOWER_OC}") (class "Default")
      (node (ref "R502") (pin "P$1") (pinfunction "1_P$1") (pintype "passive"))
      (node (ref "U$101") (pin "19") (pinfunction "19_GPIO0[22]_19") (pintype "passive"))
      (node (ref "U501") (pin "4") (pinfunction "~{FAULT}_4") (pintype "bidirectional"))
    )
    (net (code "255") (name "~{VDD_5V_PERIPH_EN}") (class "Default")
      (node (ref "R506") (pin "P$1") (pinfunction "1_P$1") (pintype "passive"))
      (node (ref "U$101") (pin "58") (pinfunction "GPIO1[28]_12_58") (pintype "passive"))
      (node (ref "U501") (pin "5") (pinfunction "~{CE}_5") (pintype "bidirectional"))
      (node (ref "U503") (pin "5") (pinfunction "~{CE}_5") (pintype "bidirectional"))
    )
    (net (code "256") (name "~{VDD_5V_PERIPH_OC}") (class "Default")
      (node (ref "R507") (pin "P$1") (pinfunction "1_P$1") (pintype "passive"))
      (node (ref "U$101") (pin "13") (pinfunction "13_GPIO0[23]_13") (pintype "passive"))
      (node (ref "U503") (pin "4") (pinfunction "~{FAULT}_4") (pintype "bidirectional"))
    )
    (net (code "257") (name "~{VDD_SERVO_IN_FAULT}") (class "Default")
      (node (ref "U$101") (pin "18") (pinfunction "GPIO2[1]_18_18") (pintype "passive"))
    )
  )
)
